# BlockBox.net
KiCad netlist of a schematic drawn in EAGLE
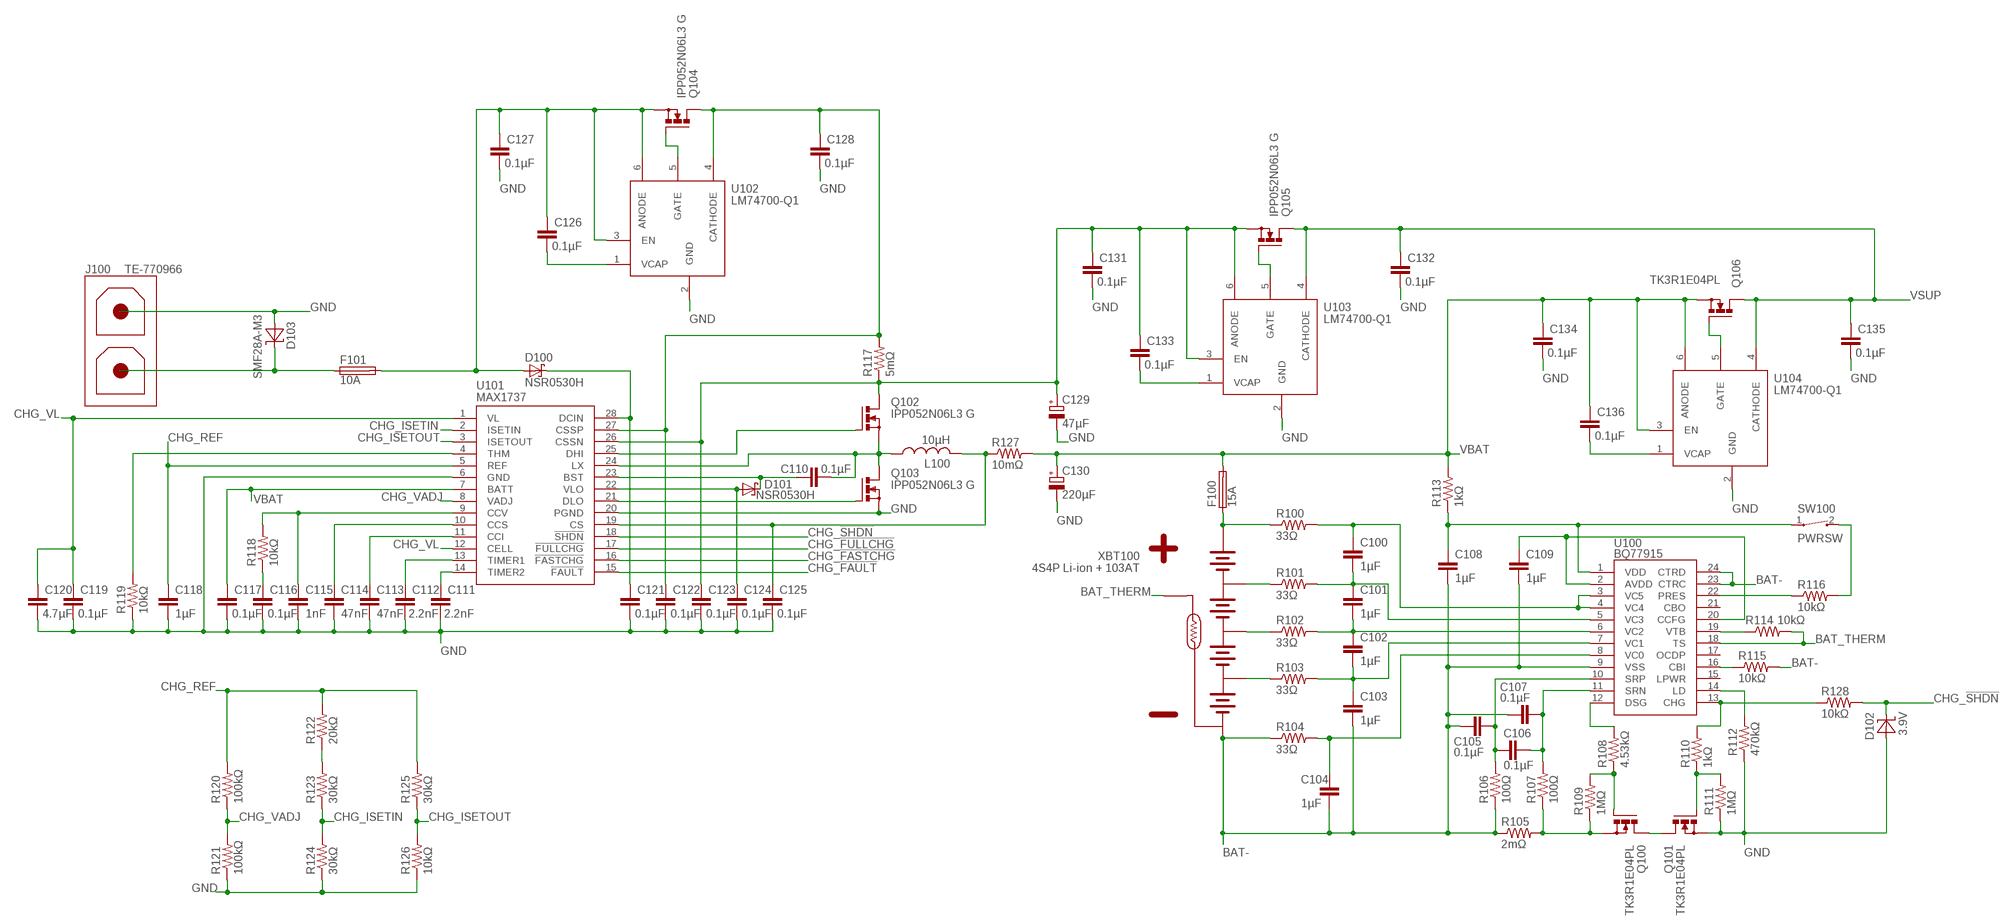
[diagram p0: schematic, sheet 1]
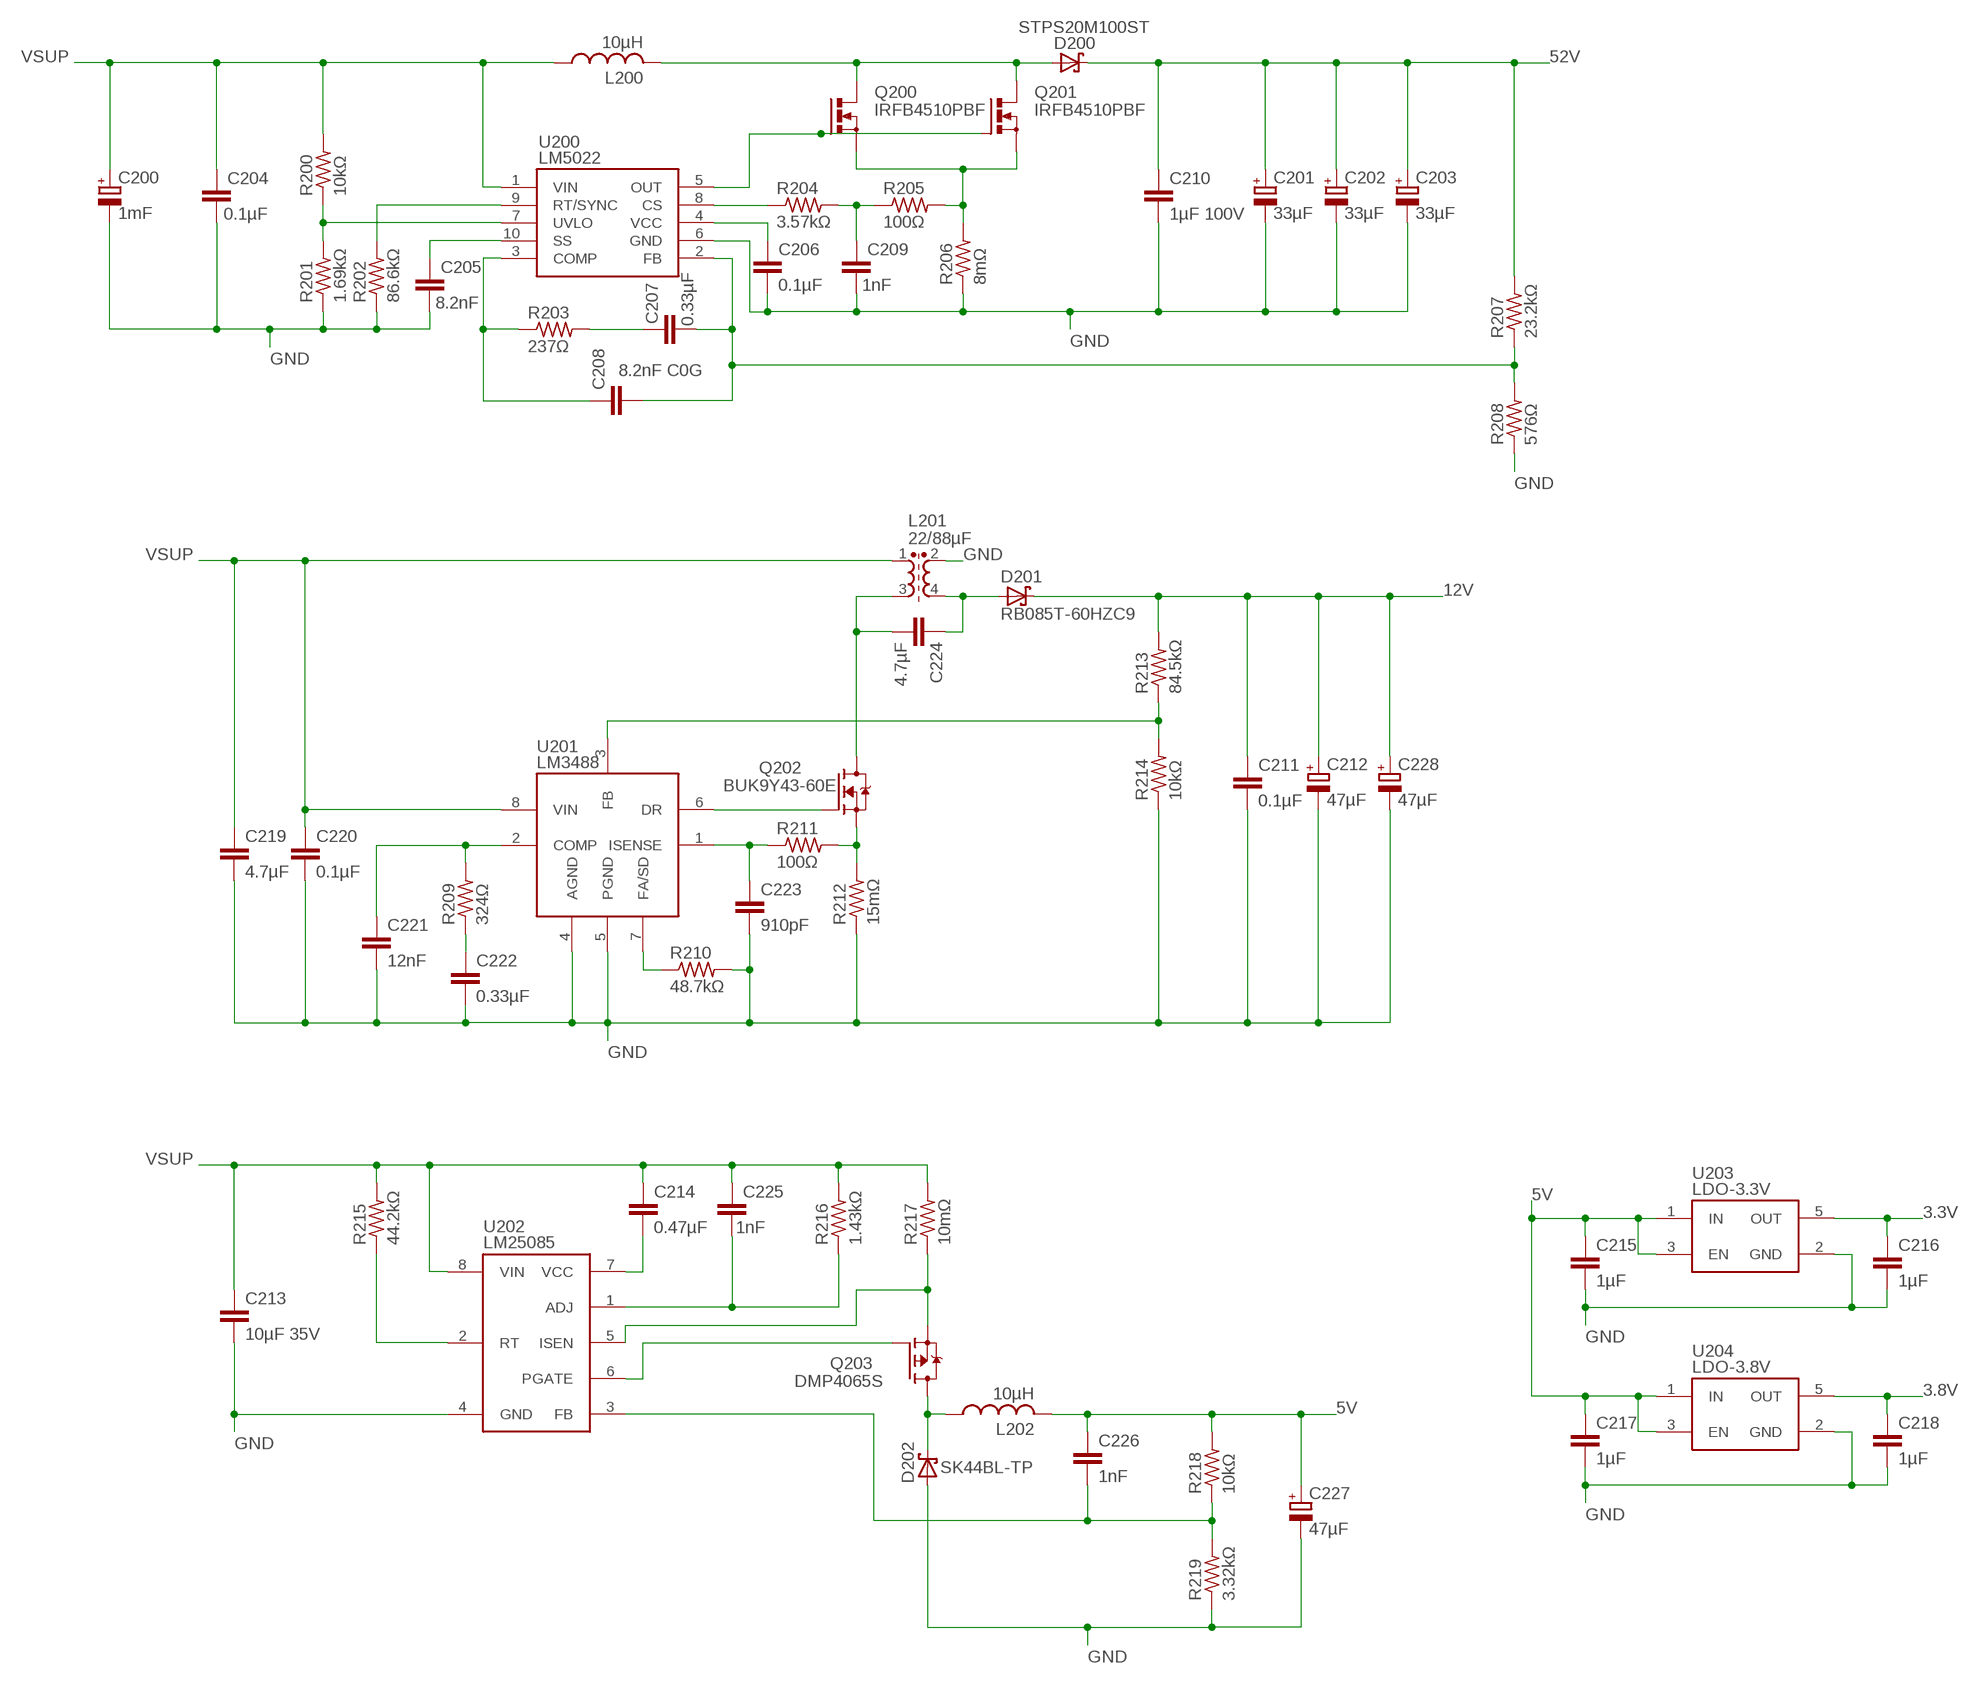
[diagram p1: schematic, sheet 2]
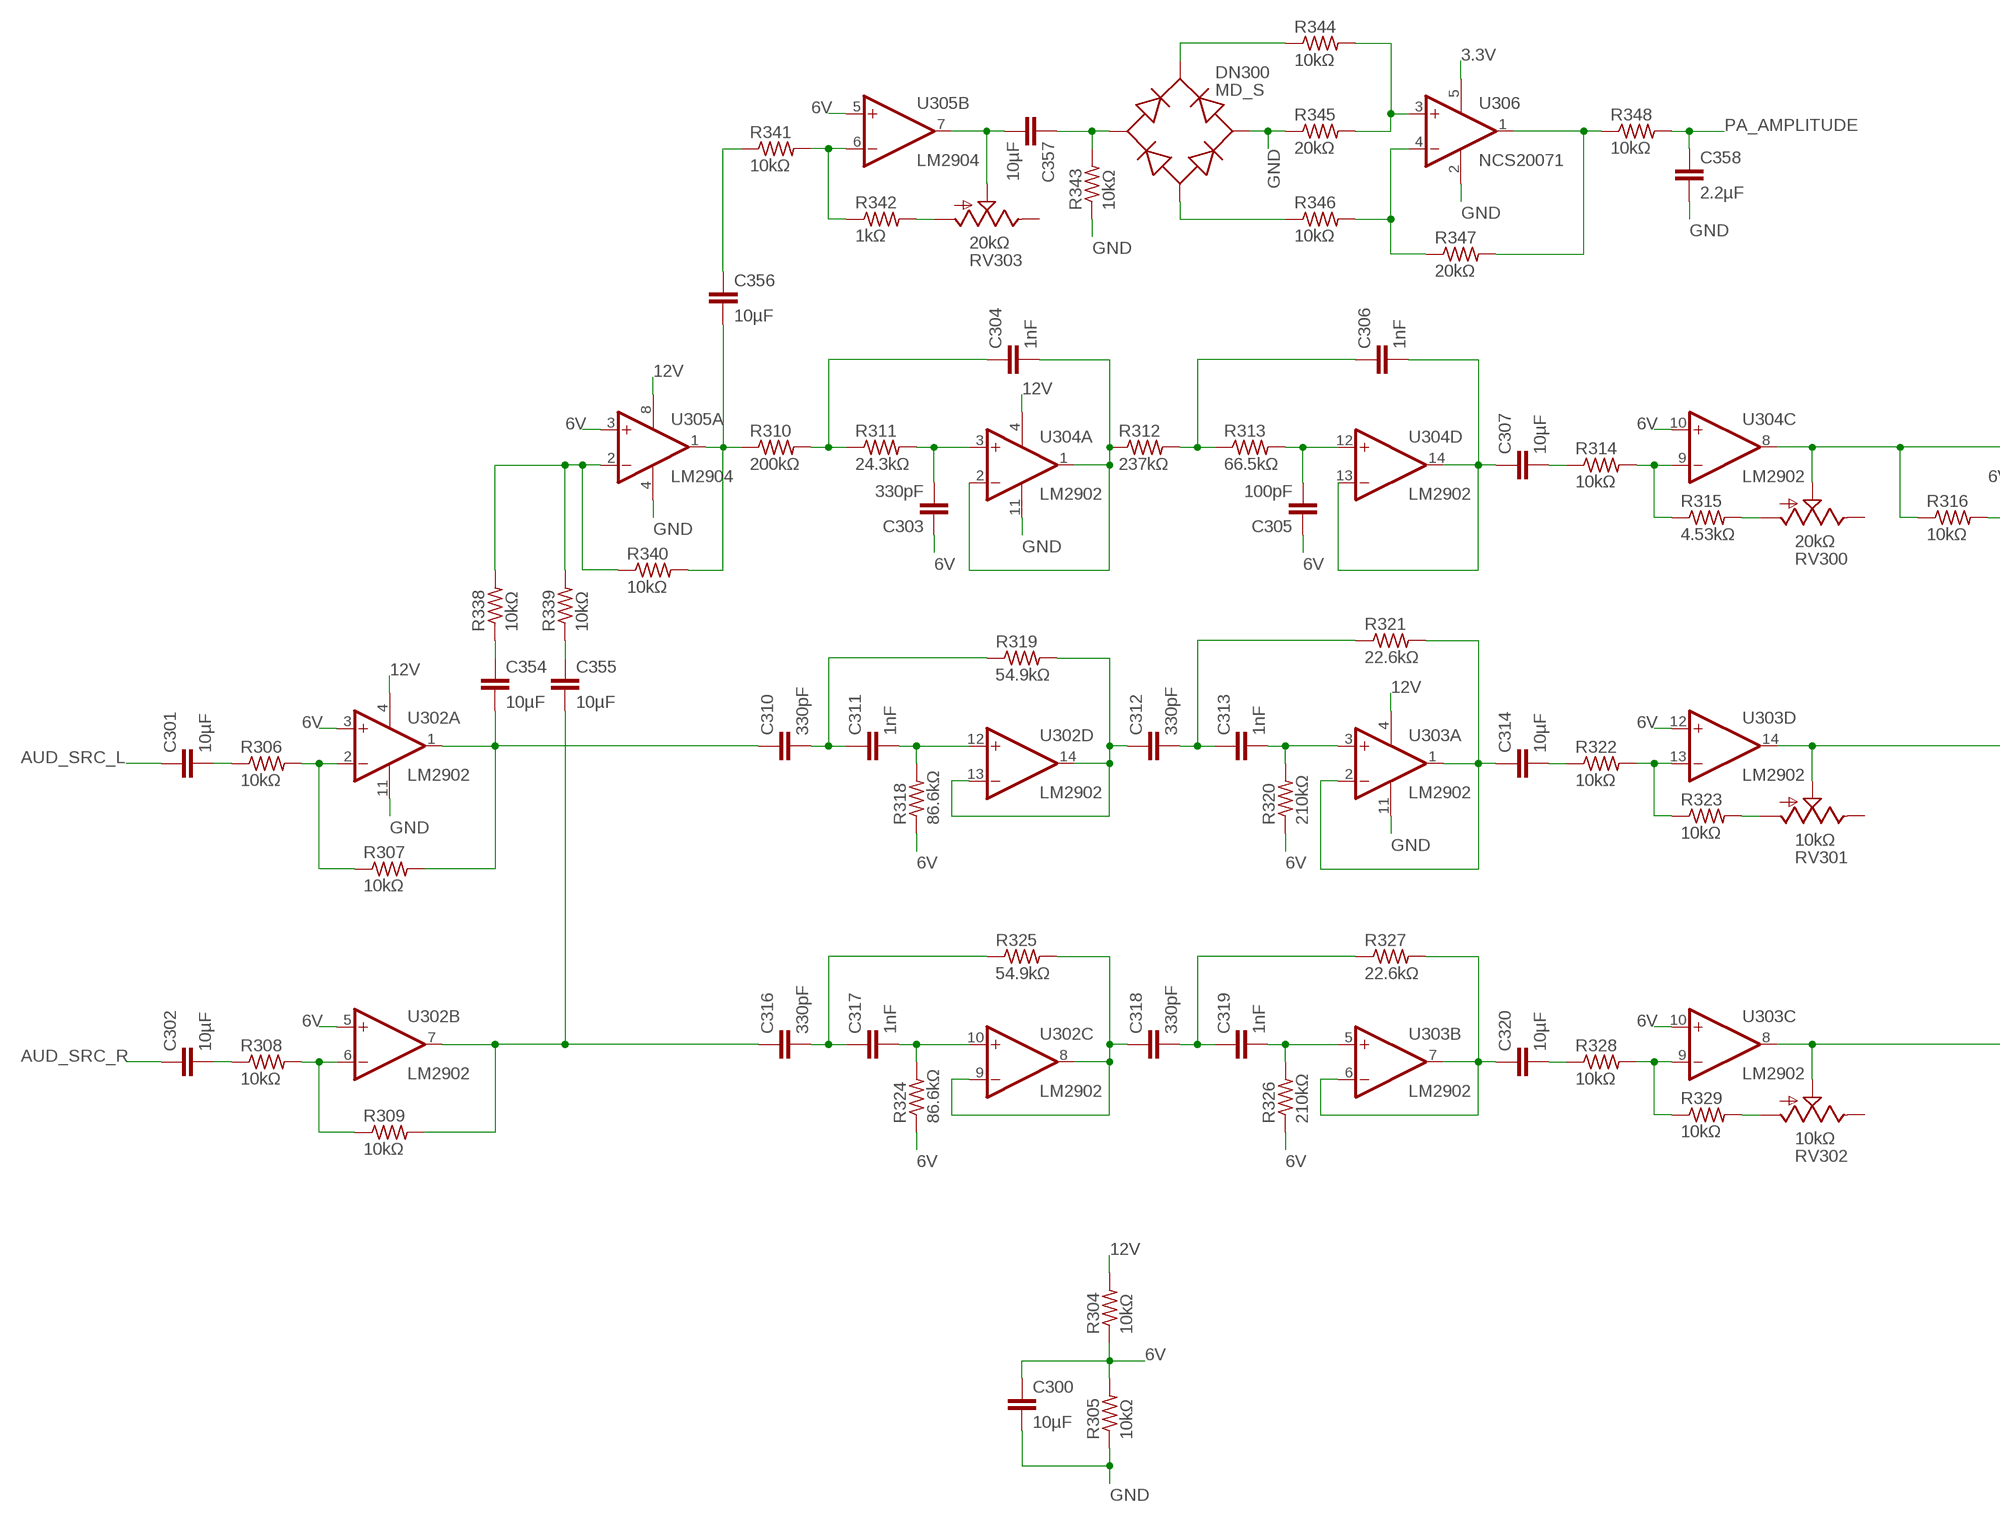
[diagram p2: schematic, sheet 3, part 1 of 2]
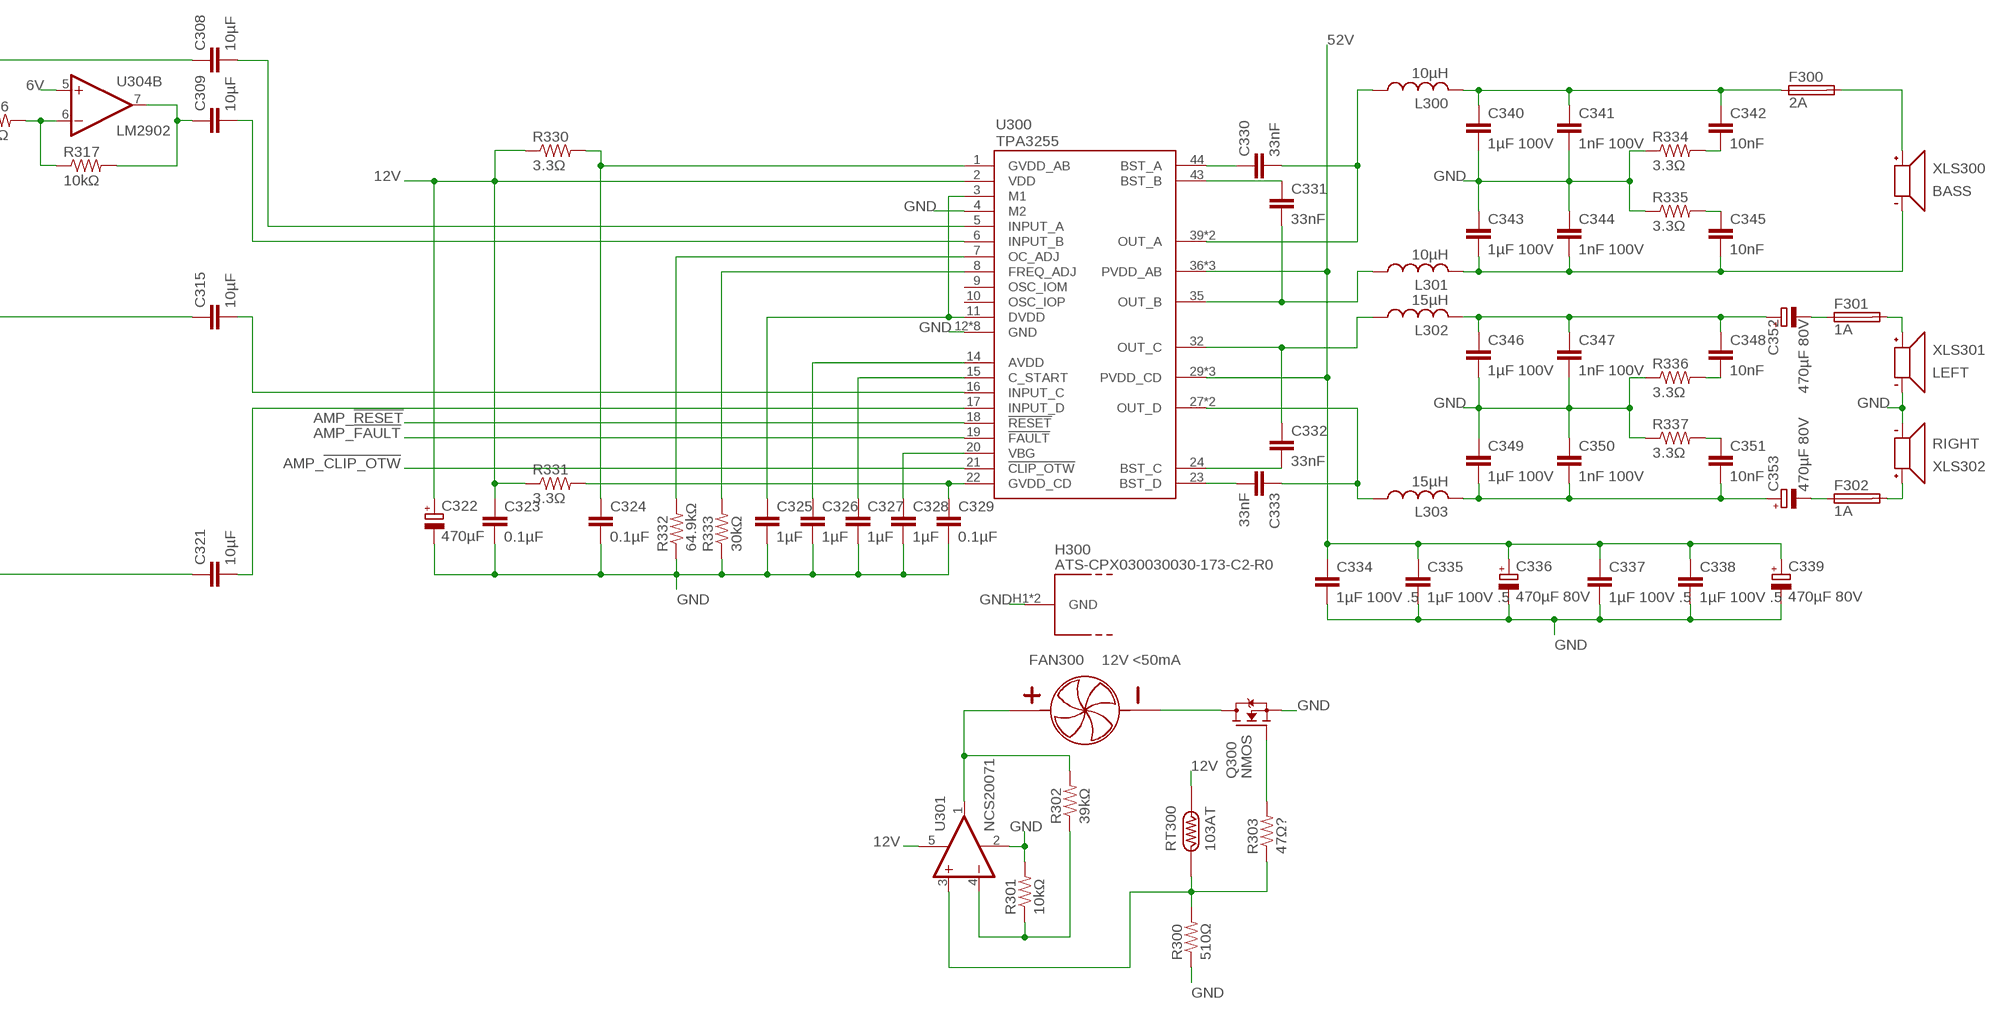
[diagram p3: schematic, sheet 3, part 2 of 2]
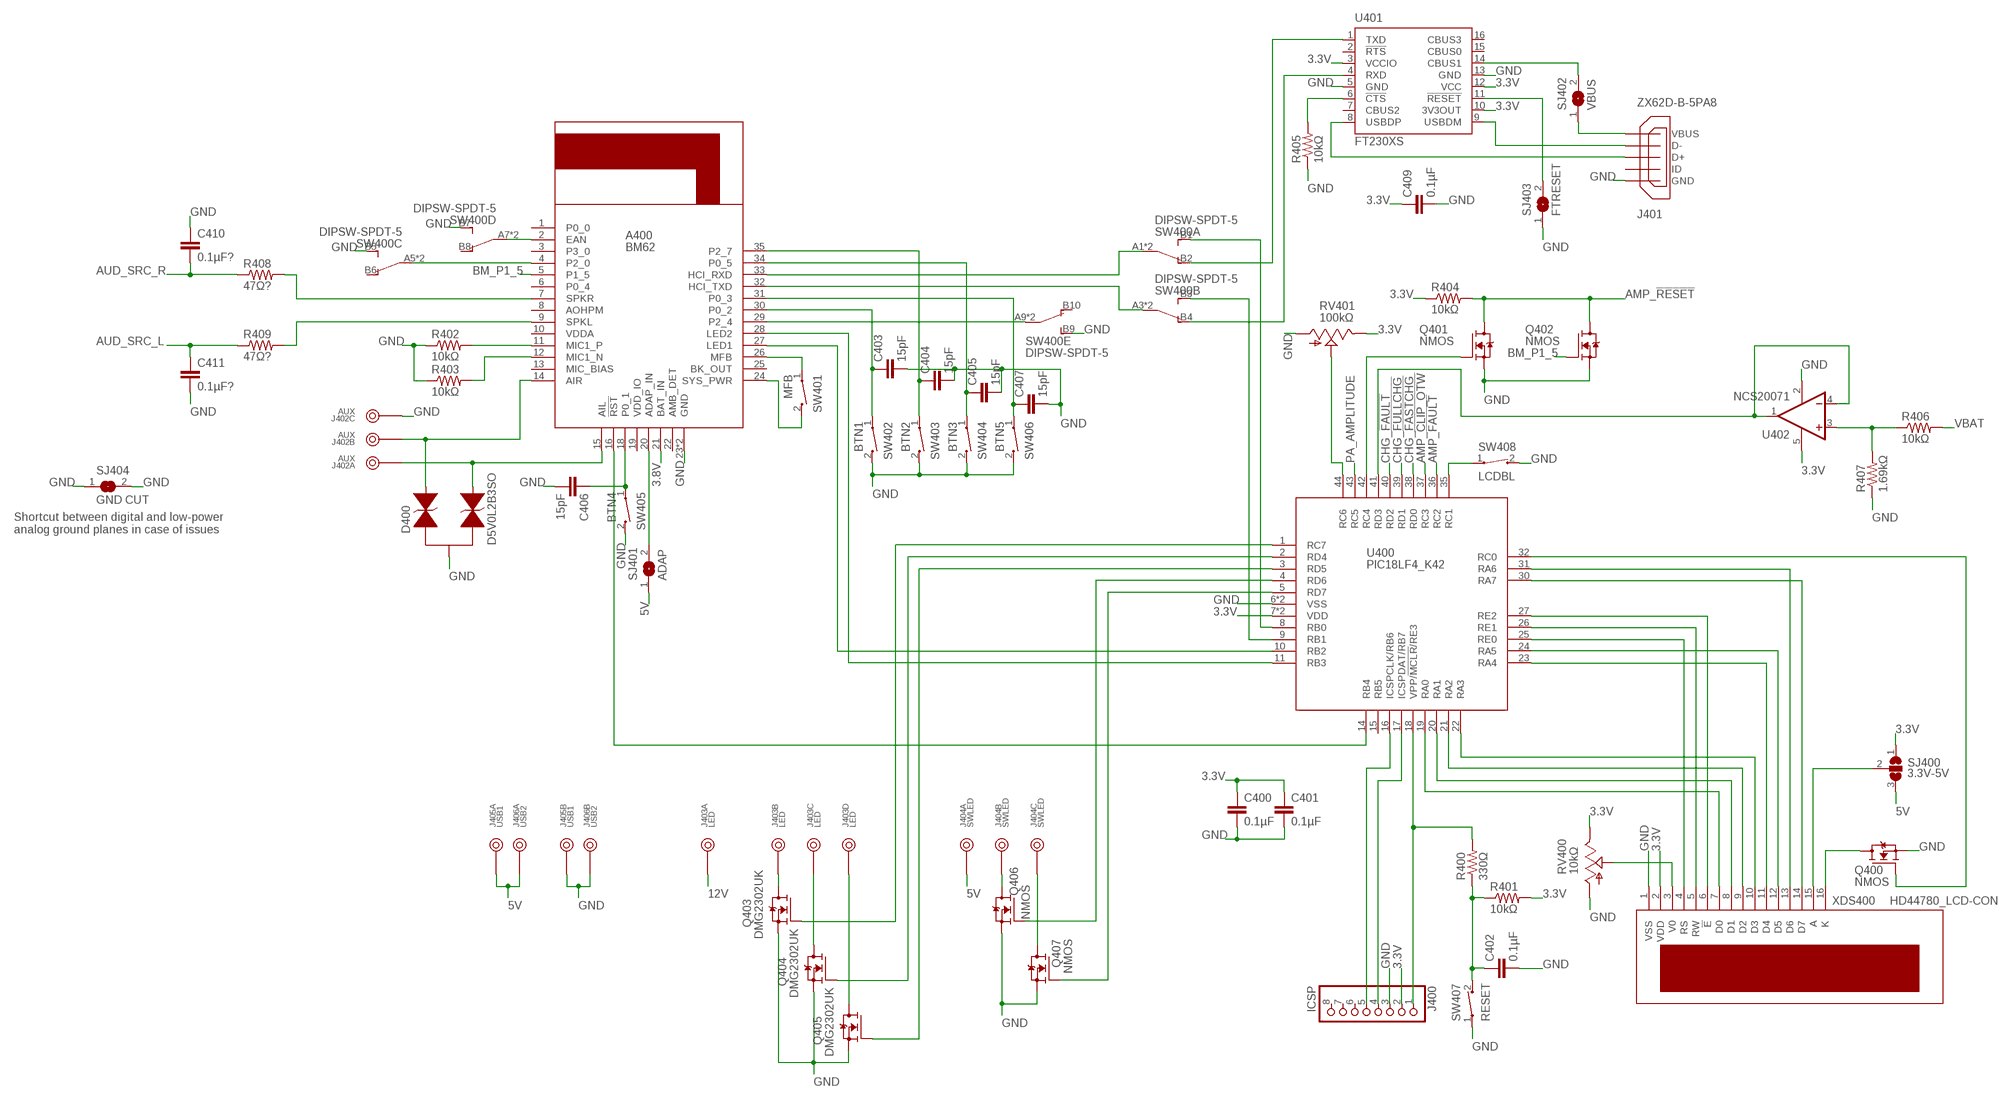
[diagram p4: schematic, sheet 4]

(export (version "E")
  (design (tool "Eeschema 10.0.6"))
  (components
    (comp (ref "C100")
      (value "1µF")
      (footprint "eagle-import:C0603")
      (libsource (lib "eagle-import") (part "C-EUC0603"))
    )
    (comp (ref "C101")
      (value "1µF")
      (footprint "eagle-import:C0603")
      (libsource (lib "eagle-import") (part "C-EUC0603"))
    )
    (comp (ref "C102")
      (value "1µF")
      (footprint "eagle-import:C0603")
      (libsource (lib "eagle-import") (part "C-EUC0603"))
    )
    (comp (ref "C103")
      (value "1µF")
      (footprint "eagle-import:C0603")
      (libsource (lib "eagle-import") (part "C-EUC0603"))
    )
    (comp (ref "C104")
      (value "1µF")
      (footprint "eagle-import:C0603")
      (libsource (lib "eagle-import") (part "C-EUC0603"))
    )
    (comp (ref "C105")
      (value "0.1µF")
      (footprint "eagle-import:C0805")
      (libsource (lib "eagle-import") (part "C-EUC0805"))
    )
    (comp (ref "C106")
      (value "0.1µF")
      (footprint "eagle-import:C0805")
      (libsource (lib "eagle-import") (part "C-EUC0805"))
    )
    (comp (ref "C107")
      (value "0.1µF")
      (footprint "eagle-import:C0805")
      (libsource (lib "eagle-import") (part "C-EUC0805"))
    )
    (comp (ref "C108")
      (value "1µF")
      (footprint "eagle-import:C0603")
      (libsource (lib "eagle-import") (part "C-EUC0603"))
    )
    (comp (ref "C109")
      (value "1µF")
      (footprint "eagle-import:C0603")
      (libsource (lib "eagle-import") (part "C-EUC0603"))
    )
    (comp (ref "C110")
      (value "0.1µF")
      (footprint "eagle-import:C0805")
      (libsource (lib "eagle-import") (part "C-EUC0805"))
    )
    (comp (ref "C111")
      (value "2.2nF")
      (footprint "eagle-import:C0603")
      (libsource (lib "eagle-import") (part "C-EUC0603"))
    )
    (comp (ref "C112")
      (value "2.2nF")
      (footprint "eagle-import:C0603")
      (libsource (lib "eagle-import") (part "C-EUC0603"))
    )
    (comp (ref "C113")
      (value "47nF")
      (footprint "eagle-import:C0603")
      (libsource (lib "eagle-import") (part "C-EUC0603"))
    )
    (comp (ref "C114")
      (value "47nF")
      (footprint "eagle-import:C0603")
      (libsource (lib "eagle-import") (part "C-EUC0603"))
    )
    (comp (ref "C115")
      (value "1nF")
      (footprint "eagle-import:C0603")
      (libsource (lib "eagle-import") (part "C-EUC0603"))
    )
    (comp (ref "C116")
      (value "0.1µF")
      (footprint "eagle-import:C0805")
      (libsource (lib "eagle-import") (part "C-EUC0805"))
    )
    (comp (ref "C117")
      (value "0.1µF")
      (footprint "eagle-import:C0805")
      (libsource (lib "eagle-import") (part "C-EUC0805"))
    )
    (comp (ref "C118")
      (value "1µF")
      (footprint "eagle-import:C0603")
      (libsource (lib "eagle-import") (part "C-EUC0603"))
    )
    (comp (ref "C119")
      (value "0.1µF")
      (footprint "eagle-import:C0805")
      (libsource (lib "eagle-import") (part "C-EUC0805"))
    )
    (comp (ref "C120")
      (value "4.7µF")
      (footprint "eagle-import:C0805")
      (libsource (lib "eagle-import") (part "C-EUC0805"))
    )
    (comp (ref "C121")
      (value "0.1µF")
      (footprint "eagle-import:C0805")
      (libsource (lib "eagle-import") (part "C-EUC0805"))
    )
    (comp (ref "C122")
      (value "0.1µF")
      (footprint "eagle-import:C0805")
      (libsource (lib "eagle-import") (part "C-EUC0805"))
    )
    (comp (ref "C123")
      (value "0.1µF")
      (footprint "eagle-import:C0805")
      (libsource (lib "eagle-import") (part "C-EUC0805"))
    )
    (comp (ref "C124")
      (value "0.1µF")
      (footprint "eagle-import:C0805")
      (libsource (lib "eagle-import") (part "C-EUC0805"))
    )
    (comp (ref "C125")
      (value "0.1µF")
      (footprint "eagle-import:C0805")
      (libsource (lib "eagle-import") (part "C-EUC0805"))
    )
    (comp (ref "C126")
      (value "0.1µF")
      (footprint "eagle-import:C0805")
      (libsource (lib "eagle-import") (part "C-EUC0805"))
    )
    (comp (ref "C127")
      (value "0.1µF")
      (footprint "eagle-import:C0805")
      (libsource (lib "eagle-import") (part "C-EUC0805"))
    )
    (comp (ref "C128")
      (value "0.1µF")
      (footprint "eagle-import:C0805")
      (libsource (lib "eagle-import") (part "C-EUC0805"))
    )
    (comp (ref "C129")
      (value "47µF")
      (footprint "eagle-import:E2,5-6")
      (libsource (lib "eagle-import") (part "CPOL-EUE2.5-6"))
    )
    (comp (ref "C130")
      (value "220µF")
      (footprint "eagle-import:E3,5-8")
      (libsource (lib "eagle-import") (part "CPOL-EUE3.5-8"))
    )
    (comp (ref "C131")
      (value "0.1µF")
      (footprint "eagle-import:C0805")
      (libsource (lib "eagle-import") (part "C-EUC0805"))
    )
    (comp (ref "C132")
      (value "0.1µF")
      (footprint "eagle-import:C0805")
      (libsource (lib "eagle-import") (part "C-EUC0805"))
    )
    (comp (ref "C133")
      (value "0.1µF")
      (footprint "eagle-import:C0805")
      (libsource (lib "eagle-import") (part "C-EUC0805"))
    )
    (comp (ref "C134")
      (value "0.1µF")
      (footprint "eagle-import:C0805")
      (libsource (lib "eagle-import") (part "C-EUC0805"))
    )
    (comp (ref "C135")
      (value "0.1µF")
      (footprint "eagle-import:C0805")
      (libsource (lib "eagle-import") (part "C-EUC0805"))
    )
    (comp (ref "C136")
      (value "0.1µF")
      (footprint "eagle-import:C0805")
      (libsource (lib "eagle-import") (part "C-EUC0805"))
    )
    (comp (ref "D100")
      (value "NSR0530H")
      (footprint "eagle-import:SOD323")
      (libsource (lib "eagle-import") (part "SOD323-SCHOTTKY"))
    )
    (comp (ref "D101")
      (value "NSR0530H")
      (footprint "eagle-import:SOD323")
      (libsource (lib "eagle-import") (part "SOD323-SCHOTTKY"))
    )
    (comp (ref "D102")
      (value "3.9V")
      (footprint "eagle-import:SOD323")
      (libsource (lib "eagle-import") (part "SOD323-ZENER"))
    )
    (comp (ref "D103")
      (value "SMF28A-M3")
      (footprint "eagle-import:DO-219AB")
      (libsource (lib "eagle-import") (part "DO-219AB-ZENER"))
    )
    (comp (ref "F100")
      (value "15A")
      (footprint "eagle-import:F2410")
      (libsource (lib "eagle-import") (part "2410-FUSE"))
    )
    (comp (ref "F101")
      (value "10A")
      (footprint "eagle-import:F2410")
      (libsource (lib "eagle-import") (part "2410-FUSE"))
    )
    (comp (ref "J100")
      (value "TE-770966")
      (footprint "eagle-import:TE-770966")
      (libsource (lib "eagle-import") (part "TE-770966"))
    )
    (comp (ref "L100")
      (value "10µH")
      (footprint "eagle-import:PM5022")
      (libsource (lib "eagle-import") (part "PM5022"))
    )
    (comp (ref "Q100")
      (value "TK3R1E04PL")
      (footprint "eagle-import:TO220BV")
      (libsource (lib "eagle-import") (part "TO220BV-N-MOSFET"))
    )
    (comp (ref "Q101")
      (value "TK3R1E04PL")
      (footprint "eagle-import:TO220BV")
      (libsource (lib "eagle-import") (part "TO220BV-N-MOSFET"))
    )
    (comp (ref "Q102")
      (value "IPP052N06L3 G")
      (footprint "eagle-import:TO220BV")
      (libsource (lib "eagle-import") (part "TO220BV-N-MOSFET"))
    )
    (comp (ref "Q103")
      (value "IPP052N06L3 G")
      (footprint "eagle-import:TO220BV")
      (libsource (lib "eagle-import") (part "TO220BV-N-MOSFET"))
    )
    (comp (ref "Q104")
      (value "IPP052N06L3 G")
      (footprint "eagle-import:TO220BV")
      (libsource (lib "eagle-import") (part "TO220BV-N-MOSFET"))
    )
    (comp (ref "Q105")
      (value "IPP052N06L3 G")
      (footprint "eagle-import:TO220BV")
      (libsource (lib "eagle-import") (part "TO220BV-N-MOSFET"))
    )
    (comp (ref "Q106")
      (value "TK3R1E04PL")
      (footprint "eagle-import:TO220BV")
      (libsource (lib "eagle-import") (part "TO220BV-N-MOSFET"))
    )
    (comp (ref "R100")
      (value "33Ω")
      (footprint "eagle-import:R0603")
      (libsource (lib "eagle-import") (part "R-US_R0603"))
    )
    (comp (ref "R101")
      (value "33Ω")
      (footprint "eagle-import:R0603")
      (libsource (lib "eagle-import") (part "R-US_R0603"))
    )
    (comp (ref "R102")
      (value "33Ω")
      (footprint "eagle-import:R0603")
      (libsource (lib "eagle-import") (part "R-US_R0603"))
    )
    (comp (ref "R103")
      (value "33Ω")
      (footprint "eagle-import:R0603")
      (libsource (lib "eagle-import") (part "R-US_R0603"))
    )
    (comp (ref "R104")
      (value "33Ω")
      (footprint "eagle-import:R0603")
      (libsource (lib "eagle-import") (part "R-US_R0603"))
    )
    (comp (ref "R105")
      (value "2mΩ")
      (footprint "eagle-import:R2512")
      (libsource (lib "eagle-import") (part "R-US_R2512"))
    )
    (comp (ref "R106")
      (value "100Ω")
      (footprint "eagle-import:R0603")
      (libsource (lib "eagle-import") (part "R-US_R0603"))
    )
    (comp (ref "R107")
      (value "100Ω")
      (footprint "eagle-import:R0603")
      (libsource (lib "eagle-import") (part "R-US_R0603"))
    )
    (comp (ref "R108")
      (value "4.53kΩ")
      (footprint "eagle-import:R0603")
      (libsource (lib "eagle-import") (part "R-US_R0603"))
    )
    (comp (ref "R109")
      (value "1MΩ")
      (footprint "eagle-import:R0603")
      (libsource (lib "eagle-import") (part "R-US_R0603"))
    )
    (comp (ref "R110")
      (value "1kΩ")
      (footprint "eagle-import:R0805")
      (libsource (lib "eagle-import") (part "R-US_R0805"))
    )
    (comp (ref "R111")
      (value "1MΩ")
      (footprint "eagle-import:R0603")
      (libsource (lib "eagle-import") (part "R-US_R0603"))
    )
    (comp (ref "R112")
      (value "470kΩ")
      (footprint "eagle-import:R0603")
      (libsource (lib "eagle-import") (part "R-US_R0603"))
    )
    (comp (ref "R113")
      (value "1kΩ")
      (footprint "eagle-import:R0805")
      (libsource (lib "eagle-import") (part "R-US_R0805"))
    )
    (comp (ref "R114")
      (value "10kΩ")
      (footprint "eagle-import:R0805")
      (libsource (lib "eagle-import") (part "R-US_R0805"))
    )
    (comp (ref "R115")
      (value "10kΩ")
      (footprint "eagle-import:R0805")
      (libsource (lib "eagle-import") (part "R-US_R0805"))
    )
    (comp (ref "R116")
      (value "10kΩ")
      (footprint "eagle-import:R0805")
      (libsource (lib "eagle-import") (part "R-US_R0805"))
    )
    (comp (ref "R117")
      (value "5mΩ")
      (footprint "eagle-import:R1206")
      (libsource (lib "eagle-import") (part "R-US_R1206"))
    )
    (comp (ref "R118")
      (value "10kΩ")
      (footprint "eagle-import:R0805")
      (libsource (lib "eagle-import") (part "R-US_R0805"))
    )
    (comp (ref "R119")
      (value "10kΩ")
      (footprint "eagle-import:R0805")
      (libsource (lib "eagle-import") (part "R-US_R0805"))
    )
    (comp (ref "R120")
      (value "100kΩ")
      (footprint "eagle-import:R0805")
      (libsource (lib "eagle-import") (part "R-US_R0805"))
    )
    (comp (ref "R121")
      (value "100kΩ")
      (footprint "eagle-import:R0805")
      (libsource (lib "eagle-import") (part "R-US_R0805"))
    )
    (comp (ref "R122")
      (value "20kΩ")
      (footprint "eagle-import:R0603")
      (libsource (lib "eagle-import") (part "R-US_R0603"))
    )
    (comp (ref "R123")
      (value "30kΩ")
      (footprint "eagle-import:R0603")
      (libsource (lib "eagle-import") (part "R-US_R0603"))
    )
    (comp (ref "R124")
      (value "30kΩ")
      (footprint "eagle-import:R0603")
      (libsource (lib "eagle-import") (part "R-US_R0603"))
    )
    (comp (ref "R125")
      (value "30kΩ")
      (footprint "eagle-import:R0603")
      (libsource (lib "eagle-import") (part "R-US_R0603"))
    )
    (comp (ref "R126")
      (value "10kΩ")
      (footprint "eagle-import:R0805")
      (libsource (lib "eagle-import") (part "R-US_R0805"))
    )
    (comp (ref "R127")
      (value "10mΩ")
      (footprint "eagle-import:R1206")
      (libsource (lib "eagle-import") (part "R-US_R1206"))
    )
    (comp (ref "R128")
      (value "10kΩ")
      (footprint "eagle-import:R0805")
      (libsource (lib "eagle-import") (part "R-US_R0805"))
    )
    (comp (ref "SW100")
      (value "PWRSW")
      (footprint "eagle-import:WIRE-2P-SIMPLE")
      (libsource (lib "eagle-import") (part "WIRED-SWITCH-NO"))
    )
    (comp (ref "U100")
      (value "BQ77915")
      (footprint "eagle-import:TSSOP24")
      (libsource (lib "eagle-import") (part "BQ77915"))
    )
    (comp (ref "U101")
      (value "MAX1737")
      (footprint "eagle-import:QSOP28")
      (libsource (lib "eagle-import") (part "MAX1737"))
    )
    (comp (ref "U102")
      (value "LM74700-Q1")
      (footprint "eagle-import:SOT23-6L")
      (libsource (lib "eagle-import") (part "LM74700-Q1"))
    )
    (comp (ref "U103")
      (value "LM74700-Q1")
      (footprint "eagle-import:SOT23-6L")
      (libsource (lib "eagle-import") (part "LM74700-Q1"))
    )
    (comp (ref "U104")
      (value "LM74700-Q1")
      (footprint "eagle-import:SOT23-6L")
      (libsource (lib "eagle-import") (part "LM74700-Q1"))
    )
    (comp (ref "XBT100")
      (value "4S4P Li-ion + 103AT")
      (footprint "eagle-import:TE-770970")
      (libsource (lib "eagle-import") (part "LI-ION-PACK-CONN"))
    )
    (comp (ref "C200")
      (value "1mF")
      (footprint "eagle-import:E7,5-16")
      (libsource (lib "eagle-import") (part "CPOL-EUE7.5-16"))
    )
    (comp (ref "C201")
      (value "33µF")
      (footprint "eagle-import:E3,5-8")
      (libsource (lib "eagle-import") (part "CPOL-EUE3.5-8"))
    )
    (comp (ref "C202")
      (value "33µF")
      (footprint "eagle-import:E3,5-8")
      (libsource (lib "eagle-import") (part "CPOL-EUE3.5-8"))
    )
    (comp (ref "C203")
      (value "33µF")
      (footprint "eagle-import:E3,5-8")
      (libsource (lib "eagle-import") (part "CPOL-EUE3.5-8"))
    )
    (comp (ref "C204")
      (value "0.1µF")
      (footprint "eagle-import:C0805")
      (libsource (lib "eagle-import") (part "C-EUC0805"))
    )
    (comp (ref "C205")
      (value "8.2nF")
      (footprint "eagle-import:C0603")
      (libsource (lib "eagle-import") (part "C-EUC0603"))
    )
    (comp (ref "C206")
      (value "0.1µF")
      (footprint "eagle-import:C0805")
      (libsource (lib "eagle-import") (part "C-EUC0805"))
    )
    (comp (ref "C207")
      (value "0.33µF")
      (footprint "eagle-import:C050-035X075")
      (libsource (lib "eagle-import") (part "C-EU050-035X075"))
    )
    (comp (ref "C208")
      (value "8.2nF C0G")
      (footprint "eagle-import:C0603")
      (libsource (lib "eagle-import") (part "C-EUC0603"))
    )
    (comp (ref "C209")
      (value "1nF")
      (footprint "eagle-import:C0603")
      (libsource (lib "eagle-import") (part "C-EUC0603"))
    )
    (comp (ref "C210")
      (value "1µF 100V")
      (footprint "eagle-import:C1206")
      (libsource (lib "eagle-import") (part "C-EUC1206"))
    )
    (comp (ref "C211")
      (value "0.1µF")
      (footprint "eagle-import:C0805")
      (libsource (lib "eagle-import") (part "C-EUC0805"))
    )
    (comp (ref "C212")
      (value "47µF")
      (footprint "eagle-import:E2,5-6")
      (libsource (lib "eagle-import") (part "CPOL-EUE2.5-6"))
    )
    (comp (ref "C213")
      (value "10µF 35V")
      (footprint "eagle-import:C1206")
      (libsource (lib "eagle-import") (part "C-EUC1206"))
    )
    (comp (ref "C214")
      (value "0.47µF")
      (footprint "eagle-import:C0603")
      (libsource (lib "eagle-import") (part "C-EUC0603"))
    )
    (comp (ref "C215")
      (value "1µF")
      (footprint "eagle-import:C0603")
      (libsource (lib "eagle-import") (part "C-EUC0603"))
    )
    (comp (ref "C216")
      (value "1µF")
      (footprint "eagle-import:C0603")
      (libsource (lib "eagle-import") (part "C-EUC0603"))
    )
    (comp (ref "C217")
      (value "1µF")
      (footprint "eagle-import:C0603")
      (libsource (lib "eagle-import") (part "C-EUC0603"))
    )
    (comp (ref "C218")
      (value "1µF")
      (footprint "eagle-import:C0603")
      (libsource (lib "eagle-import") (part "C-EUC0603"))
    )
    (comp (ref "C219")
      (value "4.7µF")
      (footprint "eagle-import:C0805")
      (libsource (lib "eagle-import") (part "C-EUC0805"))
    )
    (comp (ref "C220")
      (value "0.1µF")
      (footprint "eagle-import:C0805")
      (libsource (lib "eagle-import") (part "C-EUC0805"))
    )
    (comp (ref "C221")
      (value "12nF")
      (footprint "eagle-import:C0805")
      (libsource (lib "eagle-import") (part "C-EUC0805"))
    )
    (comp (ref "C222")
      (value "0.33µF")
      (footprint "eagle-import:C050-035X075")
      (libsource (lib "eagle-import") (part "C-EU050-035X075"))
    )
    (comp (ref "C223")
      (value "910pF")
      (footprint "eagle-import:C0603")
      (libsource (lib "eagle-import") (part "C-EUC0603"))
    )
    (comp (ref "C224")
      (value "4.7µF")
      (footprint "eagle-import:C0805")
      (libsource (lib "eagle-import") (part "C-EUC0805"))
    )
    (comp (ref "C225")
      (value "1nF")
      (footprint "eagle-import:C0603")
      (libsource (lib "eagle-import") (part "C-EUC0603"))
    )
    (comp (ref "C226")
      (value "1nF")
      (footprint "eagle-import:C0603")
      (libsource (lib "eagle-import") (part "C-EUC0603"))
    )
    (comp (ref "C227")
      (value "47µF")
      (footprint "eagle-import:E2,5-6")
      (libsource (lib "eagle-import") (part "CPOL-EUE2.5-6"))
    )
    (comp (ref "C228")
      (value "47µF")
      (footprint "eagle-import:E2,5-6")
      (libsource (lib "eagle-import") (part "CPOL-EUE2.5-6"))
    )
    (comp (ref "D200")
      (value "STPS20M100ST")
      (footprint "eagle-import:TO220ABS")
      (libsource (lib "eagle-import") (part "TO220AB-SCHOTTKY"))
    )
    (comp (ref "D201")
      (value "RB085T-60HZC9")
      (footprint "eagle-import:TO220ABS")
      (libsource (lib "eagle-import") (part "TO220AB-SCHOTTKY"))
    )
    (comp (ref "D202")
      (value "SK44BL-TP")
      (footprint "eagle-import:DO-214AA")
      (libsource (lib "eagle-import") (part "DO-214AA-SCHOTTKY"))
    )
    (comp (ref "L200")
      (value "10µH")
      (footprint "eagle-import:PQ2614B")
      (libsource (lib "eagle-import") (part "PQ2614B"))
    )
    (comp (ref "L201")
      (value "22/88µF")
      (footprint "eagle-import:SRF1280A")
      (libsource (lib "eagle-import") (part "SRF1280A"))
    )
    (comp (ref "L202")
      (value "10µH")
      (footprint "eagle-import:SRN1060")
      (libsource (lib "eagle-import") (part "SRN1060"))
    )
    (comp (ref "Q200")
      (value "IRFB4510PBF")
      (footprint "eagle-import:TO220BV")
      (libsource (lib "eagle-import") (part "TO220BV-N-MOSFET"))
    )
    (comp (ref "Q201")
      (value "IRFB4510PBF")
      (footprint "eagle-import:TO220BV")
      (libsource (lib "eagle-import") (part "TO220BV-N-MOSFET"))
    )
    (comp (ref "Q202")
      (value "BUK9Y43-60E")
      (footprint "eagle-import:SOT669")
      (libsource (lib "eagle-import") (part "SOT669-N-MOSFET"))
    )
    (comp (ref "Q203")
      (value "DMP4065S")
      (footprint "eagle-import:SOT23")
      (libsource (lib "eagle-import") (part "SOT23-P-MOSFET"))
    )
    (comp (ref "R200")
      (value "10kΩ")
      (footprint "eagle-import:R0805")
      (libsource (lib "eagle-import") (part "R-US_R0805"))
    )
    (comp (ref "R201")
      (value "1.69kΩ")
      (footprint "eagle-import:R0603")
      (libsource (lib "eagle-import") (part "R-US_R0603"))
    )
    (comp (ref "R202")
      (value "86.6kΩ")
      (footprint "eagle-import:R0603")
      (libsource (lib "eagle-import") (part "R-US_R0603"))
    )
    (comp (ref "R203")
      (value "237Ω")
      (footprint "eagle-import:R0603")
      (libsource (lib "eagle-import") (part "R-US_R0603"))
    )
    (comp (ref "R204")
      (value "3.57kΩ")
      (footprint "eagle-import:R0603")
      (libsource (lib "eagle-import") (part "R-US_R0603"))
    )
    (comp (ref "R205")
      (value "100Ω")
      (footprint "eagle-import:R0603")
      (libsource (lib "eagle-import") (part "R-US_R0603"))
    )
    (comp (ref "R206")
      (value "8mΩ")
      (footprint "eagle-import:R1206")
      (libsource (lib "eagle-import") (part "R-US_R1206"))
    )
    (comp (ref "R207")
      (value "23.2kΩ")
      (footprint "eagle-import:R0603")
      (libsource (lib "eagle-import") (part "R-US_R0603"))
    )
    (comp (ref "R208")
      (value "576Ω")
      (footprint "eagle-import:R0603")
      (libsource (lib "eagle-import") (part "R-US_R0603"))
    )
    (comp (ref "R209")
      (value "324Ω")
      (footprint "eagle-import:R0603")
      (libsource (lib "eagle-import") (part "R-US_R0603"))
    )
    (comp (ref "R210")
      (value "48.7kΩ")
      (footprint "eagle-import:R0603")
      (libsource (lib "eagle-import") (part "R-US_R0603"))
    )
    (comp (ref "R211")
      (value "100Ω")
      (footprint "eagle-import:R0603")
      (libsource (lib "eagle-import") (part "R-US_R0603"))
    )
    (comp (ref "R212")
      (value "15mΩ")
      (footprint "eagle-import:R0612")
      (libsource (lib "eagle-import") (part "R-US_R0612"))
    )
    (comp (ref "R213")
      (value "84.5kΩ")
      (footprint "eagle-import:R0603")
      (libsource (lib "eagle-import") (part "R-US_R0603"))
    )
    (comp (ref "R214")
      (value "10kΩ")
      (footprint "eagle-import:R0805")
      (libsource (lib "eagle-import") (part "R-US_R0805"))
    )
    (comp (ref "R215")
      (value "44.2kΩ")
      (footprint "eagle-import:R0603")
      (libsource (lib "eagle-import") (part "R-US_R0603"))
    )
    (comp (ref "R216")
      (value "1.43kΩ")
      (footprint "eagle-import:R0603")
      (libsource (lib "eagle-import") (part "R-US_R0603"))
    )
    (comp (ref "R217")
      (value "10mΩ")
      (footprint "eagle-import:R1206")
      (libsource (lib "eagle-import") (part "R-US_R1206"))
    )
    (comp (ref "R218")
      (value "10kΩ")
      (footprint "eagle-import:R0805")
      (libsource (lib "eagle-import") (part "R-US_R0805"))
    )
    (comp (ref "R219")
      (value "3.32kΩ")
      (footprint "eagle-import:R0603")
      (libsource (lib "eagle-import") (part "R-US_R0603"))
    )
    (comp (ref "U200")
      (value "LM5022")
      (footprint "eagle-import:VSSOP10")
      (libsource (lib "eagle-import") (part "LM5022"))
    )
    (comp (ref "U201")
      (value "LM3488")
      (footprint "eagle-import:VSSOP8")
      (libsource (lib "eagle-import") (part "LM3488"))
    )
    (comp (ref "U202")
      (value "LM25085")
      (footprint "eagle-import:VSSOP8")
      (libsource (lib "eagle-import") (part "LM25085"))
    )
    (comp (ref "U203")
      (value "LDO-3.3V")
      (footprint "eagle-import:SOT23-5L")
      (libsource (lib "eagle-import") (part "SOT23-5-LDO"))
    )
    (comp (ref "U204")
      (value "LDO-3.8V")
      (footprint "eagle-import:SOT23-5L")
      (libsource (lib "eagle-import") (part "SOT23-5-LDO"))
    )
    (comp (ref "C300")
      (value "10µF")
      (footprint "eagle-import:C0805")
      (libsource (lib "eagle-import") (part "C-EUC0805"))
    )
    (comp (ref "C301")
      (value "10µF")
      (footprint "eagle-import:C0805")
      (libsource (lib "eagle-import") (part "C-EUC0805"))
    )
    (comp (ref "C302")
      (value "10µF")
      (footprint "eagle-import:C0805")
      (libsource (lib "eagle-import") (part "C-EUC0805"))
    )
    (comp (ref "C303")
      (value "330pF")
      (footprint "eagle-import:C0603")
      (libsource (lib "eagle-import") (part "C-EUC0603"))
    )
    (comp (ref "C304")
      (value "1nF")
      (footprint "eagle-import:C0603")
      (libsource (lib "eagle-import") (part "C-EUC0603"))
    )
    (comp (ref "C305")
      (value "100pF")
      (footprint "eagle-import:C0603")
      (libsource (lib "eagle-import") (part "C-EUC0603"))
    )
    (comp (ref "C306")
      (value "1nF")
      (footprint "eagle-import:C0603")
      (libsource (lib "eagle-import") (part "C-EUC0603"))
    )
    (comp (ref "C307")
      (value "10µF")
      (footprint "eagle-import:C0805")
      (libsource (lib "eagle-import") (part "C-EUC0805"))
    )
    (comp (ref "C308")
      (value "10µF")
      (footprint "eagle-import:C0603")
      (libsource (lib "eagle-import") (part "C-EUC0603"))
    )
    (comp (ref "C309")
      (value "10µF")
      (footprint "eagle-import:C0603")
      (libsource (lib "eagle-import") (part "C-EUC0603"))
    )
    (comp (ref "C310")
      (value "330pF")
      (footprint "eagle-import:C0603")
      (libsource (lib "eagle-import") (part "C-EUC0603"))
    )
    (comp (ref "C311")
      (value "1nF")
      (footprint "eagle-import:C0603")
      (libsource (lib "eagle-import") (part "C-EUC0603"))
    )
    (comp (ref "C312")
      (value "330pF")
      (footprint "eagle-import:C0603")
      (libsource (lib "eagle-import") (part "C-EUC0603"))
    )
    (comp (ref "C313")
      (value "1nF")
      (footprint "eagle-import:C0603")
      (libsource (lib "eagle-import") (part "C-EUC0603"))
    )
    (comp (ref "C314")
      (value "10µF")
      (footprint "eagle-import:C0805")
      (libsource (lib "eagle-import") (part "C-EUC0805"))
    )
    (comp (ref "C315")
      (value "10µF")
      (footprint "eagle-import:C0603")
      (libsource (lib "eagle-import") (part "C-EUC0603"))
    )
    (comp (ref "C316")
      (value "330pF")
      (footprint "eagle-import:C0603")
      (libsource (lib "eagle-import") (part "C-EUC0603"))
    )
    (comp (ref "C317")
      (value "1nF")
      (footprint "eagle-import:C0603")
      (libsource (lib "eagle-import") (part "C-EUC0603"))
    )
    (comp (ref "C318")
      (value "330pF")
      (footprint "eagle-import:C0603")
      (libsource (lib "eagle-import") (part "C-EUC0603"))
    )
    (comp (ref "C319")
      (value "1nF")
      (footprint "eagle-import:C0603")
      (libsource (lib "eagle-import") (part "C-EUC0603"))
    )
    (comp (ref "C320")
      (value "10µF")
      (footprint "eagle-import:C0805")
      (libsource (lib "eagle-import") (part "C-EUC0805"))
    )
    (comp (ref "C321")
      (value "10µF")
      (footprint "eagle-import:C0603")
      (libsource (lib "eagle-import") (part "C-EUC0603"))
    )
    (comp (ref "C322")
      (value "470µF")
      (footprint "eagle-import:E3,5-8")
      (libsource (lib "eagle-import") (part "CPOL-EUE3.5-8"))
    )
    (comp (ref "C323")
      (value "0.1µF")
      (footprint "eagle-import:C0805")
      (libsource (lib "eagle-import") (part "C-EUC0805"))
    )
    (comp (ref "C324")
      (value "0.1µF")
      (footprint "eagle-import:C0805")
      (libsource (lib "eagle-import") (part "C-EUC0805"))
    )
    (comp (ref "C325")
      (value "1µF")
      (footprint "eagle-import:C0603")
      (libsource (lib "eagle-import") (part "C-EUC0603"))
    )
    (comp (ref "C326")
      (value "1µF")
      (footprint "eagle-import:C0603")
      (libsource (lib "eagle-import") (part "C-EUC0603"))
    )
    (comp (ref "C327")
      (value "1µF")
      (footprint "eagle-import:C0603")
      (libsource (lib "eagle-import") (part "C-EUC0603"))
    )
    (comp (ref "C328")
      (value "1µF")
      (footprint "eagle-import:C0603")
      (libsource (lib "eagle-import") (part "C-EUC0603"))
    )
    (comp (ref "C329")
      (value "0.1µF")
      (footprint "eagle-import:C0805")
      (libsource (lib "eagle-import") (part "C-EUC0805"))
    )
    (comp (ref "C330")
      (value "33nF")
      (footprint "eagle-import:C0805")
      (libsource (lib "eagle-import") (part "C-EUC0805"))
    )
    (comp (ref "C331")
      (value "33nF")
      (footprint "eagle-import:C0805")
      (libsource (lib "eagle-import") (part "C-EUC0805"))
    )
    (comp (ref "C332")
      (value "33nF")
      (footprint "eagle-import:C0805")
      (libsource (lib "eagle-import") (part "C-EUC0805"))
    )
    (comp (ref "C333")
      (value "33nF")
      (footprint "eagle-import:C0805")
      (libsource (lib "eagle-import") (part "C-EUC0805"))
    )
    (comp (ref "C334")
      (value "1µF 100V .5")
      (footprint "eagle-import:C1206")
      (libsource (lib "eagle-import") (part "C-EUC1206"))
    )
    (comp (ref "C335")
      (value "1µF 100V .5")
      (footprint "eagle-import:C1206")
      (libsource (lib "eagle-import") (part "C-EUC1206"))
    )
    (comp (ref "C336")
      (value "470µF 80V")
      (footprint "eagle-import:E5-13")
      (libsource (lib "eagle-import") (part "CPOL-EUE5-13"))
    )
    (comp (ref "C337")
      (value "1µF 100V .5")
      (footprint "eagle-import:C1206")
      (libsource (lib "eagle-import") (part "C-EUC1206"))
    )
    (comp (ref "C338")
      (value "1µF 100V .5")
      (footprint "eagle-import:C1206")
      (libsource (lib "eagle-import") (part "C-EUC1206"))
    )
    (comp (ref "C339")
      (value "470µF 80V")
      (footprint "eagle-import:E5-13")
      (libsource (lib "eagle-import") (part "CPOL-EUE5-13"))
    )
    (comp (ref "C340")
      (value "1µF 100V")
      (footprint "eagle-import:C1206")
      (libsource (lib "eagle-import") (part "C-EUC1206"))
    )
    (comp (ref "C341")
      (value "1nF 100V")
      (footprint "eagle-import:C0603")
      (libsource (lib "eagle-import") (part "C-EUC0603"))
    )
    (comp (ref "C342")
      (value "10nF")
      (footprint "eagle-import:C0603")
      (libsource (lib "eagle-import") (part "C-EUC0603"))
    )
    (comp (ref "C343")
      (value "1µF 100V")
      (footprint "eagle-import:C1206")
      (libsource (lib "eagle-import") (part "C-EUC1206"))
    )
    (comp (ref "C344")
      (value "1nF 100V")
      (footprint "eagle-import:C0603")
      (libsource (lib "eagle-import") (part "C-EUC0603"))
    )
    (comp (ref "C345")
      (value "10nF")
      (footprint "eagle-import:C0603")
      (libsource (lib "eagle-import") (part "C-EUC0603"))
    )
    (comp (ref "C346")
      (value "1µF 100V")
      (footprint "eagle-import:C1206")
      (libsource (lib "eagle-import") (part "C-EUC1206"))
    )
    (comp (ref "C347")
      (value "1nF 100V")
      (footprint "eagle-import:C0603")
      (libsource (lib "eagle-import") (part "C-EUC0603"))
    )
    (comp (ref "C348")
      (value "10nF")
      (footprint "eagle-import:C0603")
      (libsource (lib "eagle-import") (part "C-EUC0603"))
    )
    (comp (ref "C349")
      (value "1µF 100V")
      (footprint "eagle-import:C1206")
      (libsource (lib "eagle-import") (part "C-EUC1206"))
    )
    (comp (ref "C350")
      (value "1nF 100V")
      (footprint "eagle-import:C0603")
      (libsource (lib "eagle-import") (part "C-EUC0603"))
    )
    (comp (ref "C351")
      (value "10nF")
      (footprint "eagle-import:C0603")
      (libsource (lib "eagle-import") (part "C-EUC0603"))
    )
    (comp (ref "C352")
      (value "470µF 80V")
      (footprint "eagle-import:E5-13")
      (libsource (lib "eagle-import") (part "CPOL-EUE5-13"))
    )
    (comp (ref "C353")
      (value "470µF 80V")
      (footprint "eagle-import:E5-13")
      (libsource (lib "eagle-import") (part "CPOL-EUE5-13"))
    )
    (comp (ref "C354")
      (value "10µF")
      (footprint "eagle-import:C0805")
      (libsource (lib "eagle-import") (part "C-EUC0805"))
    )
    (comp (ref "C355")
      (value "10µF")
      (footprint "eagle-import:C0805")
      (libsource (lib "eagle-import") (part "C-EUC0805"))
    )
    (comp (ref "C356")
      (value "10µF")
      (footprint "eagle-import:C0805")
      (libsource (lib "eagle-import") (part "C-EUC0805"))
    )
    (comp (ref "C357")
      (value "10µF")
      (footprint "eagle-import:C0805")
      (libsource (lib "eagle-import") (part "C-EUC0805"))
    )
    (comp (ref "C358")
      (value "2.2µF")
      (footprint "eagle-import:C0603")
      (libsource (lib "eagle-import") (part "C-EUC0603"))
    )
    (comp (ref "DN300")
      (value "MD_S")
      (footprint "eagle-import:MD-S-4")
      (libsource (lib "eagle-import") (part "MD_S"))
    )
    (comp (ref "F300")
      (value "2A")
      (footprint "eagle-import:MRF_FUSE")
      (libsource (lib "eagle-import") (part "MRF_FUSE"))
    )
    (comp (ref "F301")
      (value "1A")
      (footprint "eagle-import:MRF_FUSE")
      (libsource (lib "eagle-import") (part "MRF_FUSE"))
    )
    (comp (ref "F302")
      (value "1A")
      (footprint "eagle-import:MRF_FUSE")
      (libsource (lib "eagle-import") (part "MRF_FUSE"))
    )
    (comp (ref "FAN300")
      (value "12V <50mA")
      (footprint "eagle-import:WIRE-2P-SIMPLE")
      (libsource (lib "eagle-import") (part "WIRED-FAN"))
    )
    (comp (ref "H300")
      (value "ATS-CPX030030030-173-C2-R0")
      (footprint "eagle-import:ATS-CPX030030030-173-C2-R0")
      (libsource (lib "eagle-import") (part "ATS-CPX030030030-173-C2-R0"))
    )
    (comp (ref "L300")
      (value "10µH")
      (footprint "eagle-import:RCH8011")
      (libsource (lib "eagle-import") (part "RCH8011"))
    )
    (comp (ref "L301")
      (value "10µH")
      (footprint "eagle-import:RCH8011")
      (libsource (lib "eagle-import") (part "RCH8011"))
    )
    (comp (ref "L302")
      (value "15µH")
      (footprint "eagle-import:RCH8011")
      (libsource (lib "eagle-import") (part "RCH8011"))
    )
    (comp (ref "L303")
      (value "15µH")
      (footprint "eagle-import:RCH8011")
      (libsource (lib "eagle-import") (part "RCH8011"))
    )
    (comp (ref "Q300")
      (value "NMOS")
      (footprint "eagle-import:SOT23")
      (libsource (lib "eagle-import") (part "SOT23-N-MOSFET"))
    )
    (comp (ref "R300")
      (value "510Ω")
      (footprint "eagle-import:R0603")
      (libsource (lib "eagle-import") (part "R-US_R0603"))
    )
    (comp (ref "R301")
      (value "10kΩ")
      (footprint "eagle-import:R0805")
      (libsource (lib "eagle-import") (part "R-US_R0805"))
    )
    (comp (ref "R302")
      (value "39kΩ")
      (footprint "eagle-import:R0603")
      (libsource (lib "eagle-import") (part "R-US_R0603"))
    )
    (comp (ref "R303")
      (value "47Ω?")
      (footprint "eagle-import:R0603")
      (libsource (lib "eagle-import") (part "R-US_R0603"))
    )
    (comp (ref "R304")
      (value "10kΩ")
      (footprint "eagle-import:R0805")
      (libsource (lib "eagle-import") (part "R-US_R0805"))
    )
    (comp (ref "R305")
      (value "10kΩ")
      (footprint "eagle-import:R0805")
      (libsource (lib "eagle-import") (part "R-US_R0805"))
    )
    (comp (ref "R306")
      (value "10kΩ")
      (footprint "eagle-import:R0805")
      (libsource (lib "eagle-import") (part "R-US_R0805"))
    )
    (comp (ref "R307")
      (value "10kΩ")
      (footprint "eagle-import:R0805")
      (libsource (lib "eagle-import") (part "R-US_R0805"))
    )
    (comp (ref "R308")
      (value "10kΩ")
      (footprint "eagle-import:R0805")
      (libsource (lib "eagle-import") (part "R-US_R0805"))
    )
    (comp (ref "R309")
      (value "10kΩ")
      (footprint "eagle-import:R0805")
      (libsource (lib "eagle-import") (part "R-US_R0805"))
    )
    (comp (ref "R310")
      (value "200kΩ")
      (footprint "eagle-import:R0603")
      (libsource (lib "eagle-import") (part "R-US_R0603"))
    )
    (comp (ref "R311")
      (value "24.3kΩ")
      (footprint "eagle-import:R0603")
      (libsource (lib "eagle-import") (part "R-US_R0603"))
    )
    (comp (ref "R312")
      (value "237kΩ")
      (footprint "eagle-import:R0603")
      (libsource (lib "eagle-import") (part "R-US_R0603"))
    )
    (comp (ref "R313")
      (value "66.5kΩ")
      (footprint "eagle-import:R0603")
      (libsource (lib "eagle-import") (part "R-US_R0603"))
    )
    (comp (ref "R314")
      (value "10kΩ")
      (footprint "eagle-import:R0805")
      (libsource (lib "eagle-import") (part "R-US_R0805"))
    )
    (comp (ref "R315")
      (value "4.53kΩ")
      (footprint "eagle-import:R0603")
      (libsource (lib "eagle-import") (part "R-US_R0603"))
    )
    (comp (ref "R316")
      (value "10kΩ")
      (footprint "eagle-import:R0805")
      (libsource (lib "eagle-import") (part "R-US_R0805"))
    )
    (comp (ref "R317")
      (value "10kΩ")
      (footprint "eagle-import:R0805")
      (libsource (lib "eagle-import") (part "R-US_R0805"))
    )
    (comp (ref "R318")
      (value "86.6kΩ")
      (footprint "eagle-import:R0603")
      (libsource (lib "eagle-import") (part "R-US_R0603"))
    )
    (comp (ref "R319")
      (value "54.9kΩ")
      (footprint "eagle-import:R0603")
      (libsource (lib "eagle-import") (part "R-US_R0603"))
    )
    (comp (ref "R320")
      (value "210kΩ")
      (footprint "eagle-import:R0603")
      (libsource (lib "eagle-import") (part "R-US_R0603"))
    )
    (comp (ref "R321")
      (value "22.6kΩ")
      (footprint "eagle-import:R0603")
      (libsource (lib "eagle-import") (part "R-US_R0603"))
    )
    (comp (ref "R322")
      (value "10kΩ")
      (footprint "eagle-import:R0805")
      (libsource (lib "eagle-import") (part "R-US_R0805"))
    )
    (comp (ref "R323")
      (value "10kΩ")
      (footprint "eagle-import:R0805")
      (libsource (lib "eagle-import") (part "R-US_R0805"))
    )
    (comp (ref "R324")
      (value "86.6kΩ")
      (footprint "eagle-import:R0603")
      (libsource (lib "eagle-import") (part "R-US_R0603"))
    )
    (comp (ref "R325")
      (value "54.9kΩ")
      (footprint "eagle-import:R0603")
      (libsource (lib "eagle-import") (part "R-US_R0603"))
    )
    (comp (ref "R326")
      (value "210kΩ")
      (footprint "eagle-import:R0603")
      (libsource (lib "eagle-import") (part "R-US_R0603"))
    )
    (comp (ref "R327")
      (value "22.6kΩ")
      (footprint "eagle-import:R0603")
      (libsource (lib "eagle-import") (part "R-US_R0603"))
    )
    (comp (ref "R328")
      (value "10kΩ")
      (footprint "eagle-import:R0805")
      (libsource (lib "eagle-import") (part "R-US_R0805"))
    )
    (comp (ref "R329")
      (value "10kΩ")
      (footprint "eagle-import:R0805")
      (libsource (lib "eagle-import") (part "R-US_R0805"))
    )
    (comp (ref "R330")
      (value "3.3Ω")
      (footprint "eagle-import:R0805")
      (libsource (lib "eagle-import") (part "R-US_R0805"))
    )
    (comp (ref "R331")
      (value "3.3Ω")
      (footprint "eagle-import:R0805")
      (libsource (lib "eagle-import") (part "R-US_R0805"))
    )
    (comp (ref "R332")
      (value "64.9kΩ")
      (footprint "eagle-import:R0603")
      (libsource (lib "eagle-import") (part "R-US_R0603"))
    )
    (comp (ref "R333")
      (value "30kΩ")
      (footprint "eagle-import:R0603")
      (libsource (lib "eagle-import") (part "R-US_R0603"))
    )
    (comp (ref "R334")
      (value "3.3Ω")
      (footprint "eagle-import:R0805")
      (libsource (lib "eagle-import") (part "R-US_R0805"))
    )
    (comp (ref "R335")
      (value "3.3Ω")
      (footprint "eagle-import:R0805")
      (libsource (lib "eagle-import") (part "R-US_R0805"))
    )
    (comp (ref "R336")
      (value "3.3Ω")
      (footprint "eagle-import:R0805")
      (libsource (lib "eagle-import") (part "R-US_R0805"))
    )
    (comp (ref "R337")
      (value "3.3Ω")
      (footprint "eagle-import:R0805")
      (libsource (lib "eagle-import") (part "R-US_R0805"))
    )
    (comp (ref "R338")
      (value "10kΩ")
      (footprint "eagle-import:R0805")
      (libsource (lib "eagle-import") (part "R-US_R0805"))
    )
    (comp (ref "R339")
      (value "10kΩ")
      (footprint "eagle-import:R0805")
      (libsource (lib "eagle-import") (part "R-US_R0805"))
    )
    (comp (ref "R340")
      (value "10kΩ")
      (footprint "eagle-import:R0805")
      (libsource (lib "eagle-import") (part "R-US_R0805"))
    )
    (comp (ref "R341")
      (value "10kΩ")
      (footprint "eagle-import:R0805")
      (libsource (lib "eagle-import") (part "R-US_R0805"))
    )
    (comp (ref "R342")
      (value "1kΩ")
      (footprint "eagle-import:R0805")
      (libsource (lib "eagle-import") (part "R-US_R0805"))
    )
    (comp (ref "R343")
      (value "10kΩ")
      (footprint "eagle-import:R0805")
      (libsource (lib "eagle-import") (part "R-US_R0805"))
    )
    (comp (ref "R344")
      (value "10kΩ")
      (footprint "eagle-import:R0805")
      (libsource (lib "eagle-import") (part "R-US_R0805"))
    )
    (comp (ref "R345")
      (value "20kΩ")
      (footprint "eagle-import:R0603")
      (libsource (lib "eagle-import") (part "R-US_R0603"))
    )
    (comp (ref "R346")
      (value "10kΩ")
      (footprint "eagle-import:R0805")
      (libsource (lib "eagle-import") (part "R-US_R0805"))
    )
    (comp (ref "R347")
      (value "20kΩ")
      (footprint "eagle-import:R0603")
      (libsource (lib "eagle-import") (part "R-US_R0603"))
    )
    (comp (ref "R348")
      (value "10kΩ")
      (footprint "eagle-import:R0805")
      (libsource (lib "eagle-import") (part "R-US_R0805"))
    )
    (comp (ref "RT300")
      (value "103AT")
      (footprint "eagle-import:WIRE-2P-SIMPLE")
      (libsource (lib "eagle-import") (part "WIRED-THERMISTOR"))
    )
    (comp (ref "RV300")
      (value "20kΩ")
      (footprint "eagle-import:TC33X-2")
      (libsource (lib "eagle-import") (part "TC33X-2"))
    )
    (comp (ref "RV301")
      (value "10kΩ")
      (footprint "eagle-import:TC33X-2")
      (libsource (lib "eagle-import") (part "TC33X-2"))
    )
    (comp (ref "RV302")
      (value "10kΩ")
      (footprint "eagle-import:TC33X-2")
      (libsource (lib "eagle-import") (part "TC33X-2"))
    )
    (comp (ref "RV303")
      (value "20kΩ")
      (footprint "eagle-import:TC33X-2")
      (libsource (lib "eagle-import") (part "TC33X-2"))
    )
    (comp (ref "U300")
      (value "TPA3255")
      (footprint "eagle-import:TSSOP44")
      (libsource (lib "eagle-import") (part "TPA3255"))
    )
    (comp (ref "U301")
      (value "NCS20071")
      (footprint "eagle-import:TSOP-5")
      (libsource (lib "eagle-import") (part "NCS20071"))
    )
    (comp (ref "U302")
      (value "LM2902")
      (footprint "eagle-import:TSSOP14")
      (libsource (lib "eagle-import") (part "LM2902"))
    )
    (comp (ref "U303")
      (value "LM2902")
      (footprint "eagle-import:TSSOP14")
      (libsource (lib "eagle-import") (part "LM2902"))
    )
    (comp (ref "U304")
      (value "LM2902")
      (footprint "eagle-import:TSSOP14")
      (libsource (lib "eagle-import") (part "LM2902"))
    )
    (comp (ref "U305")
      (value "LM2904")
      (footprint "eagle-import:MSOP8")
      (libsource (lib "eagle-import") (part "LM2904"))
    )
    (comp (ref "U306")
      (value "NCS20071")
      (footprint "eagle-import:TSOP-5")
      (libsource (lib "eagle-import") (part "NCS20071"))
    )
    (comp (ref "XLS300")
      (value "BASS")
      (footprint "eagle-import:TE-770966")
      (libsource (lib "eagle-import") (part "SPEAKER-CONN"))
    )
    (comp (ref "XLS301")
      (value "LEFT")
      (footprint "eagle-import:TE-770966")
      (libsource (lib "eagle-import") (part "SPEAKER-CONN"))
    )
    (comp (ref "XLS302")
      (value "RIGHT")
      (footprint "eagle-import:TE-770966")
      (libsource (lib "eagle-import") (part "SPEAKER-CONN"))
    )
    (comp (ref "A400")
      (value "BM62")
      (footprint "eagle-import:BM62")
      (libsource (lib "eagle-import") (part "BM62"))
    )
    (comp (ref "C400")
      (value "0.1µF")
      (footprint "eagle-import:C0805")
      (libsource (lib "eagle-import") (part "C-EUC0805"))
    )
    (comp (ref "C401")
      (value "0.1µF")
      (footprint "eagle-import:C0805")
      (libsource (lib "eagle-import") (part "C-EUC0805"))
    )
    (comp (ref "C402")
      (value "0.1µF")
      (footprint "eagle-import:C0805")
      (libsource (lib "eagle-import") (part "C-EUC0805"))
    )
    (comp (ref "C403")
      (value "15pF")
      (footprint "eagle-import:C0603")
      (libsource (lib "eagle-import") (part "C-EUC0603"))
    )
    (comp (ref "C404")
      (value "15pF")
      (footprint "eagle-import:C0603")
      (libsource (lib "eagle-import") (part "C-EUC0603"))
    )
    (comp (ref "C405")
      (value "15pF")
      (footprint "eagle-import:C0603")
      (libsource (lib "eagle-import") (part "C-EUC0603"))
    )
    (comp (ref "C406")
      (value "15pF")
      (footprint "eagle-import:C0603")
      (libsource (lib "eagle-import") (part "C-EUC0603"))
    )
    (comp (ref "C407")
      (value "15pF")
      (footprint "eagle-import:C0603")
      (libsource (lib "eagle-import") (part "C-EUC0603"))
    )
    (comp (ref "C409")
      (value "0.1µF")
      (footprint "eagle-import:C0805")
      (libsource (lib "eagle-import") (part "C-EUC0805"))
    )
    (comp (ref "C410")
      (value "0.1µF?")
      (footprint "eagle-import:C0805")
      (libsource (lib "eagle-import") (part "C-EUC0805"))
    )
    (comp (ref "C411")
      (value "0.1µF?")
      (footprint "eagle-import:C0805")
      (libsource (lib "eagle-import") (part "C-EUC0805"))
    )
    (comp (ref "D400")
      (value "D5V0L2B3SO")
      (footprint "eagle-import:SOT23")
      (libsource (lib "eagle-import") (part "SOT23-TVS"))
    )
    (comp (ref "J400")
      (value "ICSP")
      (footprint "eagle-import:1X08")
      (libsource (lib "eagle-import") (part "PINHD-1X8"))
    )
    (comp (ref "J401")
      (value "ZX62D-B-5PA8")
      (footprint "eagle-import:ZX62D-B-5PA8")
      (libsource (lib "eagle-import") (part "ZX62D-B-5PA8"))
    )
    (comp (ref "J402")
      (value "AUX")
      (footprint "eagle-import:3PIN")
      (libsource (lib "eagle-import") (part "GEN-3PIN"))
    )
    (comp (ref "J403")
      (value "LED")
      (footprint "eagle-import:4PIN")
      (libsource (lib "eagle-import") (part "GEN-4PIN"))
    )
    (comp (ref "J404")
      (value "SWLED")
      (footprint "eagle-import:3PIN")
      (libsource (lib "eagle-import") (part "GEN-3PIN"))
    )
    (comp (ref "J405")
      (value "USB1")
      (footprint "eagle-import:2PIN")
      (libsource (lib "eagle-import") (part "GEN-2PIN"))
    )
    (comp (ref "J406")
      (value "USB2")
      (footprint "eagle-import:2PIN")
      (libsource (lib "eagle-import") (part "GEN-2PIN"))
    )
    (comp (ref "Q400")
      (value "NMOS")
      (footprint "eagle-import:SOT23")
      (libsource (lib "eagle-import") (part "SOT23-N-MOSFET"))
    )
    (comp (ref "Q401")
      (value "NMOS")
      (footprint "eagle-import:SOT23")
      (libsource (lib "eagle-import") (part "SOT23-N-MOSFET"))
    )
    (comp (ref "Q402")
      (value "NMOS")
      (footprint "eagle-import:SOT23")
      (libsource (lib "eagle-import") (part "SOT23-N-MOSFET"))
    )
    (comp (ref "Q403")
      (value "DMG2302UK")
      (footprint "eagle-import:SOT23")
      (libsource (lib "eagle-import") (part "SOT23-N-MOSFET"))
    )
    (comp (ref "Q404")
      (value "DMG2302UK")
      (footprint "eagle-import:SOT23")
      (libsource (lib "eagle-import") (part "SOT23-N-MOSFET"))
    )
    (comp (ref "Q405")
      (value "DMG2302UK")
      (footprint "eagle-import:SOT23")
      (libsource (lib "eagle-import") (part "SOT23-N-MOSFET"))
    )
    (comp (ref "Q406")
      (value "NMOS")
      (footprint "eagle-import:SOT23")
      (libsource (lib "eagle-import") (part "SOT23-N-MOSFET"))
    )
    (comp (ref "Q407")
      (value "NMOS")
      (footprint "eagle-import:SOT23")
      (libsource (lib "eagle-import") (part "SOT23-N-MOSFET"))
    )
    (comp (ref "R400")
      (value "330Ω")
      (footprint "eagle-import:R0805")
      (libsource (lib "eagle-import") (part "R-US_R0805"))
    )
    (comp (ref "R401")
      (value "10kΩ")
      (footprint "eagle-import:R0805")
      (libsource (lib "eagle-import") (part "R-US_R0805"))
    )
    (comp (ref "R402")
      (value "10kΩ")
      (footprint "eagle-import:R0805")
      (libsource (lib "eagle-import") (part "R-US_R0805"))
    )
    (comp (ref "R403")
      (value "10kΩ")
      (footprint "eagle-import:R0805")
      (libsource (lib "eagle-import") (part "R-US_R0805"))
    )
    (comp (ref "R404")
      (value "10kΩ")
      (footprint "eagle-import:R0805")
      (libsource (lib "eagle-import") (part "R-US_R0805"))
    )
    (comp (ref "R405")
      (value "10kΩ")
      (footprint "eagle-import:R0805")
      (libsource (lib "eagle-import") (part "R-US_R0805"))
    )
    (comp (ref "R406")
      (value "10kΩ")
      (footprint "eagle-import:R0805")
      (libsource (lib "eagle-import") (part "R-US_R0805"))
    )
    (comp (ref "R407")
      (value "1.69kΩ")
      (footprint "eagle-import:R0603")
      (libsource (lib "eagle-import") (part "R-US_R0603"))
    )
    (comp (ref "R408")
      (value "47Ω?")
      (footprint "eagle-import:R0603")
      (libsource (lib "eagle-import") (part "R-US_R0603"))
    )
    (comp (ref "R409")
      (value "47Ω?")
      (footprint "eagle-import:R0603")
      (libsource (lib "eagle-import") (part "R-US_R0603"))
    )
    (comp (ref "RV400")
      (value "10kΩ")
      (footprint "eagle-import:TC33X-2")
      (libsource (lib "eagle-import") (part "TC33X-2"))
    )
    (comp (ref "RV401")
      (value "100kΩ")
      (footprint "eagle-import:WIRE-3P-SIMPLE")
      (libsource (lib "eagle-import") (part "WIRED-POTENTIOMETER"))
    )
    (comp (ref "SJ400")
      (value "3.3V-5V")
      (footprint "eagle-import:SJ_2")
      (libsource (lib "eagle-import") (part "SJ2W"))
    )
    (comp (ref "SJ401")
      (value "ADAP")
      (footprint "eagle-import:SJ")
      (libsource (lib "eagle-import") (part "SJ"))
    )
    (comp (ref "SJ402")
      (value "VBUS")
      (footprint "eagle-import:SJ")
      (libsource (lib "eagle-import") (part "SJ"))
    )
    (comp (ref "SJ403")
      (value "FTRESET")
      (footprint "eagle-import:SJ")
      (libsource (lib "eagle-import") (part "SJ"))
    )
    (comp (ref "SJ404")
      (value "GND CUT")
      (footprint "eagle-import:SJ")
      (libsource (lib "eagle-import") (part "SJ"))
    )
    (comp (ref "SW400")
      (value "DIPSW-SPDT-5")
      (footprint "eagle-import:DIPSW-10")
      (libsource (lib "eagle-import") (part "DIPSW-SPDT-5"))
    )
    (comp (ref "SW401")
      (value "MFB")
      (footprint "eagle-import:WIRE-2P-SIMPLE")
      (libsource (lib "eagle-import") (part "WIRED-SWITCH-NO"))
    )
    (comp (ref "SW402")
      (value "BTN1")
      (footprint "eagle-import:WIRE-2P-SIMPLE")
      (libsource (lib "eagle-import") (part "WIRED-SWITCH-NO"))
    )
    (comp (ref "SW403")
      (value "BTN2")
      (footprint "eagle-import:WIRE-2P-SIMPLE")
      (libsource (lib "eagle-import") (part "WIRED-SWITCH-NO"))
    )
    (comp (ref "SW404")
      (value "BTN3")
      (footprint "eagle-import:WIRE-2P-SIMPLE")
      (libsource (lib "eagle-import") (part "WIRED-SWITCH-NO"))
    )
    (comp (ref "SW405")
      (value "BTN4")
      (footprint "eagle-import:WIRE-2P-SIMPLE")
      (libsource (lib "eagle-import") (part "WIRED-SWITCH-NO"))
    )
    (comp (ref "SW406")
      (value "BTN5")
      (footprint "eagle-import:WIRE-2P-SIMPLE")
      (libsource (lib "eagle-import") (part "WIRED-SWITCH-NO"))
    )
    (comp (ref "SW407")
      (value "RESET")
      (footprint "eagle-import:WIRE-2P-SIMPLE")
      (libsource (lib "eagle-import") (part "WIRED-SWITCH-NO"))
    )
    (comp (ref "SW408")
      (value "LCDBL")
      (footprint "eagle-import:WIRE-2P-SIMPLE")
      (libsource (lib "eagle-import") (part "WIRED-SWITCH-NO"))
    )
    (comp (ref "U400")
      (value "PIC18LF4_K42")
      (footprint "eagle-import:TQFP44")
      (libsource (lib "eagle-import") (part "PIC184_K42LF"))
    )
    (comp (ref "U401")
      (value "FT230XS")
      (footprint "eagle-import:SSOP16")
      (libsource (lib "eagle-import") (part "FT230XS"))
    )
    (comp (ref "U402")
      (value "NCS20071")
      (footprint "eagle-import:TSOP-5")
      (libsource (lib "eagle-import") (part "NCS20071"))
    )
    (comp (ref "XDS400")
      (value "HD44780_LCD-CON")
      (footprint "eagle-import:2X8PIN")
      (libsource (lib "eagle-import") (part "HD44780_LCD-CON"))
    )
  )
  (nets
    (net (code "1") (name "3.3V") (class "Default")
      (node (ref "C216") (pin "1") (pinfunction "1_1") (pintype "passive"))
      (node (ref "C400") (pin "1") (pinfunction "1_1") (pintype "passive"))
      (node (ref "C401") (pin "1") (pinfunction "1_1") (pintype "passive"))
      (node (ref "C409") (pin "1") (pinfunction "1_1") (pintype "passive"))
      (node (ref "J400") (pin "2") (pinfunction "2_2") (pintype "passive"))
      (node (ref "R401") (pin "2") (pinfunction "2_2") (pintype "passive"))
      (node (ref "R404") (pin "1") (pinfunction "1_1") (pintype "passive"))
      (node (ref "RV400") (pin "3") (pinfunction "E_3") (pintype "passive"))
      (node (ref "RV401") (pin "3") (pinfunction "E_3") (pintype "passive"))
      (node (ref "SJ400") (pin "1") (pinfunction "1_1") (pintype "passive"))
      (node (ref "U203") (pin "5") (pinfunction "OUT_5") (pintype "bidirectional"))
      (node (ref "U306") (pin "5") (pinfunction "V+_5") (pintype "power_in"))
      (node (ref "U400") (pin "28") (pinfunction "VDD_28") (pintype "bidirectional"))
      (node (ref "U400") (pin "7") (pinfunction "VDD_7") (pintype "bidirectional"))
      (node (ref "U401") (pin "10") (pinfunction "3V3OUT_10") (pintype "output"))
      (node (ref "U401") (pin "12") (pinfunction "VCC_12") (pintype "power_in"))
      (node (ref "U401") (pin "3") (pinfunction "VCCIO_3") (pintype "power_in"))
      (node (ref "U402") (pin "5") (pinfunction "V+_5") (pintype "power_in"))
      (node (ref "XDS400") (pin "2") (pinfunction "VDD_2") (pintype "bidirectional"))
    )
    (net (code "2") (name "3.8V") (class "Default")
      (node (ref "A400") (pin "21") (pinfunction "BAT_IN_21") (pintype "bidirectional"))
      (node (ref "C218") (pin "1") (pinfunction "1_1") (pintype "passive"))
      (node (ref "U204") (pin "5") (pinfunction "OUT_5") (pintype "bidirectional"))
    )
    (net (code "3") (name "5V") (class "Default")
      (node (ref "C215") (pin "1") (pinfunction "1_1") (pintype "passive"))
      (node (ref "C217") (pin "1") (pinfunction "1_1") (pintype "passive"))
      (node (ref "C226") (pin "1") (pinfunction "1_1") (pintype "passive"))
      (node (ref "C227") (pin "+") (pinfunction "+_+") (pintype "passive"))
      (node (ref "J404") (pin "1") (pinfunction "P$1_1") (pintype "bidirectional"))
      (node (ref "J405") (pin "1") (pinfunction "P$1_1") (pintype "bidirectional"))
      (node (ref "J406") (pin "1") (pinfunction "P$1_1") (pintype "bidirectional"))
      (node (ref "L202") (pin "2") (pinfunction "2_2") (pintype "passive"))
      (node (ref "R218") (pin "2") (pinfunction "2_2") (pintype "passive"))
      (node (ref "SJ400") (pin "3") (pinfunction "3_3") (pintype "passive"))
      (node (ref "SJ401") (pin "1") (pinfunction "1_1") (pintype "passive"))
      (node (ref "U203") (pin "1") (pinfunction "IN_1") (pintype "bidirectional"))
      (node (ref "U203") (pin "3") (pinfunction "EN_3") (pintype "bidirectional"))
      (node (ref "U204") (pin "1") (pinfunction "IN_1") (pintype "bidirectional"))
      (node (ref "U204") (pin "3") (pinfunction "EN_3") (pintype "bidirectional"))
    )
    (net (code "4") (name "6V") (class "Default")
      (node (ref "C300") (pin "1") (pinfunction "1_1") (pintype "passive"))
      (node (ref "C303") (pin "1") (pinfunction "1_1") (pintype "passive"))
      (node (ref "C305") (pin "1") (pinfunction "1_1") (pintype "passive"))
      (node (ref "R304") (pin "1") (pinfunction "1_1") (pintype "passive"))
      (node (ref "R305") (pin "2") (pinfunction "2_2") (pintype "passive"))
      (node (ref "R318") (pin "1") (pinfunction "1_1") (pintype "passive"))
      (node (ref "R320") (pin "1") (pinfunction "1_1") (pintype "passive"))
      (node (ref "R324") (pin "1") (pinfunction "1_1") (pintype "passive"))
      (node (ref "R326") (pin "1") (pinfunction "1_1") (pintype "passive"))
      (node (ref "U302") (pin "3") (pinfunction "+IN_3") (pintype "input"))
      (node (ref "U302") (pin "5") (pinfunction "+IN_5") (pintype "input"))
      (node (ref "U303") (pin "10") (pinfunction "+IN_10") (pintype "input"))
      (node (ref "U303") (pin "12") (pinfunction "+IN_12") (pintype "input"))
      (node (ref "U304") (pin "10") (pinfunction "+IN_10") (pintype "input"))
      (node (ref "U304") (pin "5") (pinfunction "+IN_5") (pintype "input"))
      (node (ref "U305") (pin "3") (pinfunction "+IN_3") (pintype "input"))
      (node (ref "U305") (pin "5") (pinfunction "+IN_5") (pintype "input"))
    )
    (net (code "5") (name "12V") (class "Default")
      (node (ref "C211") (pin "1") (pinfunction "1_1") (pintype "passive"))
      (node (ref "C212") (pin "+") (pinfunction "+_+") (pintype "passive"))
      (node (ref "C228") (pin "+") (pinfunction "+_+") (pintype "passive"))
      (node (ref "C322") (pin "+") (pinfunction "+_+") (pintype "passive"))
      (node (ref "C323") (pin "1") (pinfunction "1_1") (pintype "passive"))
      (node (ref "D201") (pin "C") (pinfunction "C_C") (pintype "passive"))
      (node (ref "J403") (pin "1") (pinfunction "P$1_1") (pintype "bidirectional"))
      (node (ref "R213") (pin "2") (pinfunction "2_2") (pintype "passive"))
      (node (ref "R304") (pin "2") (pinfunction "2_2") (pintype "passive"))
      (node (ref "R330") (pin "1") (pinfunction "1_1") (pintype "passive"))
      (node (ref "R331") (pin "1") (pinfunction "1_1") (pintype "passive"))
      (node (ref "RT300") (pin "1") (pinfunction "1_1") (pintype "bidirectional"))
      (node (ref "U300") (pin "2") (pinfunction "VDD_2") (pintype "bidirectional"))
      (node (ref "U301") (pin "5") (pinfunction "V+_5") (pintype "power_in"))
      (node (ref "U302") (pin "4") (pinfunction "V+_4") (pintype "power_in"))
      (node (ref "U303") (pin "4") (pinfunction "V+_4") (pintype "power_in"))
      (node (ref "U304") (pin "4") (pinfunction "V+_4") (pintype "power_in"))
      (node (ref "U305") (pin "8") (pinfunction "V+_8") (pintype "power_in"))
    )
    (net (code "6") (name "52V") (class "Default")
      (node (ref "C201") (pin "+") (pinfunction "+_+") (pintype "passive"))
      (node (ref "C202") (pin "+") (pinfunction "+_+") (pintype "passive"))
      (node (ref "C203") (pin "+") (pinfunction "+_+") (pintype "passive"))
      (node (ref "C210") (pin "1") (pinfunction "1_1") (pintype "passive"))
      (node (ref "C334") (pin "1") (pinfunction "1_1") (pintype "passive"))
      (node (ref "C335") (pin "1") (pinfunction "1_1") (pintype "passive"))
      (node (ref "C336") (pin "+") (pinfunction "+_+") (pintype "passive"))
      (node (ref "C337") (pin "1") (pinfunction "1_1") (pintype "passive"))
      (node (ref "C338") (pin "1") (pinfunction "1_1") (pintype "passive"))
      (node (ref "C339") (pin "+") (pinfunction "+_+") (pintype "passive"))
      (node (ref "D200") (pin "C") (pinfunction "C_C") (pintype "passive"))
      (node (ref "R207") (pin "2") (pinfunction "2_2") (pintype "passive"))
      (node (ref "U300") (pin "29") (pinfunction "PVDD_CD_29") (pintype "bidirectional"))
      (node (ref "U300") (pin "30") (pinfunction "PVDD_CD_30") (pintype "bidirectional"))
      (node (ref "U300") (pin "31") (pinfunction "PVDD_CD_31") (pintype "bidirectional"))
      (node (ref "U300") (pin "36") (pinfunction "PVDD_AB_36") (pintype "bidirectional"))
      (node (ref "U300") (pin "37") (pinfunction "PVDD_AB_37") (pintype "bidirectional"))
      (node (ref "U300") (pin "38") (pinfunction "PVDD_AB_38") (pintype "bidirectional"))
    )
    (net (code "7") (name "AMP_~{CLIP_OTW}") (class "Default")
      (node (ref "U300") (pin "21") (pinfunction "~{CLIP_OTW}_21") (pintype "bidirectional"))
      (node (ref "U400") (pin "37") (pinfunction "RC3_37") (pintype "bidirectional"))
    )
    (net (code "8") (name "AMP_~{FAULT}") (class "Default")
      (node (ref "U300") (pin "19") (pinfunction "~{FAULT}_19") (pintype "bidirectional"))
      (node (ref "U400") (pin "36") (pinfunction "RC2_36") (pintype "bidirectional"))
    )
    (net (code "9") (name "AMP_~{RESET}") (class "Default")
      (node (ref "Q401") (pin "3") (pinfunction "D_3") (pintype "passive"))
      (node (ref "Q402") (pin "3") (pinfunction "D_3") (pintype "passive"))
      (node (ref "R404") (pin "2") (pinfunction "2_2") (pintype "passive"))
      (node (ref "U300") (pin "18") (pinfunction "~{RESET}_18") (pintype "bidirectional"))
    )
    (net (code "10") (name "AUD_SRC_L") (class "Default")
      (node (ref "C301") (pin "1") (pinfunction "1_1") (pintype "passive"))
      (node (ref "C411") (pin "1") (pinfunction "1_1") (pintype "passive"))
      (node (ref "R409") (pin "1") (pinfunction "1_1") (pintype "passive"))
    )
    (net (code "11") (name "AUD_SRC_R") (class "Default")
      (node (ref "C302") (pin "1") (pinfunction "1_1") (pintype "passive"))
      (node (ref "C410") (pin "2") (pinfunction "2_2") (pintype "passive"))
      (node (ref "R408") (pin "1") (pinfunction "1_1") (pintype "passive"))
    )
    (net (code "12") (name "BAT-") (class "Default")
      (node (ref "C103") (pin "2") (pinfunction "2_2") (pintype "passive"))
      (node (ref "C104") (pin "2") (pinfunction "2_2") (pintype "passive"))
      (node (ref "C105") (pin "1") (pinfunction "1_1") (pintype "passive"))
      (node (ref "C107") (pin "1") (pinfunction "1_1") (pintype "passive"))
      (node (ref "C108") (pin "2") (pinfunction "2_2") (pintype "passive"))
      (node (ref "C109") (pin "2") (pinfunction "2_2") (pintype "passive"))
      (node (ref "R104") (pin "1") (pinfunction "1_1") (pintype "passive"))
      (node (ref "R105") (pin "1") (pinfunction "1_1") (pintype "passive"))
      (node (ref "R106") (pin "1") (pinfunction "1_1") (pintype "passive"))
      (node (ref "R115") (pin "2") (pinfunction "2_2") (pintype "passive"))
      (node (ref "U100") (pin "23") (pinfunction "CTRC_23") (pintype "bidirectional"))
      (node (ref "U100") (pin "24") (pinfunction "CTRD_24") (pintype "bidirectional"))
      (node (ref "U100") (pin "9") (pinfunction "VSS_9") (pintype "bidirectional"))
      (node (ref "XBT100") (pin "5") (pinfunction "-_5") (pintype "bidirectional"))
      (node (ref "XBT100") (pin "6") (pinfunction "-_6") (pintype "bidirectional"))
    )
    (net (code "13") (name "BAT_THERM") (class "Default")
      (node (ref "R114") (pin "2") (pinfunction "2_2") (pintype "passive"))
      (node (ref "U100") (pin "18") (pinfunction "TS_18") (pintype "bidirectional"))
      (node (ref "XBT100") (pin "8") (pinfunction "THERM1_8") (pintype "bidirectional"))
    )
    (net (code "14") (name "BM_P1_5") (class "Default")
      (node (ref "A400") (pin "5") (pinfunction "P1_5_5") (pintype "bidirectional"))
      (node (ref "Q402") (pin "1") (pinfunction "G_1") (pintype "passive"))
    )
    (net (code "15") (name "CHG_ISETIN") (class "Default")
      (node (ref "R123") (pin "1") (pinfunction "1_1") (pintype "passive"))
      (node (ref "R124") (pin "2") (pinfunction "2_2") (pintype "passive"))
      (node (ref "U101") (pin "2") (pinfunction "ISETIN_2") (pintype "bidirectional"))
    )
    (net (code "16") (name "CHG_ISETOUT") (class "Default")
      (node (ref "R125") (pin "1") (pinfunction "1_1") (pintype "passive"))
      (node (ref "R126") (pin "2") (pinfunction "2_2") (pintype "passive"))
      (node (ref "U101") (pin "3") (pinfunction "ISETOUT_3") (pintype "bidirectional"))
    )
    (net (code "17") (name "CHG_REF") (class "Default")
      (node (ref "C118") (pin "1") (pinfunction "1_1") (pintype "passive"))
      (node (ref "R120") (pin "2") (pinfunction "2_2") (pintype "passive"))
      (node (ref "R122") (pin "2") (pinfunction "2_2") (pintype "passive"))
      (node (ref "R125") (pin "2") (pinfunction "2_2") (pintype "passive"))
      (node (ref "U101") (pin "5") (pinfunction "REF_5") (pintype "bidirectional"))
    )
    (net (code "18") (name "CHG_VADJ") (class "Default")
      (node (ref "R120") (pin "1") (pinfunction "1_1") (pintype "passive"))
      (node (ref "R121") (pin "2") (pinfunction "2_2") (pintype "passive"))
      (node (ref "U101") (pin "8") (pinfunction "VADJ_8") (pintype "bidirectional"))
    )
    (net (code "19") (name "CHG_VL") (class "Default")
      (node (ref "C119") (pin "1") (pinfunction "1_1") (pintype "passive"))
      (node (ref "C120") (pin "1") (pinfunction "1_1") (pintype "passive"))
      (node (ref "U101") (pin "1") (pinfunction "VL_1") (pintype "bidirectional"))
      (node (ref "U101") (pin "12") (pinfunction "CELL_12") (pintype "bidirectional"))
    )
    (net (code "20") (name "CHG_~{FASTCHG}") (class "Default")
      (node (ref "U101") (pin "16") (pinfunction "~{FASTCHG}_16") (pintype "bidirectional"))
      (node (ref "U400") (pin "38") (pinfunction "RD0_38") (pintype "bidirectional"))
    )
    (net (code "21") (name "CHG_~{FAULT}") (class "Default")
      (node (ref "U101") (pin "15") (pinfunction "~{FAULT}_15") (pintype "bidirectional"))
      (node (ref "U400") (pin "40") (pinfunction "RD2_40") (pintype "bidirectional"))
    )
    (net (code "22") (name "CHG_~{FULLCHG}") (class "Default")
      (node (ref "U101") (pin "17") (pinfunction "~{FULLCHG}_17") (pintype "bidirectional"))
      (node (ref "U400") (pin "39") (pinfunction "RD1_39") (pintype "bidirectional"))
    )
    (net (code "23") (name "CHG_~{SHDN}") (class "Default")
      (node (ref "D102") (pin "1") (pinfunction "C_1") (pintype "passive"))
      (node (ref "R128") (pin "2") (pinfunction "2_2") (pintype "passive"))
      (node (ref "U101") (pin "18") (pinfunction "~{SHDN}_18") (pintype "bidirectional"))
    )
    (net (code "24") (name "GND") (class "Default")
      (node (ref "A400") (pin "23") (pinfunction "GND_23") (pintype "bidirectional"))
      (node (ref "A400") (pin "37") (pinfunction "GND_37") (pintype "bidirectional"))
      (node (ref "C111") (pin "2") (pinfunction "2_2") (pintype "passive"))
      (node (ref "C112") (pin "2") (pinfunction "2_2") (pintype "passive"))
      (node (ref "C113") (pin "2") (pinfunction "2_2") (pintype "passive"))
      (node (ref "C114") (pin "2") (pinfunction "2_2") (pintype "passive"))
      (node (ref "C115") (pin "2") (pinfunction "2_2") (pintype "passive"))
      (node (ref "C116") (pin "2") (pinfunction "2_2") (pintype "passive"))
      (node (ref "C117") (pin "2") (pinfunction "2_2") (pintype "passive"))
      (node (ref "C118") (pin "2") (pinfunction "2_2") (pintype "passive"))
      (node (ref "C119") (pin "2") (pinfunction "2_2") (pintype "passive"))
      (node (ref "C120") (pin "2") (pinfunction "2_2") (pintype "passive"))
      (node (ref "C121") (pin "2") (pinfunction "2_2") (pintype "passive"))
      (node (ref "C122") (pin "2") (pinfunction "2_2") (pintype "passive"))
      (node (ref "C123") (pin "2") (pinfunction "2_2") (pintype "passive"))
      (node (ref "C124") (pin "2") (pinfunction "2_2") (pintype "passive"))
      (node (ref "C125") (pin "2") (pinfunction "2_2") (pintype "passive"))
      (node (ref "C127") (pin "2") (pinfunction "2_2") (pintype "passive"))
      (node (ref "C128") (pin "2") (pinfunction "2_2") (pintype "passive"))
      (node (ref "C129") (pin "-") (pinfunction "-_-") (pintype "passive"))
      (node (ref "C130") (pin "-") (pinfunction "-_-") (pintype "passive"))
      (node (ref "C131") (pin "2") (pinfunction "2_2") (pintype "passive"))
      (node (ref "C132") (pin "2") (pinfunction "2_2") (pintype "passive"))
      (node (ref "C134") (pin "2") (pinfunction "2_2") (pintype "passive"))
      (node (ref "C135") (pin "2") (pinfunction "2_2") (pintype "passive"))
      (node (ref "C200") (pin "-") (pinfunction "-_-") (pintype "passive"))
      (node (ref "C201") (pin "-") (pinfunction "-_-") (pintype "passive"))
      (node (ref "C202") (pin "-") (pinfunction "-_-") (pintype "passive"))
      (node (ref "C203") (pin "-") (pinfunction "-_-") (pintype "passive"))
      (node (ref "C204") (pin "2") (pinfunction "2_2") (pintype "passive"))
      (node (ref "C205") (pin "2") (pinfunction "2_2") (pintype "passive"))
      (node (ref "C206") (pin "2") (pinfunction "2_2") (pintype "passive"))
      (node (ref "C209") (pin "2") (pinfunction "2_2") (pintype "passive"))
      (node (ref "C210") (pin "2") (pinfunction "2_2") (pintype "passive"))
      (node (ref "C211") (pin "2") (pinfunction "2_2") (pintype "passive"))
      (node (ref "C212") (pin "-") (pinfunction "-_-") (pintype "passive"))
      (node (ref "C213") (pin "2") (pinfunction "2_2") (pintype "passive"))
      (node (ref "C215") (pin "2") (pinfunction "2_2") (pintype "passive"))
      (node (ref "C216") (pin "2") (pinfunction "2_2") (pintype "passive"))
      (node (ref "C217") (pin "2") (pinfunction "2_2") (pintype "passive"))
      (node (ref "C218") (pin "2") (pinfunction "2_2") (pintype "passive"))
      (node (ref "C219") (pin "2") (pinfunction "2_2") (pintype "passive"))
      (node (ref "C220") (pin "2") (pinfunction "2_2") (pintype "passive"))
      (node (ref "C221") (pin "2") (pinfunction "2_2") (pintype "passive"))
      (node (ref "C222") (pin "2") (pinfunction "2_2") (pintype "passive"))
      (node (ref "C223") (pin "2") (pinfunction "2_2") (pintype "passive"))
      (node (ref "C227") (pin "-") (pinfunction "-_-") (pintype "passive"))
      (node (ref "C228") (pin "-") (pinfunction "-_-") (pintype "passive"))
      (node (ref "C300") (pin "2") (pinfunction "2_2") (pintype "passive"))
      (node (ref "C322") (pin "-") (pinfunction "-_-") (pintype "passive"))
      (node (ref "C323") (pin "2") (pinfunction "2_2") (pintype "passive"))
      (node (ref "C324") (pin "2") (pinfunction "2_2") (pintype "passive"))
      (node (ref "C325") (pin "2") (pinfunction "2_2") (pintype "passive"))
      (node (ref "C326") (pin "2") (pinfunction "2_2") (pintype "passive"))
      (node (ref "C327") (pin "2") (pinfunction "2_2") (pintype "passive"))
      (node (ref "C328") (pin "2") (pinfunction "2_2") (pintype "passive"))
      (node (ref "C329") (pin "2") (pinfunction "2_2") (pintype "passive"))
      (node (ref "C334") (pin "2") (pinfunction "2_2") (pintype "passive"))
      (node (ref "C335") (pin "2") (pinfunction "2_2") (pintype "passive"))
      (node (ref "C336") (pin "-") (pinfunction "-_-") (pintype "passive"))
      (node (ref "C337") (pin "2") (pinfunction "2_2") (pintype "passive"))
      (node (ref "C338") (pin "2") (pinfunction "2_2") (pintype "passive"))
      (node (ref "C339") (pin "-") (pinfunction "-_-") (pintype "passive"))
      (node (ref "C340") (pin "2") (pinfunction "2_2") (pintype "passive"))
      (node (ref "C341") (pin "2") (pinfunction "2_2") (pintype "passive"))
      (node (ref "C343") (pin "1") (pinfunction "1_1") (pintype "passive"))
      (node (ref "C344") (pin "1") (pinfunction "1_1") (pintype "passive"))
      (node (ref "C346") (pin "2") (pinfunction "2_2") (pintype "passive"))
      (node (ref "C347") (pin "2") (pinfunction "2_2") (pintype "passive"))
      (node (ref "C349") (pin "1") (pinfunction "1_1") (pintype "passive"))
      (node (ref "C350") (pin "1") (pinfunction "1_1") (pintype "passive"))
      (node (ref "C358") (pin "2") (pinfunction "2_2") (pintype "passive"))
      (node (ref "C400") (pin "2") (pinfunction "2_2") (pintype "passive"))
      (node (ref "C401") (pin "2") (pinfunction "2_2") (pintype "passive"))
      (node (ref "C402") (pin "2") (pinfunction "2_2") (pintype "passive"))
      (node (ref "C403") (pin "2") (pinfunction "2_2") (pintype "passive"))
      (node (ref "C404") (pin "2") (pinfunction "2_2") (pintype "passive"))
      (node (ref "C405") (pin "2") (pinfunction "2_2") (pintype "passive"))
      (node (ref "C406") (pin "2") (pinfunction "2_2") (pintype "passive"))
      (node (ref "C407") (pin "2") (pinfunction "2_2") (pintype "passive"))
      (node (ref "C409") (pin "2") (pinfunction "2_2") (pintype "passive"))
      (node (ref "C410") (pin "1") (pinfunction "1_1") (pintype "passive"))
      (node (ref "C411") (pin "2") (pinfunction "2_2") (pintype "passive"))
      (node (ref "D102") (pin "2") (pinfunction "A_2") (pintype "passive"))
      (node (ref "D103") (pin "A") (pinfunction "A_A") (pintype "passive"))
      (node (ref "D202") (pin "A") (pinfunction "A_A") (pintype "passive"))
      (node (ref "D400") (pin "3") (pinfunction "C_3") (pintype "passive"))
      (node (ref "DN300") (pin "~2") (pinfunction "AC2_~2") (pintype "passive"))
      (node (ref "H300") (pin "H1") (pinfunction "GND_H1") (pintype "bidirectional"))
      (node (ref "H300") (pin "H2") (pinfunction "GND_H2") (pintype "bidirectional"))
      (node (ref "J100") (pin "2") (pinfunction "2_2") (pintype "passive"))
      (node (ref "J400") (pin "3") (pinfunction "3_3") (pintype "passive"))
      (node (ref "J401") (pin "5") (pinfunction "GND_5") (pintype "passive"))
      (node (ref "J401") (pin "S1") (pinfunction "GND_S1") (pintype "passive"))
      (node (ref "J401") (pin "S2") (pinfunction "GND_S2") (pintype "passive"))
      (node (ref "J401") (pin "S3") (pinfunction "GND_S3") (pintype "passive"))
      (node (ref "J401") (pin "S4") (pinfunction "GND_S4") (pintype "passive"))
      (node (ref "J402") (pin "3") (pinfunction "P$1_3") (pintype "bidirectional"))
      (node (ref "J405") (pin "2") (pinfunction "P$1_2") (pintype "bidirectional"))
      (node (ref "J406") (pin "2") (pinfunction "P$1_2") (pintype "bidirectional"))
      (node (ref "L201") (pin "2") (pinfunction "S1_2") (pintype "passive"))
      (node (ref "Q101") (pin "S") (pinfunction "S_S") (pintype "passive"))
      (node (ref "Q103") (pin "S") (pinfunction "S_S") (pintype "passive"))
      (node (ref "Q300") (pin "2") (pinfunction "S_2") (pintype "passive"))
      (node (ref "Q400") (pin "2") (pinfunction "S_2") (pintype "passive"))
      (node (ref "Q401") (pin "2") (pinfunction "S_2") (pintype "passive"))
      (node (ref "Q402") (pin "2") (pinfunction "S_2") (pintype "passive"))
      (node (ref "Q403") (pin "2") (pinfunction "S_2") (pintype "passive"))
      (node (ref "Q404") (pin "2") (pinfunction "S_2") (pintype "passive"))
      (node (ref "Q405") (pin "2") (pinfunction "S_2") (pintype "passive"))
      (node (ref "Q406") (pin "2") (pinfunction "S_2") (pintype "passive"))
      (node (ref "Q407") (pin "2") (pinfunction "S_2") (pintype "passive"))
      (node (ref "R111") (pin "1") (pinfunction "1_1") (pintype "passive"))
      (node (ref "R112") (pin "1") (pinfunction "1_1") (pintype "passive"))
      (node (ref "R119") (pin "1") (pinfunction "1_1") (pintype "passive"))
      (node (ref "R121") (pin "1") (pinfunction "1_1") (pintype "passive"))
      (node (ref "R124") (pin "1") (pinfunction "1_1") (pintype "passive"))
      (node (ref "R126") (pin "1") (pinfunction "1_1") (pintype "passive"))
      (node (ref "R201") (pin "1") (pinfunction "1_1") (pintype "passive"))
      (node (ref "R202") (pin "1") (pinfunction "1_1") (pintype "passive"))
      (node (ref "R206") (pin "1") (pinfunction "1_1") (pintype "passive"))
      (node (ref "R208") (pin "1") (pinfunction "1_1") (pintype "passive"))
      (node (ref "R210") (pin "2") (pinfunction "2_2") (pintype "passive"))
      (node (ref "R212") (pin "1") (pinfunction "1_1") (pintype "passive"))
      (node (ref "R214") (pin "1") (pinfunction "1_1") (pintype "passive"))
      (node (ref "R219") (pin "1") (pinfunction "1_1") (pintype "passive"))
      (node (ref "R300") (pin "1") (pinfunction "1_1") (pintype "passive"))
      (node (ref "R301") (pin "2") (pinfunction "2_2") (pintype "passive"))
      (node (ref "R305") (pin "1") (pinfunction "1_1") (pintype "passive"))
      (node (ref "R332") (pin "1") (pinfunction "1_1") (pintype "passive"))
      (node (ref "R333") (pin "1") (pinfunction "1_1") (pintype "passive"))
      (node (ref "R334") (pin "1") (pinfunction "1_1") (pintype "passive"))
      (node (ref "R335") (pin "1") (pinfunction "1_1") (pintype "passive"))
      (node (ref "R336") (pin "1") (pinfunction "1_1") (pintype "passive"))
      (node (ref "R337") (pin "1") (pinfunction "1_1") (pintype "passive"))
      (node (ref "R343") (pin "1") (pinfunction "1_1") (pintype "passive"))
      (node (ref "R345") (pin "1") (pinfunction "1_1") (pintype "passive"))
      (node (ref "R402") (pin "1") (pinfunction "1_1") (pintype "passive"))
      (node (ref "R403") (pin "1") (pinfunction "1_1") (pintype "passive"))
      (node (ref "R405") (pin "1") (pinfunction "1_1") (pintype "passive"))
      (node (ref "R407") (pin "1") (pinfunction "1_1") (pintype "passive"))
      (node (ref "RV400") (pin "1") (pinfunction "A_1") (pintype "passive"))
      (node (ref "RV401") (pin "1") (pinfunction "A_1") (pintype "passive"))
      (node (ref "SJ403") (pin "1") (pinfunction "1_1") (pintype "passive"))
      (node (ref "SJ404") (pin "1") (pinfunction "1_1") (pintype "passive"))
      (node (ref "SJ404") (pin "2") (pinfunction "2_2") (pintype "passive"))
      (node (ref "SW400") (pin "B5") (pinfunction "S_B5") (pintype "passive"))
      (node (ref "SW400") (pin "B7") (pinfunction "S_B7") (pintype "passive"))
      (node (ref "SW400") (pin "B9") (pinfunction "S_B9") (pintype "passive"))
      (node (ref "SW402") (pin "2") (pinfunction "2_2") (pintype "passive"))
      (node (ref "SW403") (pin "2") (pinfunction "2_2") (pintype "passive"))
      (node (ref "SW404") (pin "2") (pinfunction "2_2") (pintype "passive"))
      (node (ref "SW405") (pin "2") (pinfunction "2_2") (pintype "passive"))
      (node (ref "SW406") (pin "2") (pinfunction "2_2") (pintype "passive"))
      (node (ref "SW407") (pin "1") (pinfunction "1_1") (pintype "passive"))
      (node (ref "SW408") (pin "2") (pinfunction "2_2") (pintype "passive"))
      (node (ref "U101") (pin "20") (pinfunction "PGND_20") (pintype "bidirectional"))
      (node (ref "U101") (pin "6") (pinfunction "GND_6") (pintype "bidirectional"))
      (node (ref "U102") (pin "2") (pinfunction "GND_2") (pintype "bidirectional"))
      (node (ref "U103") (pin "2") (pinfunction "GND_2") (pintype "bidirectional"))
      (node (ref "U104") (pin "2") (pinfunction "GND_2") (pintype "bidirectional"))
      (node (ref "U200") (pin "6") (pinfunction "GND_6") (pintype "bidirectional"))
      (node (ref "U201") (pin "4") (pinfunction "AGND_4") (pintype "bidirectional"))
      (node (ref "U201") (pin "5") (pinfunction "PGND_5") (pintype "bidirectional"))
      (node (ref "U202") (pin "4") (pinfunction "GND_4") (pintype "bidirectional"))
      (node (ref "U203") (pin "2") (pinfunction "GND_2") (pintype "bidirectional"))
      (node (ref "U204") (pin "2") (pinfunction "GND_2") (pintype "bidirectional"))
      (node (ref "U300") (pin "12") (pinfunction "GND_12") (pintype "bidirectional"))
      (node (ref "U300") (pin "13") (pinfunction "GND_13") (pintype "bidirectional"))
      (node (ref "U300") (pin "25") (pinfunction "GND_25") (pintype "bidirectional"))
      (node (ref "U300") (pin "26") (pinfunction "GND_26") (pintype "bidirectional"))
      (node (ref "U300") (pin "33") (pinfunction "GND_33") (pintype "bidirectional"))
      (node (ref "U300") (pin "34") (pinfunction "GND_34") (pintype "bidirectional"))
      (node (ref "U300") (pin "4") (pinfunction "M2_4") (pintype "bidirectional"))
      (node (ref "U300") (pin "41") (pinfunction "GND_41") (pintype "bidirectional"))
      (node (ref "U300") (pin "42") (pinfunction "GND_42") (pintype "bidirectional"))
      (node (ref "U301") (pin "2") (pinfunction "V-_2") (pintype "power_in"))
      (node (ref "U302") (pin "11") (pinfunction "V-_11") (pintype "power_in"))
      (node (ref "U303") (pin "11") (pinfunction "V-_11") (pintype "power_in"))
      (node (ref "U304") (pin "11") (pinfunction "V-_11") (pintype "power_in"))
      (node (ref "U305") (pin "4") (pinfunction "V-_4") (pintype "power_in"))
      (node (ref "U306") (pin "2") (pinfunction "V-_2") (pintype "power_in"))
      (node (ref "U400") (pin "29") (pinfunction "VSS_29") (pintype "bidirectional"))
      (node (ref "U400") (pin "6") (pinfunction "VSS_6") (pintype "bidirectional"))
      (node (ref "U401") (pin "13") (pinfunction "GND_13") (pintype "power_in"))
      (node (ref "U401") (pin "5") (pinfunction "GND_5") (pintype "power_in"))
      (node (ref "U402") (pin "2") (pinfunction "V-_2") (pintype "power_in"))
      (node (ref "XDS400") (pin "1") (pinfunction "VSS_1") (pintype "bidirectional"))
      (node (ref "XLS301") (pin "1") (pinfunction "-_1") (pintype "passive"))
      (node (ref "XLS302") (pin "1") (pinfunction "-_1") (pintype "passive"))
    )
    (net (code "25") (name "Net-(A400-ADAP_IN)") (class "Default")
      (node (ref "A400") (pin "20") (pinfunction "ADAP_IN_20") (pintype "bidirectional"))
      (node (ref "SJ401") (pin "2") (pinfunction "2_2") (pintype "passive"))
    )
    (net (code "26") (name "Net-(A400-AIL)") (class "Default")
      (node (ref "A400") (pin "15") (pinfunction "AIL_15") (pintype "bidirectional"))
      (node (ref "D400") (pin "2") (pinfunction "2_2") (pintype "passive"))
      (node (ref "J402") (pin "1") (pinfunction "P$1_1") (pintype "bidirectional"))
    )
    (net (code "27") (name "Net-(A400-AIR)") (class "Default")
      (node (ref "A400") (pin "14") (pinfunction "AIR_14") (pintype "bidirectional"))
      (node (ref "D400") (pin "1") (pinfunction "1_1") (pintype "passive"))
      (node (ref "J402") (pin "2") (pinfunction "P$1_2") (pintype "bidirectional"))
    )
    (net (code "28") (name "Net-(A400-EAN)") (class "Default")
      (node (ref "A400") (pin "2") (pinfunction "EAN_2") (pintype "bidirectional"))
      (node (ref "SW400") (pin "A7") (pinfunction "P_A7") (pintype "passive"))
      (node (ref "SW400") (pin "A8") (pinfunction "P_A8") (pintype "passive"))
    )
    (net (code "29") (name "Net-(A400-HCI_RXD)") (class "Default")
      (node (ref "A400") (pin "33") (pinfunction "HCI_RXD_33") (pintype "bidirectional"))
      (node (ref "SW400") (pin "A1") (pinfunction "P_A1") (pintype "passive"))
      (node (ref "SW400") (pin "A2") (pinfunction "P_A2") (pintype "passive"))
    )
    (net (code "30") (name "Net-(A400-HCI_TXD)") (class "Default")
      (node (ref "A400") (pin "32") (pinfunction "HCI_TXD_32") (pintype "bidirectional"))
      (node (ref "SW400") (pin "A3") (pinfunction "P_A3") (pintype "passive"))
      (node (ref "SW400") (pin "A4") (pinfunction "P_A4") (pintype "passive"))
    )
    (net (code "31") (name "Net-(A400-LED1)") (class "Default")
      (node (ref "A400") (pin "27") (pinfunction "LED1_27") (pintype "bidirectional"))
      (node (ref "U400") (pin "10") (pinfunction "RB2_10") (pintype "bidirectional"))
    )
    (net (code "32") (name "Net-(A400-LED2)") (class "Default")
      (node (ref "A400") (pin "28") (pinfunction "LED2_28") (pintype "bidirectional"))
      (node (ref "U400") (pin "11") (pinfunction "RB3_11") (pintype "bidirectional"))
    )
    (net (code "33") (name "Net-(A400-MFB)") (class "Default")
      (node (ref "A400") (pin "26") (pinfunction "MFB_26") (pintype "bidirectional"))
      (node (ref "SW401") (pin "1") (pinfunction "1_1") (pintype "passive"))
    )
    (net (code "34") (name "Net-(A400-MIC1_N)") (class "Default")
      (node (ref "A400") (pin "12") (pinfunction "MIC1_N_12") (pintype "bidirectional"))
      (node (ref "R403") (pin "2") (pinfunction "2_2") (pintype "passive"))
    )
    (net (code "35") (name "Net-(A400-MIC1_P)") (class "Default")
      (node (ref "A400") (pin "11") (pinfunction "MIC1_P_11") (pintype "bidirectional"))
      (node (ref "R402") (pin "2") (pinfunction "2_2") (pintype "passive"))
    )
    (net (code "36") (name "Net-(A400-P0_1)") (class "Default")
      (node (ref "A400") (pin "18") (pinfunction "P0_1_18") (pintype "bidirectional"))
      (node (ref "C406") (pin "1") (pinfunction "1_1") (pintype "passive"))
      (node (ref "SW405") (pin "1") (pinfunction "1_1") (pintype "passive"))
    )
    (net (code "37") (name "Net-(A400-P0_2)") (class "Default")
      (node (ref "A400") (pin "30") (pinfunction "P0_2_30") (pintype "bidirectional"))
      (node (ref "C403") (pin "1") (pinfunction "1_1") (pintype "passive"))
      (node (ref "SW402") (pin "1") (pinfunction "1_1") (pintype "passive"))
    )
    (net (code "38") (name "Net-(A400-P0_3)") (class "Default")
      (node (ref "A400") (pin "31") (pinfunction "P0_3_31") (pintype "bidirectional"))
      (node (ref "C407") (pin "1") (pinfunction "1_1") (pintype "passive"))
      (node (ref "SW406") (pin "1") (pinfunction "1_1") (pintype "passive"))
    )
    (net (code "39") (name "Net-(A400-P0_5)") (class "Default")
      (node (ref "A400") (pin "34") (pinfunction "P0_5_34") (pintype "bidirectional"))
      (node (ref "C405") (pin "1") (pinfunction "1_1") (pintype "passive"))
      (node (ref "SW404") (pin "1") (pinfunction "1_1") (pintype "passive"))
    )
    (net (code "40") (name "Net-(A400-P2_0)") (class "Default")
      (node (ref "A400") (pin "4") (pinfunction "P2_0_4") (pintype "bidirectional"))
      (node (ref "SW400") (pin "A5") (pinfunction "P_A5") (pintype "passive"))
      (node (ref "SW400") (pin "A6") (pinfunction "P_A6") (pintype "passive"))
    )
    (net (code "41") (name "Net-(A400-P2_4)") (class "Default")
      (node (ref "A400") (pin "29") (pinfunction "P2_4_29") (pintype "bidirectional"))
      (node (ref "SW400") (pin "A10") (pinfunction "P_A10") (pintype "passive"))
      (node (ref "SW400") (pin "A9") (pinfunction "P_A9") (pintype "passive"))
    )
    (net (code "42") (name "Net-(A400-P2_7)") (class "Default")
      (node (ref "A400") (pin "35") (pinfunction "P2_7_35") (pintype "bidirectional"))
      (node (ref "C404") (pin "1") (pinfunction "1_1") (pintype "passive"))
      (node (ref "SW403") (pin "1") (pinfunction "1_1") (pintype "passive"))
    )
    (net (code "43") (name "Net-(A400-SPKL)") (class "Default")
      (node (ref "A400") (pin "9") (pinfunction "SPKL_9") (pintype "bidirectional"))
      (node (ref "R409") (pin "2") (pinfunction "2_2") (pintype "passive"))
    )
    (net (code "44") (name "Net-(A400-SPKR)") (class "Default")
      (node (ref "A400") (pin "7") (pinfunction "SPKR_7") (pintype "bidirectional"))
      (node (ref "R408") (pin "2") (pinfunction "2_2") (pintype "passive"))
    )
    (net (code "45") (name "Net-(A400-SYS_PWR)") (class "Default")
      (node (ref "A400") (pin "24") (pinfunction "SYS_PWR_24") (pintype "bidirectional"))
      (node (ref "SW401") (pin "2") (pinfunction "2_2") (pintype "passive"))
    )
    (net (code "46") (name "Net-(A400-~{RST})") (class "Default")
      (node (ref "A400") (pin "16") (pinfunction "~{RST}_16") (pintype "bidirectional"))
      (node (ref "U400") (pin "14") (pinfunction "RB4_14") (pintype "bidirectional"))
    )
    (net (code "47") (name "Net-(C116-Pad1)") (class "Default")
      (node (ref "C116") (pin "1") (pinfunction "1_1") (pintype "passive"))
      (node (ref "R118") (pin "1") (pinfunction "1_1") (pintype "passive"))
    )
    (net (code "48") (name "Net-(C207-Pad1)") (class "Default")
      (node (ref "C207") (pin "1") (pinfunction "1_1") (pintype "passive"))
      (node (ref "R203") (pin "2") (pinfunction "2_2") (pintype "passive"))
    )
    (net (code "49") (name "Net-(C209-Pad1)") (class "Default")
      (node (ref "C209") (pin "1") (pinfunction "1_1") (pintype "passive"))
      (node (ref "R204") (pin "2") (pinfunction "2_2") (pintype "passive"))
      (node (ref "R205") (pin "1") (pinfunction "1_1") (pintype "passive"))
    )
    (net (code "50") (name "Net-(C222-Pad1)") (class "Default")
      (node (ref "C222") (pin "1") (pinfunction "1_1") (pintype "passive"))
      (node (ref "R209") (pin "1") (pinfunction "1_1") (pintype "passive"))
    )
    (net (code "51") (name "Net-(C301-Pad2)") (class "Default")
      (node (ref "C301") (pin "2") (pinfunction "2_2") (pintype "passive"))
      (node (ref "R306") (pin "1") (pinfunction "1_1") (pintype "passive"))
    )
    (net (code "52") (name "Net-(C302-Pad2)") (class "Default")
      (node (ref "C302") (pin "2") (pinfunction "2_2") (pintype "passive"))
      (node (ref "R308") (pin "1") (pinfunction "1_1") (pintype "passive"))
    )
    (net (code "53") (name "Net-(C304-Pad1)") (class "Default")
      (node (ref "C304") (pin "1") (pinfunction "1_1") (pintype "passive"))
      (node (ref "R310") (pin "2") (pinfunction "2_2") (pintype "passive"))
      (node (ref "R311") (pin "1") (pinfunction "1_1") (pintype "passive"))
    )
    (net (code "54") (name "Net-(C306-Pad1)") (class "Default")
      (node (ref "C306") (pin "1") (pinfunction "1_1") (pintype "passive"))
      (node (ref "R312") (pin "2") (pinfunction "2_2") (pintype "passive"))
      (node (ref "R313") (pin "1") (pinfunction "1_1") (pintype "passive"))
    )
    (net (code "55") (name "Net-(C307-Pad2)") (class "Default")
      (node (ref "C307") (pin "2") (pinfunction "2_2") (pintype "passive"))
      (node (ref "R314") (pin "1") (pinfunction "1_1") (pintype "passive"))
    )
    (net (code "56") (name "Net-(C310-Pad2)") (class "Default")
      (node (ref "C310") (pin "2") (pinfunction "2_2") (pintype "passive"))
      (node (ref "C311") (pin "1") (pinfunction "1_1") (pintype "passive"))
      (node (ref "R319") (pin "1") (pinfunction "1_1") (pintype "passive"))
    )
    (net (code "57") (name "Net-(C312-Pad2)") (class "Default")
      (node (ref "C312") (pin "2") (pinfunction "2_2") (pintype "passive"))
      (node (ref "C313") (pin "1") (pinfunction "1_1") (pintype "passive"))
      (node (ref "R321") (pin "1") (pinfunction "1_1") (pintype "passive"))
    )
    (net (code "58") (name "Net-(C314-Pad2)") (class "Default")
      (node (ref "C314") (pin "2") (pinfunction "2_2") (pintype "passive"))
      (node (ref "R322") (pin "1") (pinfunction "1_1") (pintype "passive"))
    )
    (net (code "59") (name "Net-(C316-Pad2)") (class "Default")
      (node (ref "C316") (pin "2") (pinfunction "2_2") (pintype "passive"))
      (node (ref "C317") (pin "1") (pinfunction "1_1") (pintype "passive"))
      (node (ref "R325") (pin "1") (pinfunction "1_1") (pintype "passive"))
    )
    (net (code "60") (name "Net-(C318-Pad2)") (class "Default")
      (node (ref "C318") (pin "2") (pinfunction "2_2") (pintype "passive"))
      (node (ref "C319") (pin "1") (pinfunction "1_1") (pintype "passive"))
      (node (ref "R327") (pin "1") (pinfunction "1_1") (pintype "passive"))
    )
    (net (code "61") (name "Net-(C320-Pad2)") (class "Default")
      (node (ref "C320") (pin "2") (pinfunction "2_2") (pintype "passive"))
      (node (ref "R328") (pin "1") (pinfunction "1_1") (pintype "passive"))
    )
    (net (code "62") (name "Net-(C330-Pad2)") (class "Default")
      (node (ref "C330") (pin "2") (pinfunction "2_2") (pintype "passive"))
      (node (ref "L300") (pin "1") (pinfunction "1_1") (pintype "passive"))
      (node (ref "U300") (pin "39") (pinfunction "OUT_A_39") (pintype "bidirectional"))
      (node (ref "U300") (pin "40") (pinfunction "OUT_A_40") (pintype "bidirectional"))
    )
    (net (code "63") (name "Net-(C333-Pad1)") (class "Default")
      (node (ref "C333") (pin "1") (pinfunction "1_1") (pintype "passive"))
      (node (ref "L303") (pin "1") (pinfunction "1_1") (pintype "passive"))
      (node (ref "U300") (pin "27") (pinfunction "OUT_D_27") (pintype "bidirectional"))
      (node (ref "U300") (pin "28") (pinfunction "OUT_D_28") (pintype "bidirectional"))
    )
    (net (code "64") (name "Net-(C340-Pad1)") (class "Default")
      (node (ref "C340") (pin "1") (pinfunction "1_1") (pintype "passive"))
      (node (ref "C341") (pin "1") (pinfunction "1_1") (pintype "passive"))
      (node (ref "C342") (pin "1") (pinfunction "1_1") (pintype "passive"))
      (node (ref "F300") (pin "1") (pinfunction "1_1") (pintype "passive"))
      (node (ref "L300") (pin "2") (pinfunction "2_2") (pintype "passive"))
    )
    (net (code "65") (name "Net-(C342-Pad2)") (class "Default")
      (node (ref "C342") (pin "2") (pinfunction "2_2") (pintype "passive"))
      (node (ref "R334") (pin "2") (pinfunction "2_2") (pintype "passive"))
    )
    (net (code "66") (name "Net-(C345-Pad1)") (class "Default")
      (node (ref "C345") (pin "1") (pinfunction "1_1") (pintype "passive"))
      (node (ref "R335") (pin "2") (pinfunction "2_2") (pintype "passive"))
    )
    (net (code "67") (name "Net-(C346-Pad1)") (class "Default")
      (node (ref "C346") (pin "1") (pinfunction "1_1") (pintype "passive"))
      (node (ref "C347") (pin "1") (pinfunction "1_1") (pintype "passive"))
      (node (ref "C348") (pin "1") (pinfunction "1_1") (pintype "passive"))
      (node (ref "C352") (pin "+") (pinfunction "+_+") (pintype "passive"))
      (node (ref "L302") (pin "2") (pinfunction "2_2") (pintype "passive"))
    )
    (net (code "68") (name "Net-(C348-Pad2)") (class "Default")
      (node (ref "C348") (pin "2") (pinfunction "2_2") (pintype "passive"))
      (node (ref "R336") (pin "2") (pinfunction "2_2") (pintype "passive"))
    )
    (net (code "69") (name "Net-(C349-Pad2)") (class "Default")
      (node (ref "C349") (pin "2") (pinfunction "2_2") (pintype "passive"))
      (node (ref "C350") (pin "2") (pinfunction "2_2") (pintype "passive"))
      (node (ref "C351") (pin "2") (pinfunction "2_2") (pintype "passive"))
      (node (ref "C353") (pin "+") (pinfunction "+_+") (pintype "passive"))
      (node (ref "L303") (pin "2") (pinfunction "2_2") (pintype "passive"))
    )
    (net (code "70") (name "Net-(C351-Pad1)") (class "Default")
      (node (ref "C351") (pin "1") (pinfunction "1_1") (pintype "passive"))
      (node (ref "R337") (pin "2") (pinfunction "2_2") (pintype "passive"))
    )
    (net (code "71") (name "Net-(C352-Pad-)") (class "Default")
      (node (ref "C352") (pin "-") (pinfunction "-_-") (pintype "passive"))
      (node (ref "F301") (pin "1") (pinfunction "1_1") (pintype "passive"))
    )
    (net (code "72") (name "Net-(C353-Pad-)") (class "Default")
      (node (ref "C353") (pin "-") (pinfunction "-_-") (pintype "passive"))
      (node (ref "F302") (pin "1") (pinfunction "1_1") (pintype "passive"))
    )
    (net (code "73") (name "Net-(C354-Pad1)") (class "Default")
      (node (ref "C354") (pin "1") (pinfunction "1_1") (pintype "passive"))
      (node (ref "R338") (pin "1") (pinfunction "1_1") (pintype "passive"))
    )
    (net (code "74") (name "Net-(C355-Pad1)") (class "Default")
      (node (ref "C355") (pin "1") (pinfunction "1_1") (pintype "passive"))
      (node (ref "R339") (pin "1") (pinfunction "1_1") (pintype "passive"))
    )
    (net (code "75") (name "Net-(C356-Pad1)") (class "Default")
      (node (ref "C356") (pin "1") (pinfunction "1_1") (pintype "passive"))
      (node (ref "R341") (pin "1") (pinfunction "1_1") (pintype "passive"))
    )
    (net (code "76") (name "Net-(C402-Pad1)") (class "Default")
      (node (ref "C402") (pin "1") (pinfunction "1_1") (pintype "passive"))
      (node (ref "R400") (pin "1") (pinfunction "1_1") (pintype "passive"))
      (node (ref "R401") (pin "1") (pinfunction "1_1") (pintype "passive"))
      (node (ref "SW407") (pin "2") (pinfunction "2_2") (pintype "passive"))
    )
    (net (code "77") (name "Net-(D100-A)") (class "Default")
      (node (ref "C126") (pin "1") (pinfunction "1_1") (pintype "passive"))
      (node (ref "C127") (pin "1") (pinfunction "1_1") (pintype "passive"))
      (node (ref "D100") (pin "2") (pinfunction "A_2") (pintype "passive"))
      (node (ref "F101") (pin "2") (pinfunction "2_2") (pintype "passive"))
      (node (ref "Q104") (pin "S") (pinfunction "S_S") (pintype "passive"))
      (node (ref "U102") (pin "3") (pinfunction "EN_3") (pintype "bidirectional"))
      (node (ref "U102") (pin "6") (pinfunction "ANODE_6") (pintype "bidirectional"))
    )
    (net (code "78") (name "Net-(D100-C)") (class "Default")
      (node (ref "C121") (pin "1") (pinfunction "1_1") (pintype "passive"))
      (node (ref "D100") (pin "1") (pinfunction "C_1") (pintype "passive"))
      (node (ref "U101") (pin "28") (pinfunction "DCIN_28") (pintype "bidirectional"))
    )
    (net (code "79") (name "Net-(D101-A)") (class "Default")
      (node (ref "C124") (pin "1") (pinfunction "1_1") (pintype "passive"))
      (node (ref "D101") (pin "2") (pinfunction "A_2") (pintype "passive"))
      (node (ref "U101") (pin "22") (pinfunction "VLO_22") (pintype "bidirectional"))
    )
    (net (code "80") (name "Net-(D101-C)") (class "Default")
      (node (ref "C110") (pin "1") (pinfunction "1_1") (pintype "passive"))
      (node (ref "D101") (pin "1") (pinfunction "C_1") (pintype "passive"))
      (node (ref "U101") (pin "23") (pinfunction "BST_23") (pintype "bidirectional"))
    )
    (net (code "81") (name "Net-(D103-C)") (class "Default")
      (node (ref "D103") (pin "K") (pinfunction "C_K") (pintype "passive"))
      (node (ref "F101") (pin "1") (pinfunction "1_1") (pintype "passive"))
      (node (ref "J100") (pin "1") (pinfunction "1_1") (pintype "passive"))
    )
    (net (code "82") (name "Net-(D200-A-PadA1)") (class "Default")
      (node (ref "D200") (pin "A1") (pinfunction "A_A1") (pintype "passive"))
      (node (ref "D200") (pin "A2") (pinfunction "A_A2") (pintype "passive"))
      (node (ref "L200") (pin "2") (pinfunction "2_2") (pintype "passive"))
      (node (ref "Q200") (pin "D") (pinfunction "D_D") (pintype "passive"))
      (node (ref "Q201") (pin "D") (pinfunction "D_D") (pintype "passive"))
    )
    (net (code "83") (name "Net-(D202-C)") (class "Default")
      (node (ref "D202") (pin "K") (pinfunction "C_K") (pintype "passive"))
      (node (ref "L202") (pin "1") (pinfunction "1_1") (pintype "passive"))
      (node (ref "Q203") (pin "3") (pinfunction "D_3") (pintype "passive"))
    )
    (net (code "84") (name "Net-(DN300-AC1)") (class "Default")
      (node (ref "C357") (pin "1") (pinfunction "1_1") (pintype "passive"))
      (node (ref "DN300") (pin "~1") (pinfunction "AC1_~1") (pintype "passive"))
      (node (ref "R343") (pin "2") (pinfunction "2_2") (pintype "passive"))
    )
    (net (code "85") (name "Net-(DN300-DC+)") (class "Default")
      (node (ref "DN300") (pin "+") (pinfunction "DC+_+") (pintype "passive"))
      (node (ref "R344") (pin "1") (pinfunction "1_1") (pintype "passive"))
    )
    (net (code "86") (name "Net-(DN300-DC-)") (class "Default")
      (node (ref "DN300") (pin "-") (pinfunction "DC-_-") (pintype "passive"))
      (node (ref "R346") (pin "1") (pinfunction "1_1") (pintype "passive"))
    )
    (net (code "87") (name "Net-(F100-Pad1)") (class "Default")
      (node (ref "F100") (pin "1") (pinfunction "1_1") (pintype "passive"))
      (node (ref "R100") (pin "1") (pinfunction "1_1") (pintype "passive"))
      (node (ref "XBT100") (pin "1") (pinfunction "+_1") (pintype "bidirectional"))
      (node (ref "XBT100") (pin "2") (pinfunction "+_2") (pintype "bidirectional"))
    )
    (net (code "88") (name "Net-(FAN300-+)") (class "Default")
      (node (ref "FAN300") (pin "1") (pinfunction "+_1") (pintype "bidirectional"))
      (node (ref "R302") (pin "2") (pinfunction "2_2") (pintype "passive"))
      (node (ref "U301") (pin "1") (pinfunction "OUT_1") (pintype "output"))
    )
    (net (code "89") (name "Net-(FAN300--)") (class "Default")
      (node (ref "FAN300") (pin "2") (pinfunction "-_2") (pintype "bidirectional"))
      (node (ref "Q300") (pin "3") (pinfunction "D_3") (pintype "passive"))
    )
    (net (code "90") (name "Net-(J401-D+)") (class "Default")
      (node (ref "J401") (pin "3") (pinfunction "D+_3") (pintype "passive"))
      (node (ref "U401") (pin "8") (pinfunction "USBDP_8") (pintype "input"))
    )
    (net (code "91") (name "Net-(J401-D-)") (class "Default")
      (node (ref "J401") (pin "2") (pinfunction "D-_2") (pintype "passive"))
      (node (ref "U401") (pin "9") (pinfunction "USBDM_9") (pintype "input"))
    )
    (net (code "92") (name "Net-(J401-VBUS)") (class "Default")
      (node (ref "J401") (pin "1") (pinfunction "VBUS_1") (pintype "passive"))
      (node (ref "SJ402") (pin "1") (pinfunction "1_1") (pintype "passive"))
    )
    (net (code "93") (name "Net-(J403B-P$1)") (class "Default")
      (node (ref "J403") (pin "2") (pinfunction "P$1_2") (pintype "bidirectional"))
      (node (ref "Q403") (pin "3") (pinfunction "D_3") (pintype "passive"))
    )
    (net (code "94") (name "Net-(J403C-P$1)") (class "Default")
      (node (ref "J403") (pin "3") (pinfunction "P$1_3") (pintype "bidirectional"))
      (node (ref "Q404") (pin "3") (pinfunction "D_3") (pintype "passive"))
    )
    (net (code "95") (name "Net-(J403D-P$1)") (class "Default")
      (node (ref "J403") (pin "4") (pinfunction "P$1_4") (pintype "bidirectional"))
      (node (ref "Q405") (pin "3") (pinfunction "D_3") (pintype "passive"))
    )
    (net (code "96") (name "Net-(J404B-P$1)") (class "Default")
      (node (ref "J404") (pin "2") (pinfunction "P$1_2") (pintype "bidirectional"))
      (node (ref "Q406") (pin "3") (pinfunction "D_3") (pintype "passive"))
    )
    (net (code "97") (name "Net-(J404C-P$1)") (class "Default")
      (node (ref "J404") (pin "3") (pinfunction "P$1_3") (pintype "bidirectional"))
      (node (ref "Q407") (pin "3") (pinfunction "D_3") (pintype "passive"))
    )
    (net (code "98") (name "Net-(L201-P2)") (class "Default")
      (node (ref "C224") (pin "2") (pinfunction "2_2") (pintype "passive"))
      (node (ref "L201") (pin "3") (pinfunction "P2_3") (pintype "passive"))
      (node (ref "Q202") (pin "MB") (pinfunction "D_MB") (pintype "passive"))
    )
    (net (code "99") (name "Net-(L201-S2)") (class "Default")
      (node (ref "C224") (pin "1") (pinfunction "1_1") (pintype "passive"))
      (node (ref "D201") (pin "A1") (pinfunction "A_A1") (pintype "passive"))
      (node (ref "D201") (pin "A2") (pinfunction "A_A2") (pintype "passive"))
      (node (ref "L201") (pin "4") (pinfunction "S2_4") (pintype "passive"))
    )
    (net (code "100") (name "Net-(Q100-PadD)") (class "Default")
      (node (ref "Q100") (pin "D") (pinfunction "D_D") (pintype "passive"))
      (node (ref "Q101") (pin "D") (pinfunction "D_D") (pintype "passive"))
    )
    (net (code "101") (name "Net-(Q100-PadG)") (class "Default")
      (node (ref "Q100") (pin "G") (pinfunction "G_G") (pintype "passive"))
      (node (ref "R108") (pin "1") (pinfunction "1_1") (pintype "passive"))
      (node (ref "R109") (pin "2") (pinfunction "2_2") (pintype "passive"))
    )
    (net (code "102") (name "Net-(Q100-PadS)") (class "Default")
      (node (ref "Q100") (pin "S") (pinfunction "S_S") (pintype "passive"))
      (node (ref "R105") (pin "2") (pinfunction "2_2") (pintype "passive"))
      (node (ref "R107") (pin "1") (pinfunction "1_1") (pintype "passive"))
      (node (ref "R109") (pin "1") (pinfunction "1_1") (pintype "passive"))
    )
    (net (code "103") (name "Net-(Q101-PadG)") (class "Default")
      (node (ref "Q101") (pin "G") (pinfunction "G_G") (pintype "passive"))
      (node (ref "R110") (pin "1") (pinfunction "1_1") (pintype "passive"))
      (node (ref "R111") (pin "2") (pinfunction "2_2") (pintype "passive"))
    )
    (net (code "104") (name "Net-(Q200-PadS)") (class "Default")
      (node (ref "Q200") (pin "S") (pinfunction "S_S") (pintype "passive"))
      (node (ref "Q201") (pin "S") (pinfunction "S_S") (pintype "passive"))
      (node (ref "R205") (pin "2") (pinfunction "2_2") (pintype "passive"))
      (node (ref "R206") (pin "2") (pinfunction "2_2") (pintype "passive"))
    )
    (net (code "105") (name "Net-(Q202-G)") (class "Default")
      (node (ref "Q202") (pin "4") (pinfunction "G_4") (pintype "passive"))
      (node (ref "U201") (pin "6") (pinfunction "DR_6") (pintype "bidirectional"))
    )
    (net (code "106") (name "Net-(Q202-S-Pad1)") (class "Default")
      (node (ref "Q202") (pin "1") (pinfunction "S_1") (pintype "passive"))
      (node (ref "Q202") (pin "2") (pinfunction "S_2") (pintype "passive"))
      (node (ref "Q202") (pin "3") (pinfunction "S_3") (pintype "passive"))
      (node (ref "R211") (pin "2") (pinfunction "2_2") (pintype "passive"))
      (node (ref "R212") (pin "2") (pinfunction "2_2") (pintype "passive"))
    )
    (net (code "107") (name "Net-(Q203-G)") (class "Default")
      (node (ref "Q203") (pin "1") (pinfunction "G_1") (pintype "passive"))
      (node (ref "U202") (pin "6") (pinfunction "PGATE_6") (pintype "bidirectional"))
    )
    (net (code "108") (name "Net-(Q203-S)") (class "Default")
      (node (ref "Q203") (pin "2") (pinfunction "S_2") (pintype "passive"))
      (node (ref "R217") (pin "1") (pinfunction "1_1") (pintype "passive"))
      (node (ref "U202") (pin "5") (pinfunction "ISEN_5") (pintype "bidirectional"))
    )
    (net (code "109") (name "Net-(Q300-G)") (class "Default")
      (node (ref "Q300") (pin "1") (pinfunction "G_1") (pintype "passive"))
      (node (ref "R303") (pin "2") (pinfunction "2_2") (pintype "passive"))
    )
    (net (code "110") (name "Net-(Q400-D)") (class "Default")
      (node (ref "Q400") (pin "3") (pinfunction "D_3") (pintype "passive"))
      (node (ref "XDS400") (pin "16") (pinfunction "K_16") (pintype "bidirectional"))
    )
    (net (code "111") (name "Net-(Q400-G)") (class "Default")
      (node (ref "Q400") (pin "1") (pinfunction "G_1") (pintype "passive"))
      (node (ref "U400") (pin "32") (pinfunction "RC0_32") (pintype "bidirectional"))
    )
    (net (code "112") (name "Net-(Q401-G)") (class "Default")
      (node (ref "Q401") (pin "1") (pinfunction "G_1") (pintype "passive"))
      (node (ref "U400") (pin "42") (pinfunction "RC4_42") (pintype "bidirectional"))
    )
    (net (code "113") (name "Net-(Q403-G)") (class "Default")
      (node (ref "Q403") (pin "1") (pinfunction "G_1") (pintype "passive"))
      (node (ref "U400") (pin "1") (pinfunction "RC7_1") (pintype "bidirectional"))
    )
    (net (code "114") (name "Net-(Q404-G)") (class "Default")
      (node (ref "Q404") (pin "1") (pinfunction "G_1") (pintype "passive"))
      (node (ref "U400") (pin "2") (pinfunction "RD4_2") (pintype "bidirectional"))
    )
    (net (code "115") (name "Net-(Q405-G)") (class "Default")
      (node (ref "Q405") (pin "1") (pinfunction "G_1") (pintype "passive"))
      (node (ref "U400") (pin "3") (pinfunction "RD5_3") (pintype "bidirectional"))
    )
    (net (code "116") (name "Net-(Q406-G)") (class "Default")
      (node (ref "Q406") (pin "1") (pinfunction "G_1") (pintype "passive"))
      (node (ref "U400") (pin "4") (pinfunction "RD6_4") (pintype "bidirectional"))
    )
    (net (code "117") (name "Net-(Q407-G)") (class "Default")
      (node (ref "Q407") (pin "1") (pinfunction "G_1") (pintype "passive"))
      (node (ref "U400") (pin "5") (pinfunction "RD7_5") (pintype "bidirectional"))
    )
    (net (code "118") (name "Net-(R116-Pad2)") (class "Default")
      (node (ref "R116") (pin "2") (pinfunction "2_2") (pintype "passive"))
      (node (ref "SW100") (pin "2") (pinfunction "2_2") (pintype "passive"))
    )
    (net (code "119") (name "Net-(R122-Pad1)") (class "Default")
      (node (ref "R122") (pin "1") (pinfunction "1_1") (pintype "passive"))
      (node (ref "R123") (pin "2") (pinfunction "2_2") (pintype "passive"))
    )
    (net (code "120") (name "Net-(RV300-A)") (class "Default")
      (node (ref "R315") (pin "2") (pinfunction "2_2") (pintype "passive"))
      (node (ref "RV300") (pin "1") (pinfunction "A_1") (pintype "passive"))
    )
    (net (code "121") (name "Net-(RV300-S)") (class "Default")
      (node (ref "C308") (pin "1") (pinfunction "1_1") (pintype "passive"))
      (node (ref "R316") (pin "1") (pinfunction "1_1") (pintype "passive"))
      (node (ref "RV300") (pin "2") (pinfunction "S_2") (pintype "passive"))
      (node (ref "U304") (pin "8") (pinfunction "OUT_8") (pintype "output"))
    )
    (net (code "122") (name "Net-(RV301-A)") (class "Default")
      (node (ref "R323") (pin "2") (pinfunction "2_2") (pintype "passive"))
      (node (ref "RV301") (pin "1") (pinfunction "A_1") (pintype "passive"))
    )
    (net (code "123") (name "Net-(RV301-S)") (class "Default")
      (node (ref "C315") (pin "1") (pinfunction "1_1") (pintype "passive"))
      (node (ref "RV301") (pin "2") (pinfunction "S_2") (pintype "passive"))
      (node (ref "U303") (pin "14") (pinfunction "OUT_14") (pintype "output"))
    )
    (net (code "124") (name "Net-(RV302-A)") (class "Default")
      (node (ref "R329") (pin "2") (pinfunction "2_2") (pintype "passive"))
      (node (ref "RV302") (pin "1") (pinfunction "A_1") (pintype "passive"))
    )
    (net (code "125") (name "Net-(RV302-S)") (class "Default")
      (node (ref "C321") (pin "1") (pinfunction "1_1") (pintype "passive"))
      (node (ref "RV302") (pin "2") (pinfunction "S_2") (pintype "passive"))
      (node (ref "U303") (pin "8") (pinfunction "OUT_8") (pintype "output"))
    )
    (net (code "126") (name "Net-(RV303-A)") (class "Default")
      (node (ref "R342") (pin "2") (pinfunction "2_2") (pintype "passive"))
      (node (ref "RV303") (pin "1") (pinfunction "A_1") (pintype "passive"))
    )
    (net (code "127") (name "Net-(RV303-S)") (class "Default")
      (node (ref "C357") (pin "2") (pinfunction "2_2") (pintype "passive"))
      (node (ref "RV303") (pin "2") (pinfunction "S_2") (pintype "passive"))
      (node (ref "U305") (pin "7") (pinfunction "OUT_7") (pintype "output"))
    )
    (net (code "128") (name "Net-(RV400-S)") (class "Default")
      (node (ref "RV400") (pin "2") (pinfunction "S_2") (pintype "passive"))
      (node (ref "XDS400") (pin "3") (pinfunction "V0_3") (pintype "bidirectional"))
    )
    (net (code "129") (name "Net-(RV401-S)") (class "Default")
      (node (ref "RV401") (pin "2") (pinfunction "S_2") (pintype "passive"))
      (node (ref "U400") (pin "44") (pinfunction "RC6_44") (pintype "bidirectional"))
    )
    (net (code "130") (name "Net-(SW400A-O)") (class "Default")
      (node (ref "SW400") (pin "B2") (pinfunction "O_B2") (pintype "passive"))
      (node (ref "U401") (pin "1") (pinfunction "TXD_1") (pintype "output"))
    )
    (net (code "131") (name "Net-(SW400A-S)") (class "Default")
      (node (ref "SW400") (pin "B1") (pinfunction "S_B1") (pintype "passive"))
      (node (ref "U400") (pin "8") (pinfunction "RB0_8") (pintype "bidirectional"))
    )
    (net (code "132") (name "Net-(SW400B-O)") (class "Default")
      (node (ref "SW400") (pin "B4") (pinfunction "O_B4") (pintype "passive"))
      (node (ref "U401") (pin "4") (pinfunction "RXD_4") (pintype "input"))
    )
    (net (code "133") (name "Net-(SW400B-S)") (class "Default")
      (node (ref "SW400") (pin "B3") (pinfunction "S_B3") (pintype "passive"))
      (node (ref "U400") (pin "9") (pinfunction "RB1_9") (pintype "bidirectional"))
    )
    (net (code "134") (name "Net-(U100-AVDD)") (class "Default")
      (node (ref "C109") (pin "1") (pinfunction "1_1") (pintype "passive"))
      (node (ref "U100") (pin "2") (pinfunction "AVDD_2") (pintype "bidirectional"))
      (node (ref "U100") (pin "20") (pinfunction "CCFG_20") (pintype "bidirectional"))
    )
    (net (code "135") (name "Net-(U100-CBI)") (class "Default")
      (node (ref "R115") (pin "1") (pinfunction "1_1") (pintype "passive"))
      (node (ref "U100") (pin "16") (pinfunction "CBI_16") (pintype "bidirectional"))
    )
    (net (code "136") (name "Net-(U100-CHG)") (class "Default")
      (node (ref "R110") (pin "2") (pinfunction "2_2") (pintype "passive"))
      (node (ref "R128") (pin "1") (pinfunction "1_1") (pintype "passive"))
      (node (ref "U100") (pin "13") (pinfunction "CHG_13") (pintype "bidirectional"))
    )
    (net (code "137") (name "Net-(U100-DSG)") (class "Default")
      (node (ref "R108") (pin "2") (pinfunction "2_2") (pintype "passive"))
      (node (ref "U100") (pin "12") (pinfunction "DSG_12") (pintype "bidirectional"))
    )
    (net (code "138") (name "Net-(U100-LD)") (class "Default")
      (node (ref "R112") (pin "2") (pinfunction "2_2") (pintype "passive"))
      (node (ref "U100") (pin "14") (pinfunction "LD_14") (pintype "bidirectional"))
    )
    (net (code "139") (name "Net-(U100-PRES)") (class "Default")
      (node (ref "R116") (pin "1") (pinfunction "1_1") (pintype "passive"))
      (node (ref "U100") (pin "22") (pinfunction "PRES_22") (pintype "bidirectional"))
    )
    (net (code "140") (name "Net-(U100-SRN)") (class "Default")
      (node (ref "C106") (pin "2") (pinfunction "2_2") (pintype "passive"))
      (node (ref "C107") (pin "2") (pinfunction "2_2") (pintype "passive"))
      (node (ref "R107") (pin "2") (pinfunction "2_2") (pintype "passive"))
      (node (ref "U100") (pin "11") (pinfunction "SRN_11") (pintype "bidirectional"))
    )
    (net (code "141") (name "Net-(U100-SRP)") (class "Default")
      (node (ref "C105") (pin "2") (pinfunction "2_2") (pintype "passive"))
      (node (ref "C106") (pin "1") (pinfunction "1_1") (pintype "passive"))
      (node (ref "R106") (pin "2") (pinfunction "2_2") (pintype "passive"))
      (node (ref "U100") (pin "10") (pinfunction "SRP_10") (pintype "bidirectional"))
    )
    (net (code "142") (name "Net-(U100-VC0)") (class "Default")
      (node (ref "C104") (pin "1") (pinfunction "1_1") (pintype "passive"))
      (node (ref "R104") (pin "2") (pinfunction "2_2") (pintype "passive"))
      (node (ref "U100") (pin "8") (pinfunction "VC0_8") (pintype "bidirectional"))
    )
    (net (code "143") (name "Net-(U100-VC1)") (class "Default")
      (node (ref "C102") (pin "2") (pinfunction "2_2") (pintype "passive"))
      (node (ref "C103") (pin "1") (pinfunction "1_1") (pintype "passive"))
      (node (ref "R103") (pin "2") (pinfunction "2_2") (pintype "passive"))
      (node (ref "U100") (pin "7") (pinfunction "VC1_7") (pintype "bidirectional"))
    )
    (net (code "144") (name "Net-(U100-VC2)") (class "Default")
      (node (ref "C101") (pin "2") (pinfunction "2_2") (pintype "passive"))
      (node (ref "C102") (pin "1") (pinfunction "1_1") (pintype "passive"))
      (node (ref "R102") (pin "2") (pinfunction "2_2") (pintype "passive"))
      (node (ref "U100") (pin "6") (pinfunction "VC2_6") (pintype "bidirectional"))
    )
    (net (code "145") (name "Net-(U100-VC3)") (class "Default")
      (node (ref "C100") (pin "2") (pinfunction "2_2") (pintype "passive"))
      (node (ref "C101") (pin "1") (pinfunction "1_1") (pintype "passive"))
      (node (ref "R101") (pin "2") (pinfunction "2_2") (pintype "passive"))
      (node (ref "U100") (pin "5") (pinfunction "VC3_5") (pintype "bidirectional"))
    )
    (net (code "146") (name "Net-(U100-VC4)") (class "Default")
      (node (ref "C100") (pin "1") (pinfunction "1_1") (pintype "passive"))
      (node (ref "R100") (pin "2") (pinfunction "2_2") (pintype "passive"))
      (node (ref "U100") (pin "3") (pinfunction "VC5_3") (pintype "bidirectional"))
      (node (ref "U100") (pin "4") (pinfunction "VC4_4") (pintype "bidirectional"))
    )
    (net (code "147") (name "Net-(U100-VDD)") (class "Default")
      (node (ref "C108") (pin "1") (pinfunction "1_1") (pintype "passive"))
      (node (ref "R113") (pin "1") (pinfunction "1_1") (pintype "passive"))
      (node (ref "SW100") (pin "1") (pinfunction "1_1") (pintype "passive"))
      (node (ref "U100") (pin "1") (pinfunction "VDD_1") (pintype "bidirectional"))
    )
    (net (code "148") (name "Net-(U100-VTB)") (class "Default")
      (node (ref "R114") (pin "1") (pinfunction "1_1") (pintype "passive"))
      (node (ref "U100") (pin "19") (pinfunction "VTB_19") (pintype "bidirectional"))
    )
    (net (code "149") (name "Net-(U101-CCI)") (class "Default")
      (node (ref "C113") (pin "1") (pinfunction "1_1") (pintype "passive"))
      (node (ref "U101") (pin "11") (pinfunction "CCI_11") (pintype "bidirectional"))
    )
    (net (code "150") (name "Net-(U101-CCS)") (class "Default")
      (node (ref "C114") (pin "1") (pinfunction "1_1") (pintype "passive"))
      (node (ref "U101") (pin "10") (pinfunction "CCS_10") (pintype "bidirectional"))
    )
    (net (code "151") (name "Net-(U101-CCV)") (class "Default")
      (node (ref "C115") (pin "1") (pinfunction "1_1") (pintype "passive"))
      (node (ref "R118") (pin "2") (pinfunction "2_2") (pintype "passive"))
      (node (ref "U101") (pin "9") (pinfunction "CCV_9") (pintype "bidirectional"))
    )
    (net (code "152") (name "Net-(U101-CS)") (class "Default")
      (node (ref "C125") (pin "1") (pinfunction "1_1") (pintype "passive"))
      (node (ref "L100") (pin "2") (pinfunction "2_2") (pintype "passive"))
      (node (ref "R127") (pin "1") (pinfunction "1_1") (pintype "passive"))
      (node (ref "U101") (pin "19") (pinfunction "CS_19") (pintype "bidirectional"))
    )
    (net (code "153") (name "Net-(U101-CSSN)") (class "Default")
      (node (ref "C123") (pin "1") (pinfunction "1_1") (pintype "passive"))
      (node (ref "C129") (pin "+") (pinfunction "+_+") (pintype "passive"))
      (node (ref "C131") (pin "1") (pinfunction "1_1") (pintype "passive"))
      (node (ref "C133") (pin "1") (pinfunction "1_1") (pintype "passive"))
      (node (ref "Q102") (pin "D") (pinfunction "D_D") (pintype "passive"))
      (node (ref "Q105") (pin "S") (pinfunction "S_S") (pintype "passive"))
      (node (ref "R117") (pin "1") (pinfunction "1_1") (pintype "passive"))
      (node (ref "U101") (pin "26") (pinfunction "CSSN_26") (pintype "bidirectional"))
      (node (ref "U103") (pin "3") (pinfunction "EN_3") (pintype "bidirectional"))
      (node (ref "U103") (pin "6") (pinfunction "ANODE_6") (pintype "bidirectional"))
    )
    (net (code "154") (name "Net-(U101-CSSP)") (class "Default")
      (node (ref "C122") (pin "1") (pinfunction "1_1") (pintype "passive"))
      (node (ref "C128") (pin "1") (pinfunction "1_1") (pintype "passive"))
      (node (ref "Q104") (pin "D") (pinfunction "D_D") (pintype "passive"))
      (node (ref "R117") (pin "2") (pinfunction "2_2") (pintype "passive"))
      (node (ref "U101") (pin "27") (pinfunction "CSSP_27") (pintype "bidirectional"))
      (node (ref "U102") (pin "4") (pinfunction "CATHODE_4") (pintype "bidirectional"))
    )
    (net (code "155") (name "Net-(U101-DHI)") (class "Default")
      (node (ref "Q102") (pin "G") (pinfunction "G_G") (pintype "passive"))
      (node (ref "U101") (pin "25") (pinfunction "DHI_25") (pintype "bidirectional"))
    )
    (net (code "156") (name "Net-(U101-DLO)") (class "Default")
      (node (ref "Q103") (pin "G") (pinfunction "G_G") (pintype "passive"))
      (node (ref "U101") (pin "21") (pinfunction "DLO_21") (pintype "bidirectional"))
    )
    (net (code "157") (name "Net-(U101-LX)") (class "Default")
      (node (ref "C110") (pin "2") (pinfunction "2_2") (pintype "passive"))
      (node (ref "L100") (pin "1") (pinfunction "1_1") (pintype "passive"))
      (node (ref "Q102") (pin "S") (pinfunction "S_S") (pintype "passive"))
      (node (ref "Q103") (pin "D") (pinfunction "D_D") (pintype "passive"))
      (node (ref "U101") (pin "24") (pinfunction "LX_24") (pintype "bidirectional"))
    )
    (net (code "158") (name "Net-(U101-THM)") (class "Default")
      (node (ref "R119") (pin "2") (pinfunction "2_2") (pintype "passive"))
      (node (ref "U101") (pin "4") (pinfunction "THM_4") (pintype "bidirectional"))
    )
    (net (code "159") (name "Net-(U101-TIMER1)") (class "Default")
      (node (ref "C112") (pin "1") (pinfunction "1_1") (pintype "passive"))
      (node (ref "U101") (pin "13") (pinfunction "TIMER1_13") (pintype "bidirectional"))
    )
    (net (code "160") (name "Net-(U101-TIMER2)") (class "Default")
      (node (ref "C111") (pin "1") (pinfunction "1_1") (pintype "passive"))
      (node (ref "U101") (pin "14") (pinfunction "TIMER2_14") (pintype "bidirectional"))
    )
    (net (code "161") (name "Net-(U102-GATE)") (class "Default")
      (node (ref "Q104") (pin "G") (pinfunction "G_G") (pintype "passive"))
      (node (ref "U102") (pin "5") (pinfunction "GATE_5") (pintype "bidirectional"))
    )
    (net (code "162") (name "Net-(U102-VCAP)") (class "Default")
      (node (ref "C126") (pin "2") (pinfunction "2_2") (pintype "passive"))
      (node (ref "U102") (pin "1") (pinfunction "VCAP_1") (pintype "bidirectional"))
    )
    (net (code "163") (name "Net-(U103-GATE)") (class "Default")
      (node (ref "Q105") (pin "G") (pinfunction "G_G") (pintype "passive"))
      (node (ref "U103") (pin "5") (pinfunction "GATE_5") (pintype "bidirectional"))
    )
    (net (code "164") (name "Net-(U103-VCAP)") (class "Default")
      (node (ref "C133") (pin "2") (pinfunction "2_2") (pintype "passive"))
      (node (ref "U103") (pin "1") (pinfunction "VCAP_1") (pintype "bidirectional"))
    )
    (net (code "165") (name "Net-(U104-GATE)") (class "Default")
      (node (ref "Q106") (pin "G") (pinfunction "G_G") (pintype "passive"))
      (node (ref "U104") (pin "5") (pinfunction "GATE_5") (pintype "bidirectional"))
    )
    (net (code "166") (name "Net-(U104-VCAP)") (class "Default")
      (node (ref "C136") (pin "2") (pinfunction "2_2") (pintype "passive"))
      (node (ref "U104") (pin "1") (pinfunction "VCAP_1") (pintype "bidirectional"))
    )
    (net (code "167") (name "Net-(U200-COMP)") (class "Default")
      (node (ref "C208") (pin "1") (pinfunction "1_1") (pintype "passive"))
      (node (ref "R203") (pin "1") (pinfunction "1_1") (pintype "passive"))
      (node (ref "U200") (pin "3") (pinfunction "COMP_3") (pintype "bidirectional"))
    )
    (net (code "168") (name "Net-(U200-CS)") (class "Default")
      (node (ref "R204") (pin "1") (pinfunction "1_1") (pintype "passive"))
      (node (ref "U200") (pin "8") (pinfunction "CS_8") (pintype "bidirectional"))
    )
    (net (code "169") (name "Net-(U200-FB)") (class "Default")
      (node (ref "C207") (pin "2") (pinfunction "2_2") (pintype "passive"))
      (node (ref "C208") (pin "2") (pinfunction "2_2") (pintype "passive"))
      (node (ref "R207") (pin "1") (pinfunction "1_1") (pintype "passive"))
      (node (ref "R208") (pin "2") (pinfunction "2_2") (pintype "passive"))
      (node (ref "U200") (pin "2") (pinfunction "FB_2") (pintype "bidirectional"))
    )
    (net (code "170") (name "Net-(U200-OUT)") (class "Default")
      (node (ref "Q200") (pin "G") (pinfunction "G_G") (pintype "passive"))
      (node (ref "Q201") (pin "G") (pinfunction "G_G") (pintype "passive"))
      (node (ref "U200") (pin "5") (pinfunction "OUT_5") (pintype "bidirectional"))
    )
    (net (code "171") (name "Net-(U200-RT{slash}SYNC)") (class "Default")
      (node (ref "R202") (pin "2") (pinfunction "2_2") (pintype "passive"))
      (node (ref "U200") (pin "9") (pinfunction "RT/SYNC_9") (pintype "bidirectional"))
    )
    (net (code "172") (name "Net-(U200-SS)") (class "Default")
      (node (ref "C205") (pin "1") (pinfunction "1_1") (pintype "passive"))
      (node (ref "U200") (pin "10") (pinfunction "SS_10") (pintype "bidirectional"))
    )
    (net (code "173") (name "Net-(U200-UVLO)") (class "Default")
      (node (ref "R200") (pin "1") (pinfunction "1_1") (pintype "passive"))
      (node (ref "R201") (pin "2") (pinfunction "2_2") (pintype "passive"))
      (node (ref "U200") (pin "7") (pinfunction "UVLO_7") (pintype "bidirectional"))
    )
    (net (code "174") (name "Net-(U200-VCC)") (class "Default")
      (node (ref "C206") (pin "1") (pinfunction "1_1") (pintype "passive"))
      (node (ref "U200") (pin "4") (pinfunction "VCC_4") (pintype "bidirectional"))
    )
    (net (code "175") (name "Net-(U201-COMP)") (class "Default")
      (node (ref "C221") (pin "1") (pinfunction "1_1") (pintype "passive"))
      (node (ref "R209") (pin "2") (pinfunction "2_2") (pintype "passive"))
      (node (ref "U201") (pin "2") (pinfunction "COMP_2") (pintype "bidirectional"))
    )
    (net (code "176") (name "Net-(U201-FA{slash}SD)") (class "Default")
      (node (ref "R210") (pin "1") (pinfunction "1_1") (pintype "passive"))
      (node (ref "U201") (pin "7") (pinfunction "FA/SD_7") (pintype "bidirectional"))
    )
    (net (code "177") (name "Net-(U201-FB)") (class "Default")
      (node (ref "R213") (pin "1") (pinfunction "1_1") (pintype "passive"))
      (node (ref "R214") (pin "2") (pinfunction "2_2") (pintype "passive"))
      (node (ref "U201") (pin "3") (pinfunction "FB_3") (pintype "bidirectional"))
    )
    (net (code "178") (name "Net-(U201-ISENSE)") (class "Default")
      (node (ref "C223") (pin "1") (pinfunction "1_1") (pintype "passive"))
      (node (ref "R211") (pin "1") (pinfunction "1_1") (pintype "passive"))
      (node (ref "U201") (pin "1") (pinfunction "ISENSE_1") (pintype "bidirectional"))
    )
    (net (code "179") (name "Net-(U202-ADJ)") (class "Default")
      (node (ref "C225") (pin "2") (pinfunction "2_2") (pintype "passive"))
      (node (ref "R216") (pin "1") (pinfunction "1_1") (pintype "passive"))
      (node (ref "U202") (pin "1") (pinfunction "ADJ_1") (pintype "bidirectional"))
    )
    (net (code "180") (name "Net-(U202-FB)") (class "Default")
      (node (ref "C226") (pin "2") (pinfunction "2_2") (pintype "passive"))
      (node (ref "R218") (pin "1") (pinfunction "1_1") (pintype "passive"))
      (node (ref "R219") (pin "2") (pinfunction "2_2") (pintype "passive"))
      (node (ref "U202") (pin "3") (pinfunction "FB_3") (pintype "bidirectional"))
    )
    (net (code "181") (name "Net-(U202-RT)") (class "Default")
      (node (ref "R215") (pin "1") (pinfunction "1_1") (pintype "passive"))
      (node (ref "U202") (pin "2") (pinfunction "RT_2") (pintype "bidirectional"))
    )
    (net (code "182") (name "Net-(U202-VCC)") (class "Default")
      (node (ref "C214") (pin "2") (pinfunction "2_2") (pintype "passive"))
      (node (ref "U202") (pin "7") (pinfunction "VCC_7") (pintype "bidirectional"))
    )
    (net (code "183") (name "Net-(U300-AVDD)") (class "Default")
      (node (ref "C326") (pin "1") (pinfunction "1_1") (pintype "passive"))
      (node (ref "U300") (pin "14") (pinfunction "AVDD_14") (pintype "bidirectional"))
    )
    (net (code "184") (name "Net-(U300-BST_A)") (class "Default")
      (node (ref "C330") (pin "1") (pinfunction "1_1") (pintype "passive"))
      (node (ref "U300") (pin "44") (pinfunction "BST_A_44") (pintype "bidirectional"))
    )
    (net (code "185") (name "Net-(U300-BST_B)") (class "Default")
      (node (ref "C331") (pin "1") (pinfunction "1_1") (pintype "passive"))
      (node (ref "U300") (pin "43") (pinfunction "BST_B_43") (pintype "bidirectional"))
    )
    (net (code "186") (name "Net-(U300-BST_C)") (class "Default")
      (node (ref "C332") (pin "2") (pinfunction "2_2") (pintype "passive"))
      (node (ref "U300") (pin "24") (pinfunction "BST_C_24") (pintype "bidirectional"))
    )
    (net (code "187") (name "Net-(U300-BST_D)") (class "Default")
      (node (ref "C333") (pin "2") (pinfunction "2_2") (pintype "passive"))
      (node (ref "U300") (pin "23") (pinfunction "BST_D_23") (pintype "bidirectional"))
    )
    (net (code "188") (name "Net-(U300-C_START)") (class "Default")
      (node (ref "C327") (pin "1") (pinfunction "1_1") (pintype "passive"))
      (node (ref "U300") (pin "15") (pinfunction "C_START_15") (pintype "bidirectional"))
    )
    (net (code "189") (name "Net-(U300-DVDD)") (class "Default")
      (node (ref "C325") (pin "1") (pinfunction "1_1") (pintype "passive"))
      (node (ref "U300") (pin "11") (pinfunction "DVDD_11") (pintype "bidirectional"))
      (node (ref "U300") (pin "3") (pinfunction "M1_3") (pintype "bidirectional"))
    )
    (net (code "190") (name "Net-(U300-FREQ_ADJ)") (class "Default")
      (node (ref "R333") (pin "2") (pinfunction "2_2") (pintype "passive"))
      (node (ref "U300") (pin "8") (pinfunction "FREQ_ADJ_8") (pintype "bidirectional"))
    )
    (net (code "191") (name "Net-(U300-GVDD_AB)") (class "Default")
      (node (ref "C324") (pin "1") (pinfunction "1_1") (pintype "passive"))
      (node (ref "R330") (pin "2") (pinfunction "2_2") (pintype "passive"))
      (node (ref "U300") (pin "1") (pinfunction "GVDD_AB_1") (pintype "bidirectional"))
    )
    (net (code "192") (name "Net-(U300-GVDD_CD)") (class "Default")
      (node (ref "C329") (pin "1") (pinfunction "1_1") (pintype "passive"))
      (node (ref "R331") (pin "2") (pinfunction "2_2") (pintype "passive"))
      (node (ref "U300") (pin "22") (pinfunction "GVDD_CD_22") (pintype "bidirectional"))
    )
    (net (code "193") (name "Net-(U300-INPUT_A)") (class "Default")
      (node (ref "C308") (pin "2") (pinfunction "2_2") (pintype "passive"))
      (node (ref "U300") (pin "5") (pinfunction "INPUT_A_5") (pintype "bidirectional"))
    )
    (net (code "194") (name "Net-(U300-INPUT_B)") (class "Default")
      (node (ref "C309") (pin "2") (pinfunction "2_2") (pintype "passive"))
      (node (ref "U300") (pin "6") (pinfunction "INPUT_B_6") (pintype "bidirectional"))
    )
    (net (code "195") (name "Net-(U300-INPUT_C)") (class "Default")
      (node (ref "C315") (pin "2") (pinfunction "2_2") (pintype "passive"))
      (node (ref "U300") (pin "16") (pinfunction "INPUT_C_16") (pintype "bidirectional"))
    )
    (net (code "196") (name "Net-(U300-INPUT_D)") (class "Default")
      (node (ref "C321") (pin "2") (pinfunction "2_2") (pintype "passive"))
      (node (ref "U300") (pin "17") (pinfunction "INPUT_D_17") (pintype "bidirectional"))
    )
    (net (code "197") (name "Net-(U300-OC_ADJ)") (class "Default")
      (node (ref "R332") (pin "2") (pinfunction "2_2") (pintype "passive"))
      (node (ref "U300") (pin "7") (pinfunction "OC_ADJ_7") (pintype "bidirectional"))
    )
    (net (code "198") (name "Net-(U300-OUT_B)") (class "Default")
      (node (ref "C331") (pin "2") (pinfunction "2_2") (pintype "passive"))
      (node (ref "L301") (pin "1") (pinfunction "1_1") (pintype "passive"))
      (node (ref "U300") (pin "35") (pinfunction "OUT_B_35") (pintype "bidirectional"))
    )
    (net (code "199") (name "Net-(U300-OUT_C)") (class "Default")
      (node (ref "C332") (pin "1") (pinfunction "1_1") (pintype "passive"))
      (node (ref "L302") (pin "1") (pinfunction "1_1") (pintype "passive"))
      (node (ref "U300") (pin "32") (pinfunction "OUT_C_32") (pintype "bidirectional"))
    )
    (net (code "200") (name "Net-(U300-VBG)") (class "Default")
      (node (ref "C328") (pin "1") (pinfunction "1_1") (pintype "passive"))
      (node (ref "U300") (pin "20") (pinfunction "VBG_20") (pintype "bidirectional"))
    )
    (net (code "201") (name "Net-(U301-+IN)") (class "Default")
      (node (ref "R300") (pin "2") (pinfunction "2_2") (pintype "passive"))
      (node (ref "R303") (pin "1") (pinfunction "1_1") (pintype "passive"))
      (node (ref "RT300") (pin "2") (pinfunction "2_2") (pintype "bidirectional"))
      (node (ref "U301") (pin "3") (pinfunction "+IN_3") (pintype "input"))
    )
    (net (code "202") (name "Net-(U301--IN)") (class "Default")
      (node (ref "R301") (pin "1") (pinfunction "1_1") (pintype "passive"))
      (node (ref "R302") (pin "1") (pinfunction "1_1") (pintype "passive"))
      (node (ref "U301") (pin "4") (pinfunction "-IN_4") (pintype "input"))
    )
    (net (code "203") (name "Net-(U302A--IN)") (class "Default")
      (node (ref "R306") (pin "2") (pinfunction "2_2") (pintype "passive"))
      (node (ref "R307") (pin "1") (pinfunction "1_1") (pintype "passive"))
      (node (ref "U302") (pin "2") (pinfunction "-IN_2") (pintype "input"))
    )
    (net (code "204") (name "Net-(U302A-OUT)") (class "Default")
      (node (ref "C310") (pin "1") (pinfunction "1_1") (pintype "passive"))
      (node (ref "C354") (pin "2") (pinfunction "2_2") (pintype "passive"))
      (node (ref "R307") (pin "2") (pinfunction "2_2") (pintype "passive"))
      (node (ref "U302") (pin "1") (pinfunction "OUT_1") (pintype "output"))
    )
    (net (code "205") (name "Net-(U302B--IN)") (class "Default")
      (node (ref "R308") (pin "2") (pinfunction "2_2") (pintype "passive"))
      (node (ref "R309") (pin "1") (pinfunction "1_1") (pintype "passive"))
      (node (ref "U302") (pin "6") (pinfunction "-IN_6") (pintype "input"))
    )
    (net (code "206") (name "Net-(U302B-OUT)") (class "Default")
      (node (ref "C316") (pin "1") (pinfunction "1_1") (pintype "passive"))
      (node (ref "C355") (pin "2") (pinfunction "2_2") (pintype "passive"))
      (node (ref "R309") (pin "2") (pinfunction "2_2") (pintype "passive"))
      (node (ref "U302") (pin "7") (pinfunction "OUT_7") (pintype "output"))
    )
    (net (code "207") (name "Net-(U302C-+IN)") (class "Default")
      (node (ref "C317") (pin "2") (pinfunction "2_2") (pintype "passive"))
      (node (ref "R324") (pin "2") (pinfunction "2_2") (pintype "passive"))
      (node (ref "U302") (pin "10") (pinfunction "+IN_10") (pintype "input"))
    )
    (net (code "208") (name "Net-(U302C--IN)") (class "Default")
      (node (ref "C318") (pin "1") (pinfunction "1_1") (pintype "passive"))
      (node (ref "R325") (pin "2") (pinfunction "2_2") (pintype "passive"))
      (node (ref "U302") (pin "8") (pinfunction "OUT_8") (pintype "output"))
      (node (ref "U302") (pin "9") (pinfunction "-IN_9") (pintype "input"))
    )
    (net (code "209") (name "Net-(U302D-+IN)") (class "Default")
      (node (ref "C311") (pin "2") (pinfunction "2_2") (pintype "passive"))
      (node (ref "R318") (pin "2") (pinfunction "2_2") (pintype "passive"))
      (node (ref "U302") (pin "12") (pinfunction "+IN_12") (pintype "input"))
    )
    (net (code "210") (name "Net-(U302D--IN)") (class "Default")
      (node (ref "C312") (pin "1") (pinfunction "1_1") (pintype "passive"))
      (node (ref "R319") (pin "2") (pinfunction "2_2") (pintype "passive"))
      (node (ref "U302") (pin "13") (pinfunction "-IN_13") (pintype "input"))
      (node (ref "U302") (pin "14") (pinfunction "OUT_14") (pintype "output"))
    )
    (net (code "211") (name "Net-(U303A-+IN)") (class "Default")
      (node (ref "C313") (pin "2") (pinfunction "2_2") (pintype "passive"))
      (node (ref "R320") (pin "2") (pinfunction "2_2") (pintype "passive"))
      (node (ref "U303") (pin "3") (pinfunction "+IN_3") (pintype "input"))
    )
    (net (code "212") (name "Net-(U303A--IN)") (class "Default")
      (node (ref "C314") (pin "1") (pinfunction "1_1") (pintype "passive"))
      (node (ref "R321") (pin "2") (pinfunction "2_2") (pintype "passive"))
      (node (ref "U303") (pin "1") (pinfunction "OUT_1") (pintype "output"))
      (node (ref "U303") (pin "2") (pinfunction "-IN_2") (pintype "input"))
    )
    (net (code "213") (name "Net-(U303B-+IN)") (class "Default")
      (node (ref "C319") (pin "2") (pinfunction "2_2") (pintype "passive"))
      (node (ref "R326") (pin "2") (pinfunction "2_2") (pintype "passive"))
      (node (ref "U303") (pin "5") (pinfunction "+IN_5") (pintype "input"))
    )
    (net (code "214") (name "Net-(U303B--IN)") (class "Default")
      (node (ref "C320") (pin "1") (pinfunction "1_1") (pintype "passive"))
      (node (ref "R327") (pin "2") (pinfunction "2_2") (pintype "passive"))
      (node (ref "U303") (pin "6") (pinfunction "-IN_6") (pintype "input"))
      (node (ref "U303") (pin "7") (pinfunction "OUT_7") (pintype "output"))
    )
    (net (code "215") (name "Net-(U303C--IN)") (class "Default")
      (node (ref "R328") (pin "2") (pinfunction "2_2") (pintype "passive"))
      (node (ref "R329") (pin "1") (pinfunction "1_1") (pintype "passive"))
      (node (ref "U303") (pin "9") (pinfunction "-IN_9") (pintype "input"))
    )
    (net (code "216") (name "Net-(U303D--IN)") (class "Default")
      (node (ref "R322") (pin "2") (pinfunction "2_2") (pintype "passive"))
      (node (ref "R323") (pin "1") (pinfunction "1_1") (pintype "passive"))
      (node (ref "U303") (pin "13") (pinfunction "-IN_13") (pintype "input"))
    )
    (net (code "217") (name "Net-(U304A-+IN)") (class "Default")
      (node (ref "C303") (pin "2") (pinfunction "2_2") (pintype "passive"))
      (node (ref "R311") (pin "2") (pinfunction "2_2") (pintype "passive"))
      (node (ref "U304") (pin "3") (pinfunction "+IN_3") (pintype "input"))
    )
    (net (code "218") (name "Net-(U304A--IN)") (class "Default")
      (node (ref "C304") (pin "2") (pinfunction "2_2") (pintype "passive"))
      (node (ref "R312") (pin "1") (pinfunction "1_1") (pintype "passive"))
      (node (ref "U304") (pin "1") (pinfunction "OUT_1") (pintype "output"))
      (node (ref "U304") (pin "2") (pinfunction "-IN_2") (pintype "input"))
    )
    (net (code "219") (name "Net-(U304B--IN)") (class "Default")
      (node (ref "R316") (pin "2") (pinfunction "2_2") (pintype "passive"))
      (node (ref "R317") (pin "1") (pinfunction "1_1") (pintype "passive"))
      (node (ref "U304") (pin "6") (pinfunction "-IN_6") (pintype "input"))
    )
    (net (code "220") (name "Net-(U304B-OUT)") (class "Default")
      (node (ref "C309") (pin "1") (pinfunction "1_1") (pintype "passive"))
      (node (ref "R317") (pin "2") (pinfunction "2_2") (pintype "passive"))
      (node (ref "U304") (pin "7") (pinfunction "OUT_7") (pintype "output"))
    )
    (net (code "221") (name "Net-(U304C--IN)") (class "Default")
      (node (ref "R314") (pin "2") (pinfunction "2_2") (pintype "passive"))
      (node (ref "R315") (pin "1") (pinfunction "1_1") (pintype "passive"))
      (node (ref "U304") (pin "9") (pinfunction "-IN_9") (pintype "input"))
    )
    (net (code "222") (name "Net-(U304D-+IN)") (class "Default")
      (node (ref "C305") (pin "2") (pinfunction "2_2") (pintype "passive"))
      (node (ref "R313") (pin "2") (pinfunction "2_2") (pintype "passive"))
      (node (ref "U304") (pin "12") (pinfunction "+IN_12") (pintype "input"))
    )
    (net (code "223") (name "Net-(U304D--IN)") (class "Default")
      (node (ref "C306") (pin "2") (pinfunction "2_2") (pintype "passive"))
      (node (ref "C307") (pin "1") (pinfunction "1_1") (pintype "passive"))
      (node (ref "U304") (pin "13") (pinfunction "-IN_13") (pintype "input"))
      (node (ref "U304") (pin "14") (pinfunction "OUT_14") (pintype "output"))
    )
    (net (code "224") (name "Net-(U305A--IN)") (class "Default")
      (node (ref "R338") (pin "2") (pinfunction "2_2") (pintype "passive"))
      (node (ref "R339") (pin "2") (pinfunction "2_2") (pintype "passive"))
      (node (ref "R340") (pin "1") (pinfunction "1_1") (pintype "passive"))
      (node (ref "U305") (pin "2") (pinfunction "-IN_2") (pintype "input"))
    )
    (net (code "225") (name "Net-(U305A-OUT)") (class "Default")
      (node (ref "C356") (pin "2") (pinfunction "2_2") (pintype "passive"))
      (node (ref "R310") (pin "1") (pinfunction "1_1") (pintype "passive"))
      (node (ref "R340") (pin "2") (pinfunction "2_2") (pintype "passive"))
      (node (ref "U305") (pin "1") (pinfunction "OUT_1") (pintype "output"))
    )
    (net (code "226") (name "Net-(U305B--IN)") (class "Default")
      (node (ref "R341") (pin "2") (pinfunction "2_2") (pintype "passive"))
      (node (ref "R342") (pin "1") (pinfunction "1_1") (pintype "passive"))
      (node (ref "U305") (pin "6") (pinfunction "-IN_6") (pintype "input"))
    )
    (net (code "227") (name "Net-(U306-+IN)") (class "Default")
      (node (ref "R344") (pin "2") (pinfunction "2_2") (pintype "passive"))
      (node (ref "R345") (pin "2") (pinfunction "2_2") (pintype "passive"))
      (node (ref "U306") (pin "3") (pinfunction "+IN_3") (pintype "input"))
    )
    (net (code "228") (name "Net-(U306--IN)") (class "Default")
      (node (ref "R346") (pin "2") (pinfunction "2_2") (pintype "passive"))
      (node (ref "R347") (pin "1") (pinfunction "1_1") (pintype "passive"))
      (node (ref "U306") (pin "4") (pinfunction "-IN_4") (pintype "input"))
    )
    (net (code "229") (name "Net-(U306-OUT)") (class "Default")
      (node (ref "R347") (pin "2") (pinfunction "2_2") (pintype "passive"))
      (node (ref "R348") (pin "1") (pinfunction "1_1") (pintype "passive"))
      (node (ref "U306") (pin "1") (pinfunction "OUT_1") (pintype "output"))
    )
    (net (code "230") (name "Net-(U400-ICSPCLK{slash}RB6)") (class "Default")
      (node (ref "J400") (pin "5") (pinfunction "5_5") (pintype "passive"))
      (node (ref "U400") (pin "16") (pinfunction "ICSPCLK/RB6_16") (pintype "bidirectional"))
    )
    (net (code "231") (name "Net-(U400-ICSPDAT{slash}RB7)") (class "Default")
      (node (ref "J400") (pin "4") (pinfunction "4_4") (pintype "passive"))
      (node (ref "U400") (pin "17") (pinfunction "ICSPDAT/RB7_17") (pintype "bidirectional"))
    )
    (net (code "232") (name "Net-(U400-RA0)") (class "Default")
      (node (ref "U400") (pin "19") (pinfunction "RA0_19") (pintype "bidirectional"))
      (node (ref "XDS400") (pin "7") (pinfunction "D0_7") (pintype "bidirectional"))
    )
    (net (code "233") (name "Net-(U400-RA1)") (class "Default")
      (node (ref "U400") (pin "20") (pinfunction "RA1_20") (pintype "bidirectional"))
      (node (ref "XDS400") (pin "8") (pinfunction "D1_8") (pintype "bidirectional"))
    )
    (net (code "234") (name "Net-(U400-RA2)") (class "Default")
      (node (ref "U400") (pin "21") (pinfunction "RA2_21") (pintype "bidirectional"))
      (node (ref "XDS400") (pin "9") (pinfunction "D2_9") (pintype "bidirectional"))
    )
    (net (code "235") (name "Net-(U400-RA3)") (class "Default")
      (node (ref "U400") (pin "22") (pinfunction "RA3_22") (pintype "bidirectional"))
      (node (ref "XDS400") (pin "10") (pinfunction "D3_10") (pintype "bidirectional"))
    )
    (net (code "236") (name "Net-(U400-RA4)") (class "Default")
      (node (ref "U400") (pin "23") (pinfunction "RA4_23") (pintype "bidirectional"))
      (node (ref "XDS400") (pin "11") (pinfunction "D4_11") (pintype "bidirectional"))
    )
    (net (code "237") (name "Net-(U400-RA5)") (class "Default")
      (node (ref "U400") (pin "24") (pinfunction "RA5_24") (pintype "bidirectional"))
      (node (ref "XDS400") (pin "12") (pinfunction "D5_12") (pintype "bidirectional"))
    )
    (net (code "238") (name "Net-(U400-RA6)") (class "Default")
      (node (ref "U400") (pin "31") (pinfunction "RA6_31") (pintype "bidirectional"))
      (node (ref "XDS400") (pin "13") (pinfunction "D6_13") (pintype "bidirectional"))
    )
    (net (code "239") (name "Net-(U400-RA7)") (class "Default")
      (node (ref "U400") (pin "30") (pinfunction "RA7_30") (pintype "bidirectional"))
      (node (ref "XDS400") (pin "14") (pinfunction "D7_14") (pintype "bidirectional"))
    )
    (net (code "240") (name "Net-(U400-RC1)") (class "Default")
      (node (ref "SW408") (pin "1") (pinfunction "1_1") (pintype "passive"))
      (node (ref "U400") (pin "35") (pinfunction "RC1_35") (pintype "bidirectional"))
    )
    (net (code "241") (name "Net-(U400-RD3)") (class "Default")
      (node (ref "U400") (pin "41") (pinfunction "RD3_41") (pintype "bidirectional"))
      (node (ref "U402") (pin "1") (pinfunction "OUT_1") (pintype "output"))
      (node (ref "U402") (pin "4") (pinfunction "-IN_4") (pintype "input"))
    )
    (net (code "242") (name "Net-(U400-RE0)") (class "Default")
      (node (ref "U400") (pin "25") (pinfunction "RE0_25") (pintype "bidirectional"))
      (node (ref "XDS400") (pin "4") (pinfunction "RS_4") (pintype "bidirectional"))
    )
    (net (code "243") (name "Net-(U400-RE1)") (class "Default")
      (node (ref "U400") (pin "26") (pinfunction "RE1_26") (pintype "bidirectional"))
      (node (ref "XDS400") (pin "5") (pinfunction "RW_5") (pintype "bidirectional"))
    )
    (net (code "244") (name "Net-(U400-RE2)") (class "Default")
      (node (ref "U400") (pin "27") (pinfunction "RE2_27") (pintype "bidirectional"))
      (node (ref "XDS400") (pin "6") (pinfunction "~{E}_6") (pintype "bidirectional"))
    )
    (net (code "245") (name "Net-(U400-VPP{slash}~{MCLR}{slash}RE3)") (class "Default")
      (node (ref "J400") (pin "1") (pinfunction "1_1") (pintype "passive"))
      (node (ref "R400") (pin "2") (pinfunction "2_2") (pintype "passive"))
      (node (ref "U400") (pin "18") (pinfunction "VPP/~{MCLR}/RE3_18") (pintype "bidirectional"))
    )
    (net (code "246") (name "Net-(U401-CBUS1)") (class "Default")
      (node (ref "SJ402") (pin "2") (pinfunction "2_2") (pintype "passive"))
      (node (ref "U401") (pin "14") (pinfunction "CBUS1_14") (pintype "bidirectional"))
    )
    (net (code "247") (name "Net-(U401-~{CTS})") (class "Default")
      (node (ref "R405") (pin "2") (pinfunction "2_2") (pintype "passive"))
      (node (ref "U401") (pin "6") (pinfunction "~{CTS}_6") (pintype "input"))
    )
    (net (code "248") (name "Net-(U401-~{RESET})") (class "Default")
      (node (ref "SJ403") (pin "2") (pinfunction "2_2") (pintype "passive"))
      (node (ref "U401") (pin "11") (pinfunction "~{RESET}_11") (pintype "input"))
    )
    (net (code "249") (name "Net-(U402-+IN)") (class "Default")
      (node (ref "R406") (pin "1") (pinfunction "1_1") (pintype "passive"))
      (node (ref "R407") (pin "2") (pinfunction "2_2") (pintype "passive"))
      (node (ref "U402") (pin "3") (pinfunction "+IN_3") (pintype "input"))
    )
    (net (code "250") (name "Net-(XBT100-BAL1)") (class "Default")
      (node (ref "R103") (pin "1") (pinfunction "1_1") (pintype "passive"))
      (node (ref "XBT100") (pin "4") (pinfunction "BAL1_4") (pintype "bidirectional"))
    )
    (net (code "251") (name "Net-(XBT100-BAL2)") (class "Default")
      (node (ref "R102") (pin "1") (pinfunction "1_1") (pintype "passive"))
      (node (ref "XBT100") (pin "3") (pinfunction "BAL2_3") (pintype "bidirectional"))
    )
    (net (code "252") (name "Net-(XBT100-BAL3)") (class "Default")
      (node (ref "R101") (pin "1") (pinfunction "1_1") (pintype "passive"))
      (node (ref "XBT100") (pin "7") (pinfunction "BAL3_7") (pintype "bidirectional"))
    )
    (net (code "253") (name "Net-(XDS400-A)") (class "Default")
      (node (ref "SJ400") (pin "2") (pinfunction "2_2") (pintype "passive"))
      (node (ref "XDS400") (pin "15") (pinfunction "A_15") (pintype "bidirectional"))
    )
    (net (code "254") (name "Net-(XLS300-+)") (class "Default")
      (node (ref "F300") (pin "2") (pinfunction "2_2") (pintype "passive"))
      (node (ref "XLS300") (pin "2") (pinfunction "+_2") (pintype "passive"))
    )
    (net (code "255") (name "Net-(XLS300--)") (class "Default")
      (node (ref "C343") (pin "2") (pinfunction "2_2") (pintype "passive"))
      (node (ref "C344") (pin "2") (pinfunction "2_2") (pintype "passive"))
      (node (ref "C345") (pin "2") (pinfunction "2_2") (pintype "passive"))
      (node (ref "L301") (pin "2") (pinfunction "2_2") (pintype "passive"))
      (node (ref "XLS300") (pin "1") (pinfunction "-_1") (pintype "passive"))
    )
    (net (code "256") (name "Net-(XLS301-+)") (class "Default")
      (node (ref "F301") (pin "2") (pinfunction "2_2") (pintype "passive"))
      (node (ref "XLS301") (pin "2") (pinfunction "+_2") (pintype "passive"))
    )
    (net (code "257") (name "Net-(XLS302-+)") (class "Default")
      (node (ref "F302") (pin "2") (pinfunction "2_2") (pintype "passive"))
      (node (ref "XLS302") (pin "2") (pinfunction "+_2") (pintype "passive"))
    )
    (net (code "258") (name "PA_AMPLITUDE") (class "Default")
      (node (ref "C358") (pin "1") (pinfunction "1_1") (pintype "passive"))
      (node (ref "R348") (pin "2") (pinfunction "2_2") (pintype "passive"))
      (node (ref "U400") (pin "43") (pinfunction "RC5_43") (pintype "bidirectional"))
    )
    (net (code "259") (name "VBAT") (class "Default")
      (node (ref "C117") (pin "1") (pinfunction "1_1") (pintype "passive"))
      (node (ref "C130") (pin "+") (pinfunction "+_+") (pintype "passive"))
      (node (ref "C134") (pin "1") (pinfunction "1_1") (pintype "passive"))
      (node (ref "C136") (pin "1") (pinfunction "1_1") (pintype "passive"))
      (node (ref "F100") (pin "2") (pinfunction "2_2") (pintype "passive"))
      (node (ref "Q106") (pin "S") (pinfunction "S_S") (pintype "passive"))
      (node (ref "R113") (pin "2") (pinfunction "2_2") (pintype "passive"))
      (node (ref "R127") (pin "2") (pinfunction "2_2") (pintype "passive"))
      (node (ref "R406") (pin "2") (pinfunction "2_2") (pintype "passive"))
      (node (ref "U101") (pin "7") (pinfunction "BATT_7") (pintype "bidirectional"))
      (node (ref "U104") (pin "3") (pinfunction "EN_3") (pintype "bidirectional"))
      (node (ref "U104") (pin "6") (pinfunction "ANODE_6") (pintype "bidirectional"))
    )
    (net (code "260") (name "VSUP") (class "Default")
      (node (ref "C132") (pin "1") (pinfunction "1_1") (pintype "passive"))
      (node (ref "C135") (pin "1") (pinfunction "1_1") (pintype "passive"))
      (node (ref "C200") (pin "+") (pinfunction "+_+") (pintype "passive"))
      (node (ref "C204") (pin "1") (pinfunction "1_1") (pintype "passive"))
      (node (ref "C213") (pin "1") (pinfunction "1_1") (pintype "passive"))
      (node (ref "C214") (pin "1") (pinfunction "1_1") (pintype "passive"))
      (node (ref "C219") (pin "1") (pinfunction "1_1") (pintype "passive"))
      (node (ref "C220") (pin "1") (pinfunction "1_1") (pintype "passive"))
      (node (ref "C225") (pin "1") (pinfunction "1_1") (pintype "passive"))
      (node (ref "L200") (pin "1") (pinfunction "1_1") (pintype "passive"))
      (node (ref "L201") (pin "1") (pinfunction "P1_1") (pintype "passive"))
      (node (ref "Q105") (pin "D") (pinfunction "D_D") (pintype "passive"))
      (node (ref "Q106") (pin "D") (pinfunction "D_D") (pintype "passive"))
      (node (ref "R200") (pin "2") (pinfunction "2_2") (pintype "passive"))
      (node (ref "R215") (pin "2") (pinfunction "2_2") (pintype "passive"))
      (node (ref "R216") (pin "2") (pinfunction "2_2") (pintype "passive"))
      (node (ref "R217") (pin "2") (pinfunction "2_2") (pintype "passive"))
      (node (ref "U103") (pin "4") (pinfunction "CATHODE_4") (pintype "bidirectional"))
      (node (ref "U104") (pin "4") (pinfunction "CATHODE_4") (pintype "bidirectional"))
      (node (ref "U200") (pin "1") (pinfunction "VIN_1") (pintype "bidirectional"))
      (node (ref "U201") (pin "8") (pinfunction "VIN_8") (pintype "bidirectional"))
      (node (ref "U202") (pin "8") (pinfunction "VIN_8") (pintype "bidirectional"))
    )
    (net (code "261") (name "unconnected-(A400-AMB_DET-Pad22)") (class "Default")
      (node (ref "A400") (pin "22") (pinfunction "AMB_DET_22") (pintype "bidirectional"))
    )
    (net (code "262") (name "unconnected-(A400-AOHPM-Pad8)") (class "Default")
      (node (ref "A400") (pin "8") (pinfunction "AOHPM_8") (pintype "bidirectional"))
    )
    (net (code "263") (name "unconnected-(A400-BK_OUT-Pad25)") (class "Default")
      (node (ref "A400") (pin "25") (pinfunction "BK_OUT_25") (pintype "bidirectional"))
    )
    (net (code "264") (name "unconnected-(A400-MIC_BIAS-Pad13)") (class "Default")
      (node (ref "A400") (pin "13") (pinfunction "MIC_BIAS_13") (pintype "bidirectional"))
    )
    (net (code "265") (name "unconnected-(A400-P0_0-Pad1)") (class "Default")
      (node (ref "A400") (pin "1") (pinfunction "P0_0_1") (pintype "bidirectional"))
    )
    (net (code "266") (name "unconnected-(A400-P0_4-Pad6)") (class "Default")
      (node (ref "A400") (pin "6") (pinfunction "P0_4_6") (pintype "bidirectional"))
    )
    (net (code "267") (name "unconnected-(A400-P3_0-Pad3)") (class "Default")
      (node (ref "A400") (pin "3") (pinfunction "P3_0_3") (pintype "bidirectional"))
    )
    (net (code "268") (name "unconnected-(A400-VDDA-Pad10)") (class "Default")
      (node (ref "A400") (pin "10") (pinfunction "VDDA_10") (pintype "bidirectional"))
    )
    (net (code "269") (name "unconnected-(A400-VDD_IO-Pad19)") (class "Default")
      (node (ref "A400") (pin "19") (pinfunction "VDD_IO_19") (pintype "bidirectional"))
    )
    (net (code "270") (name "unconnected-(J400-Pad6)") (class "Default")
      (node (ref "J400") (pin "6") (pinfunction "6_6") (pintype "passive"))
    )
    (net (code "271") (name "unconnected-(J400-Pad7)") (class "Default")
      (node (ref "J400") (pin "7") (pinfunction "7_7") (pintype "passive"))
    )
    (net (code "272") (name "unconnected-(J400-Pad8)") (class "Default")
      (node (ref "J400") (pin "8") (pinfunction "8_8") (pintype "passive"))
    )
    (net (code "273") (name "unconnected-(J401-ID-Pad4)") (class "Default")
      (node (ref "J401") (pin "4") (pinfunction "ID_4") (pintype "passive"))
    )
    (net (code "274") (name "unconnected-(RV300-E-Pad3)") (class "Default")
      (node (ref "RV300") (pin "3") (pinfunction "E_3") (pintype "passive"))
    )
    (net (code "275") (name "unconnected-(RV301-E-Pad3)") (class "Default")
      (node (ref "RV301") (pin "3") (pinfunction "E_3") (pintype "passive"))
    )
    (net (code "276") (name "unconnected-(RV302-E-Pad3)") (class "Default")
      (node (ref "RV302") (pin "3") (pinfunction "E_3") (pintype "passive"))
    )
    (net (code "277") (name "unconnected-(RV303-E-Pad3)") (class "Default")
      (node (ref "RV303") (pin "3") (pinfunction "E_3") (pintype "passive"))
    )
    (net (code "278") (name "unconnected-(SW400C-O-PadB6)") (class "Default")
      (node (ref "SW400") (pin "B6") (pinfunction "O_B6") (pintype "passive"))
    )
    (net (code "279") (name "unconnected-(SW400D-O-PadB8)") (class "Default")
      (node (ref "SW400") (pin "B8") (pinfunction "O_B8") (pintype "passive"))
    )
    (net (code "280") (name "unconnected-(SW400E-O-PadB10)") (class "Default")
      (node (ref "SW400") (pin "B10") (pinfunction "O_B10") (pintype "passive"))
    )
    (net (code "281") (name "unconnected-(U100-CBO-Pad21)") (class "Default")
      (node (ref "U100") (pin "21") (pinfunction "CBO_21") (pintype "bidirectional"))
    )
    (net (code "282") (name "unconnected-(U100-LPWR-Pad15)") (class "Default")
      (node (ref "U100") (pin "15") (pinfunction "LPWR_15") (pintype "bidirectional"))
    )
    (net (code "283") (name "unconnected-(U100-OCDP-Pad17)") (class "Default")
      (node (ref "U100") (pin "17") (pinfunction "OCDP_17") (pintype "bidirectional"))
    )
    (net (code "284") (name "unconnected-(U300-OSC_IOM-Pad9)") (class "Default")
      (node (ref "U300") (pin "9") (pinfunction "OSC_IOM_9") (pintype "bidirectional"))
    )
    (net (code "285") (name "unconnected-(U300-OSC_IOP-Pad10)") (class "Default")
      (node (ref "U300") (pin "10") (pinfunction "OSC_IOP_10") (pintype "bidirectional"))
    )
    (net (code "286") (name "unconnected-(U400-RB5-Pad15)") (class "Default")
      (node (ref "U400") (pin "15") (pinfunction "RB5_15") (pintype "bidirectional"))
    )
    (net (code "287") (name "unconnected-(U401-CBUS0-Pad15)") (class "Default")
      (node (ref "U401") (pin "15") (pinfunction "CBUS0_15") (pintype "bidirectional"))
    )
    (net (code "288") (name "unconnected-(U401-CBUS2-Pad7)") (class "Default")
      (node (ref "U401") (pin "7") (pinfunction "CBUS2_7") (pintype "bidirectional"))
    )
    (net (code "289") (name "unconnected-(U401-CBUS3-Pad16)") (class "Default")
      (node (ref "U401") (pin "16") (pinfunction "CBUS3_16") (pintype "bidirectional"))
    )
    (net (code "290") (name "unconnected-(U401-~{RTS}-Pad2)") (class "Default")
      (node (ref "U401") (pin "2") (pinfunction "~{RTS}_2") (pintype "output"))
    )
  )
)
